# VDD_GND.net
KiCad netlist of a schematic drawn in Altium Designer
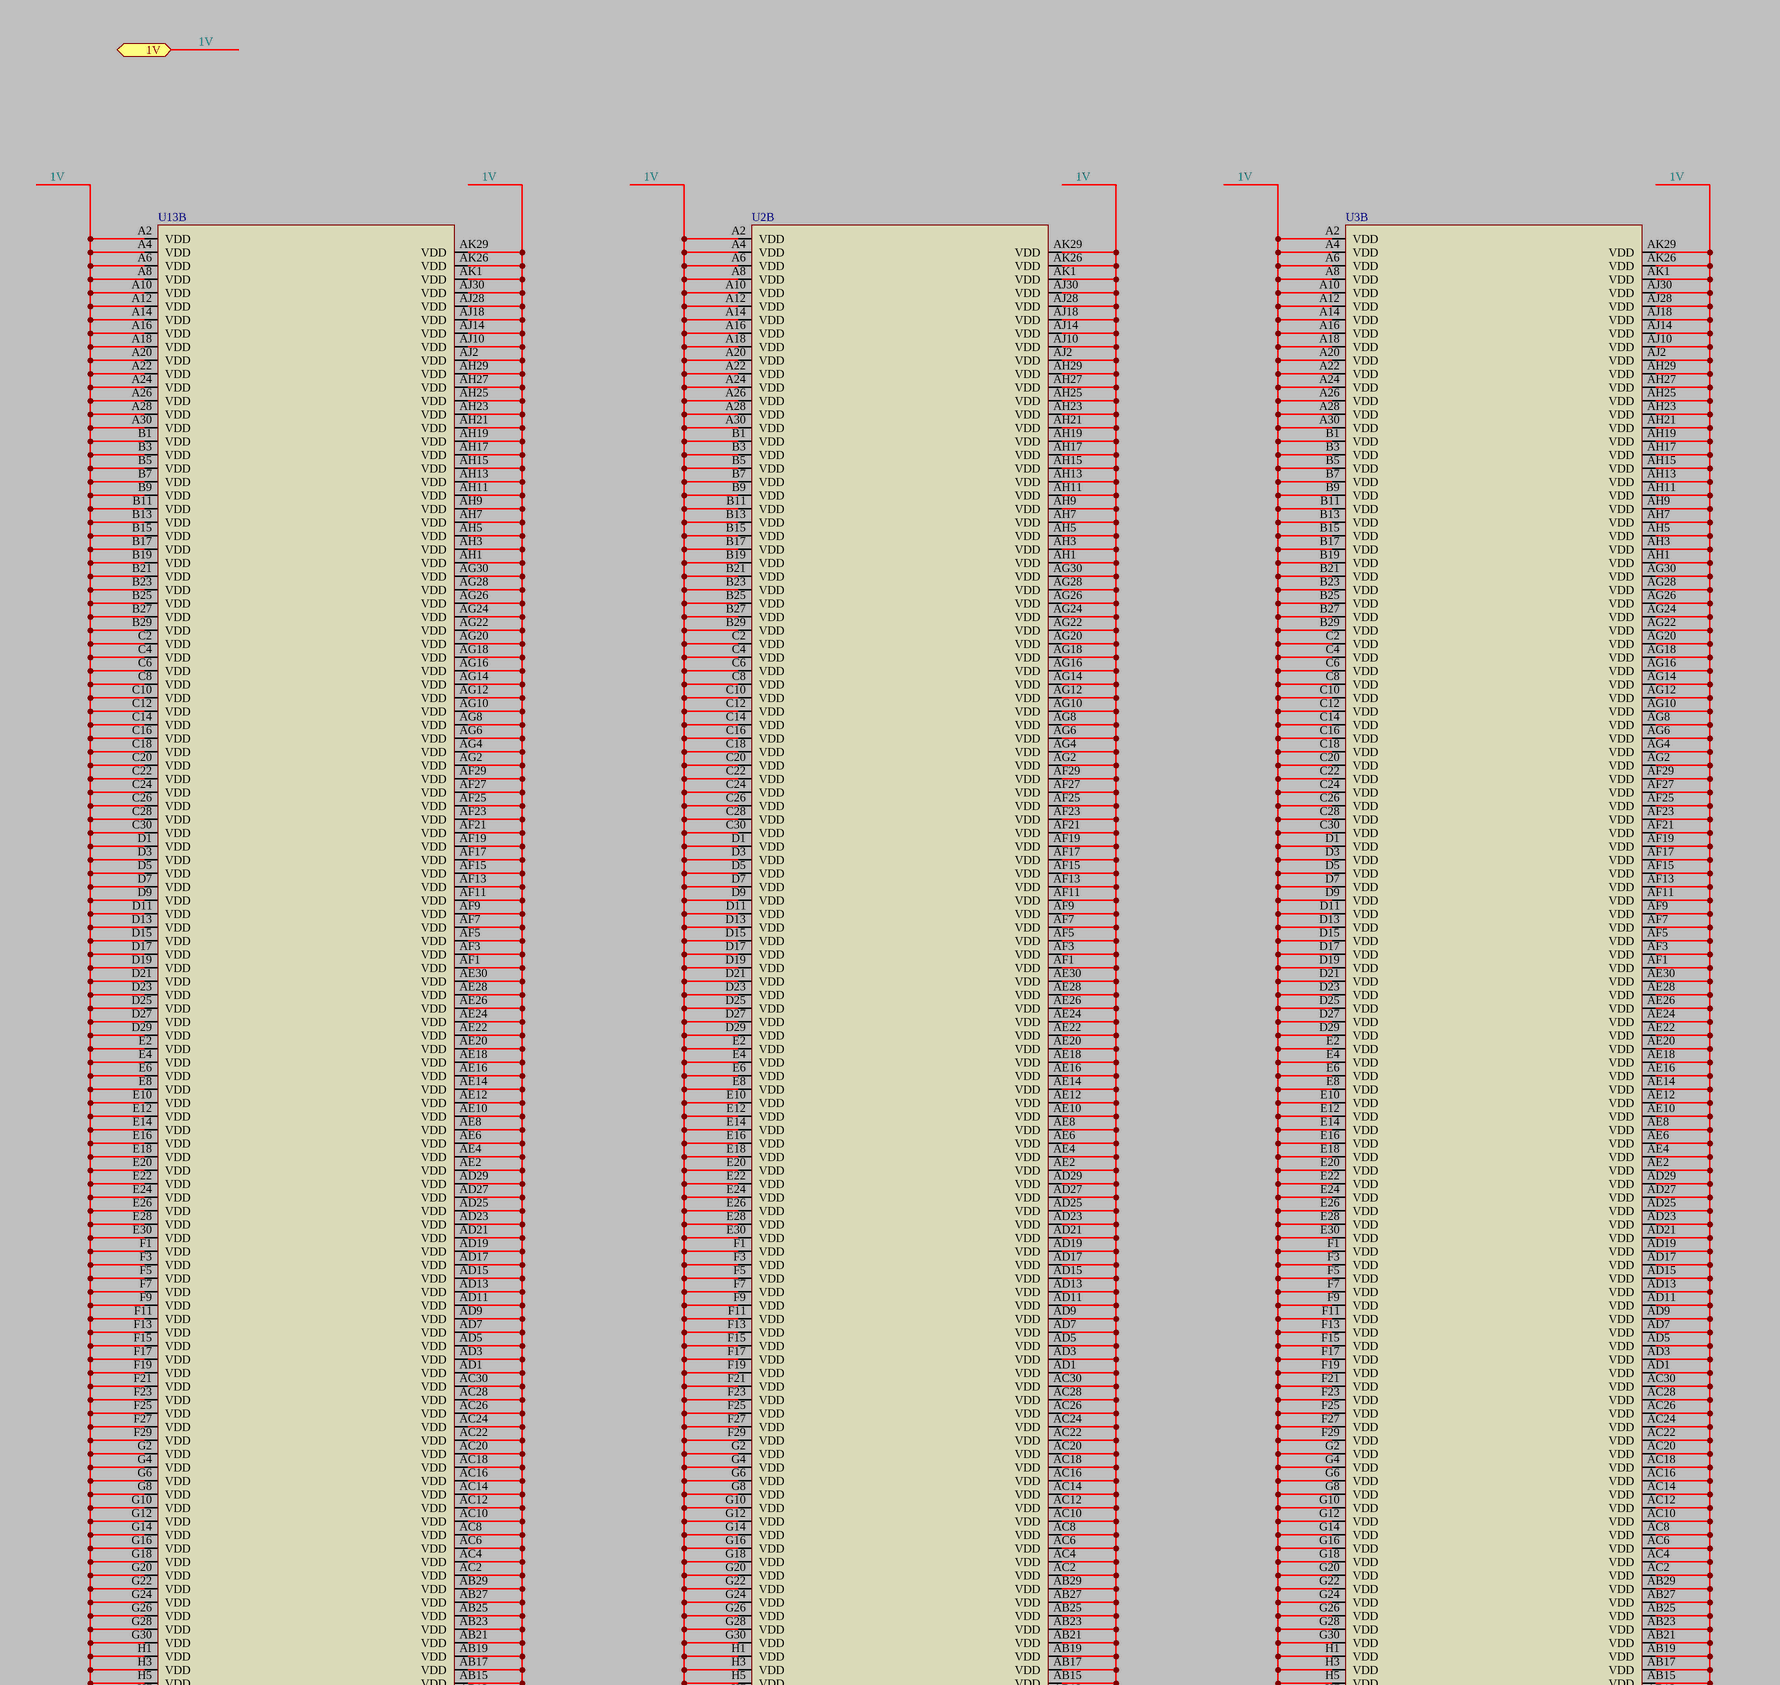
[diagram p0: VDD_GND.SchDoc, top left]
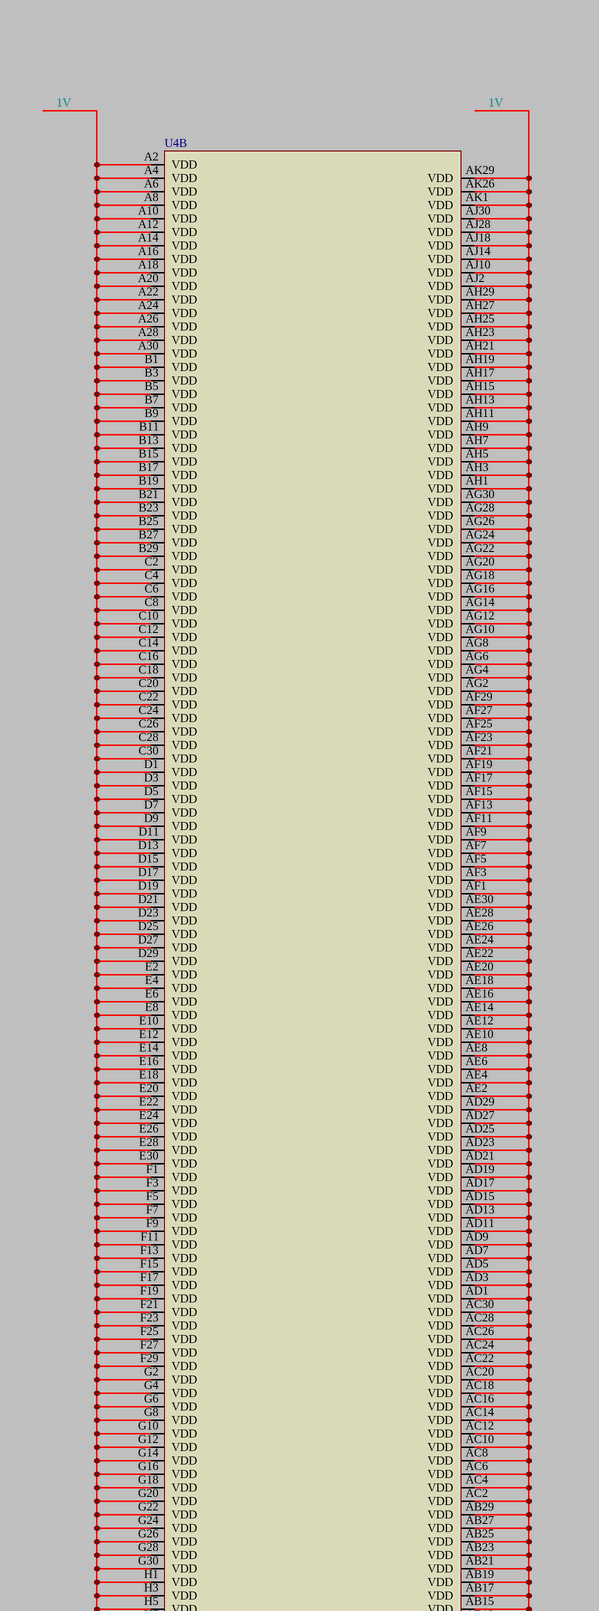
[diagram p1: VDD_GND.SchDoc, top middle]
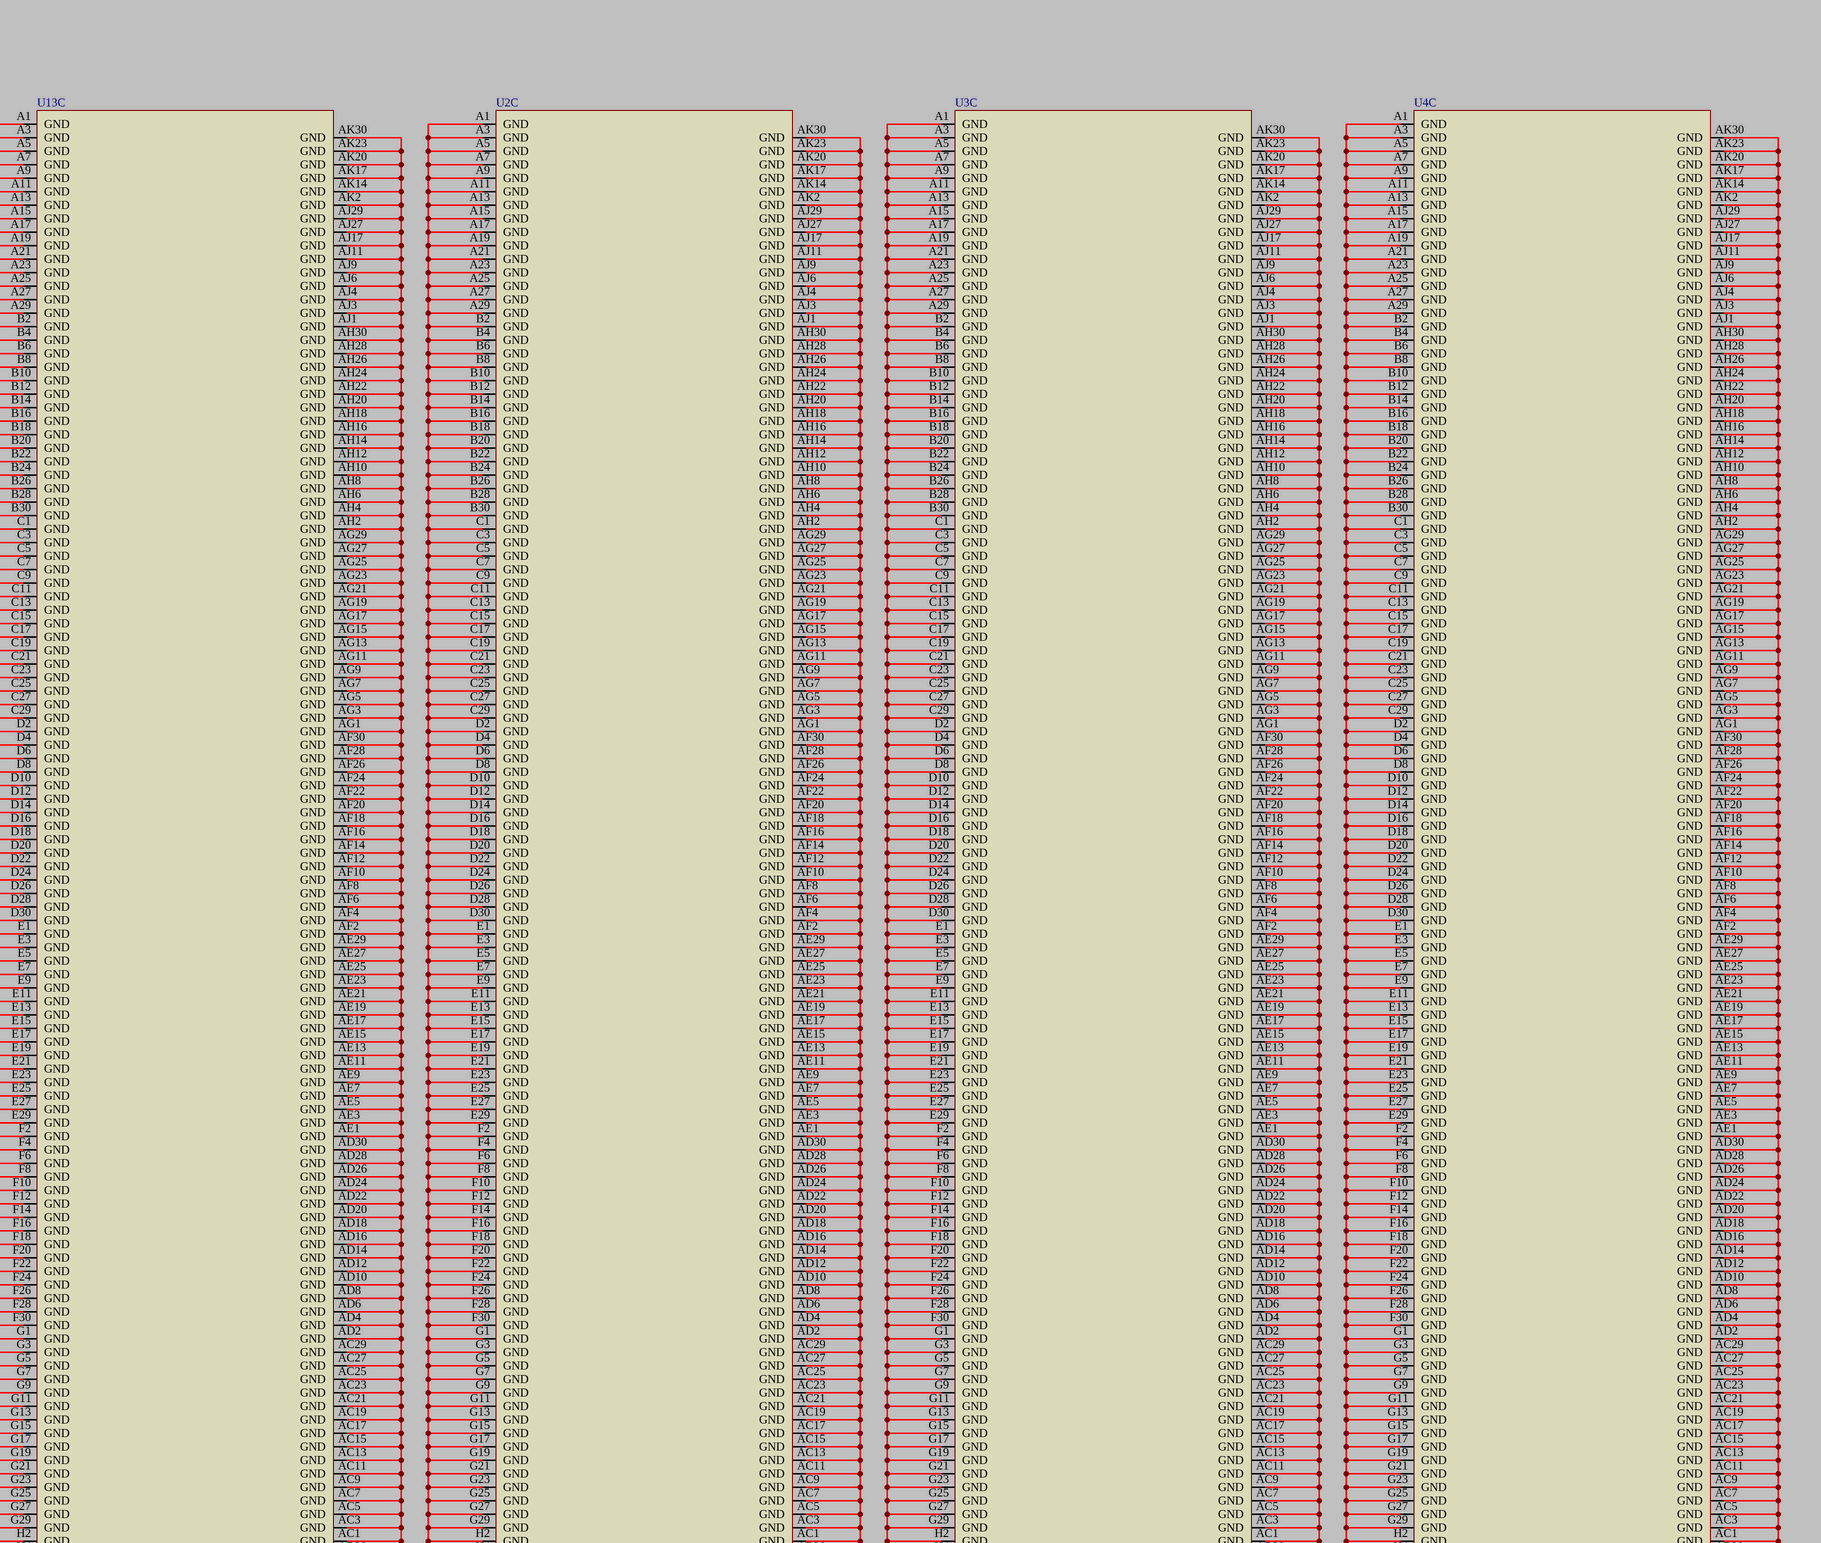
[diagram p2: VDD_GND.SchDoc, top right]
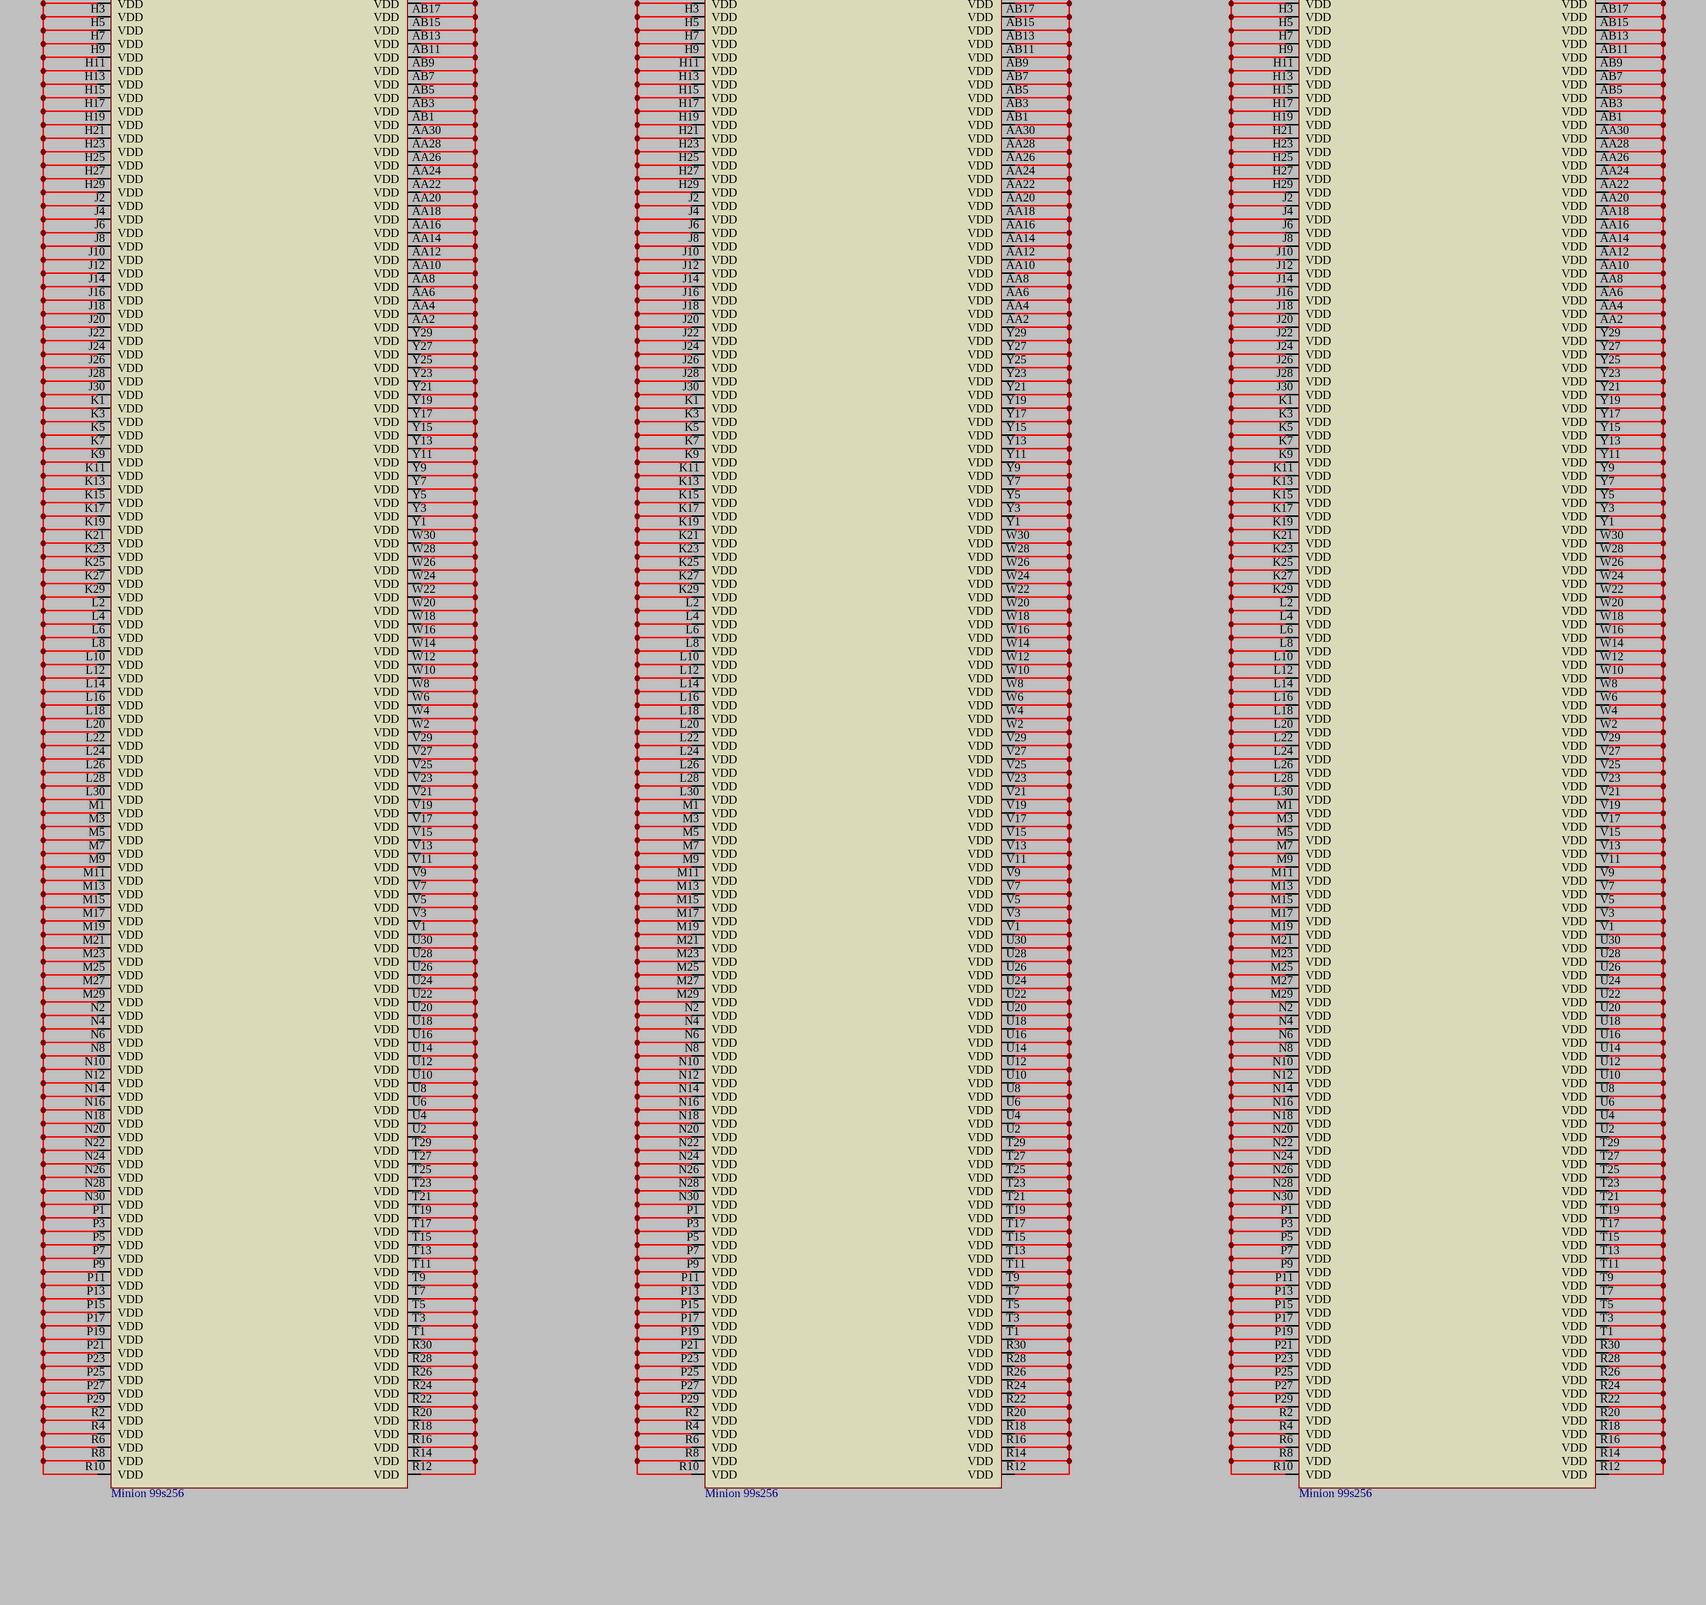
[diagram p3: VDD_GND.SchDoc, bottom left]
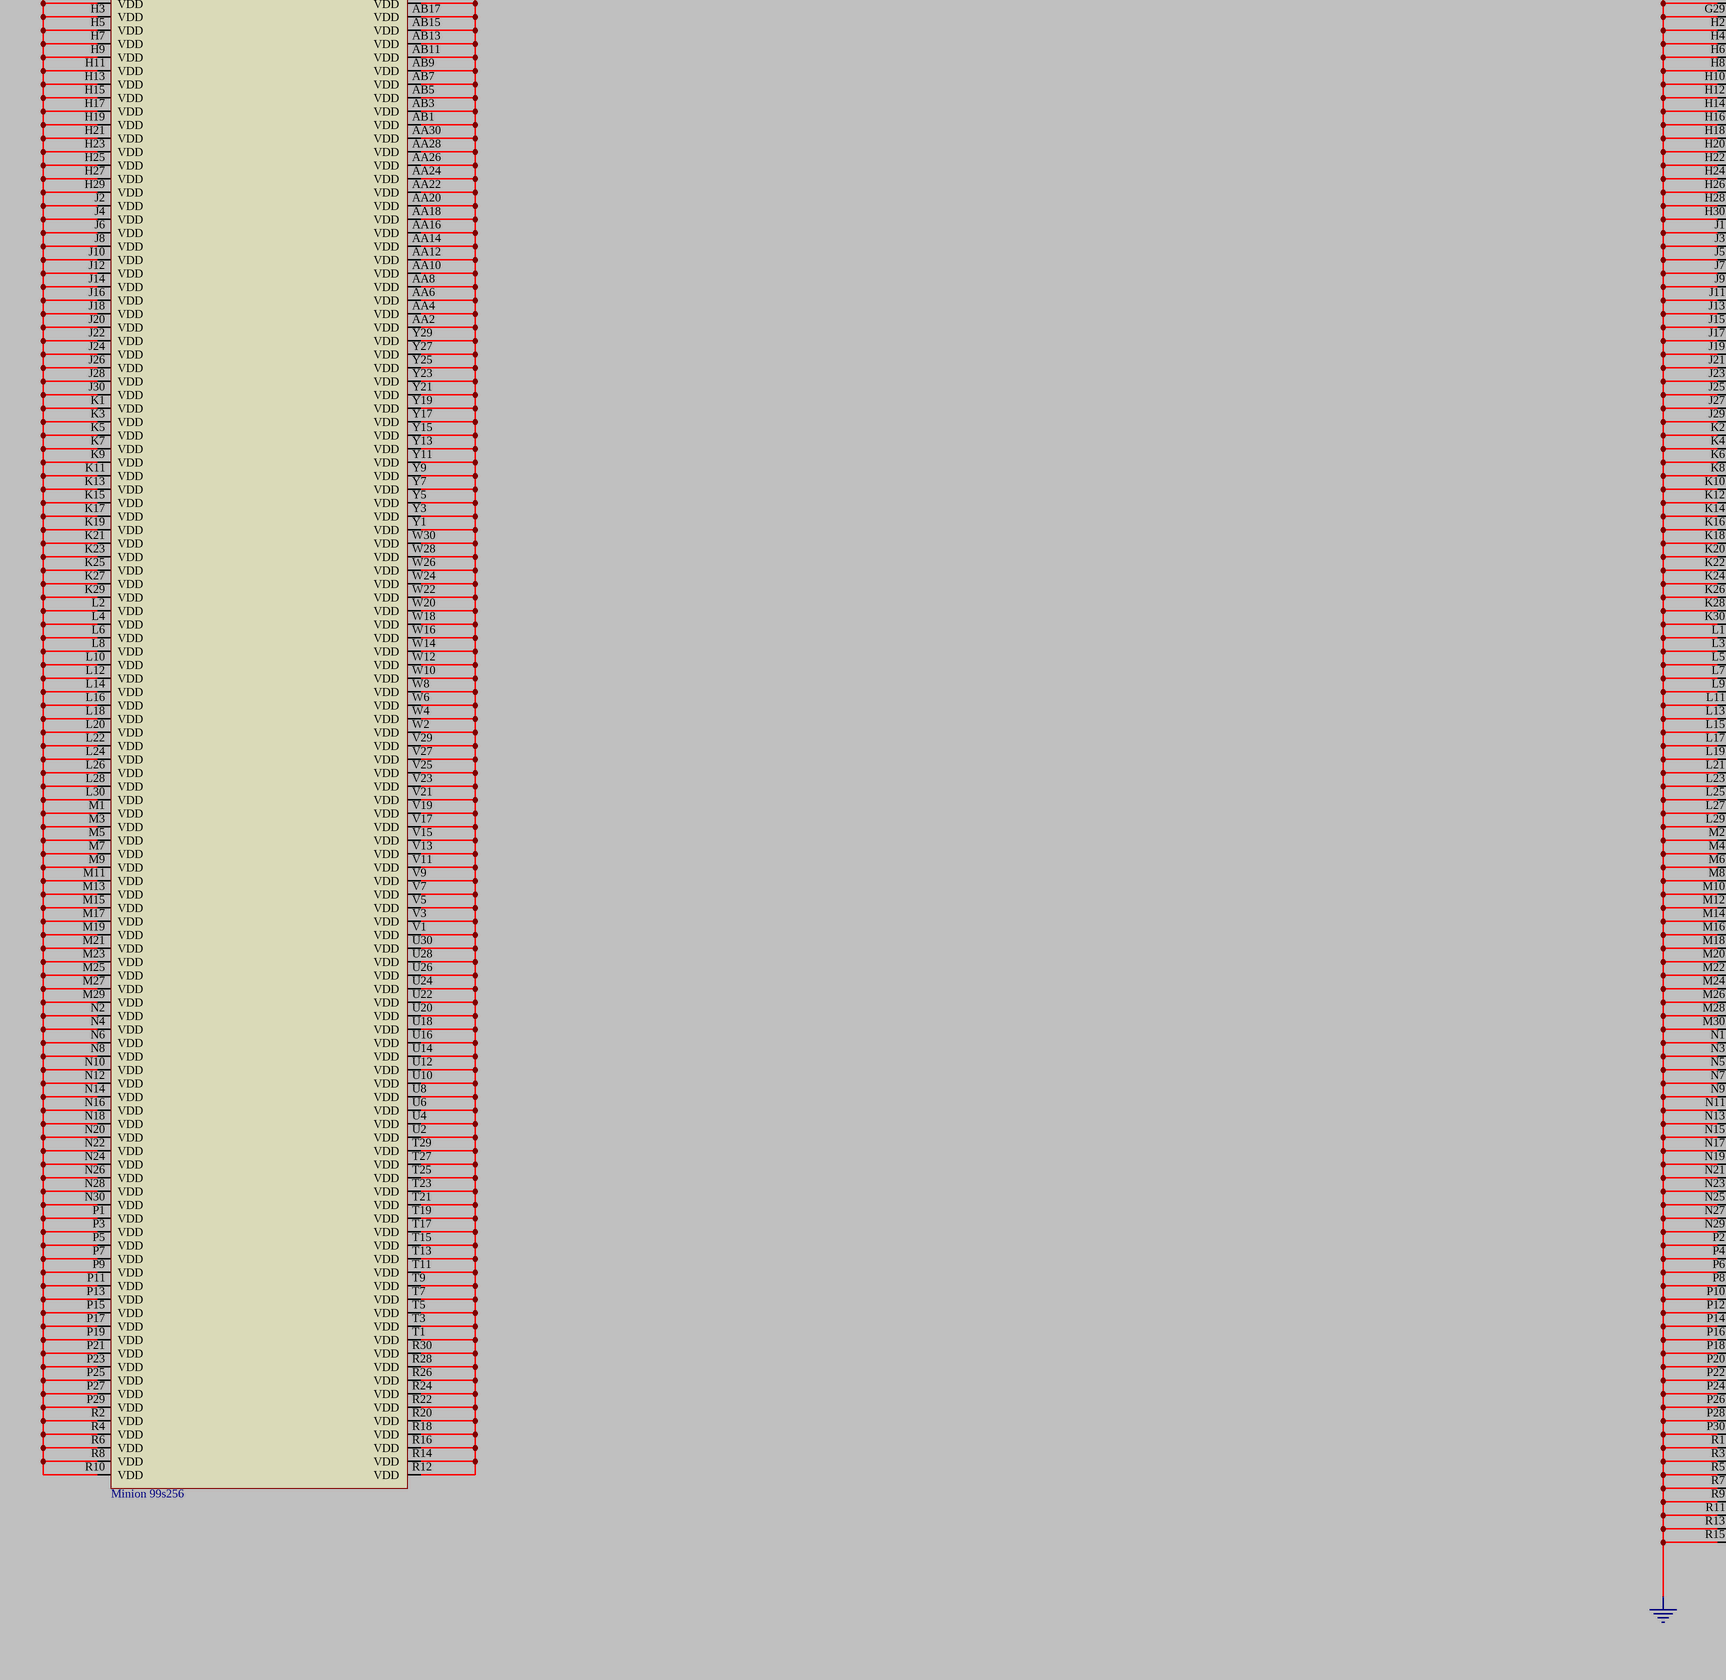
[diagram p4: VDD_GND.SchDoc, bottom middle]
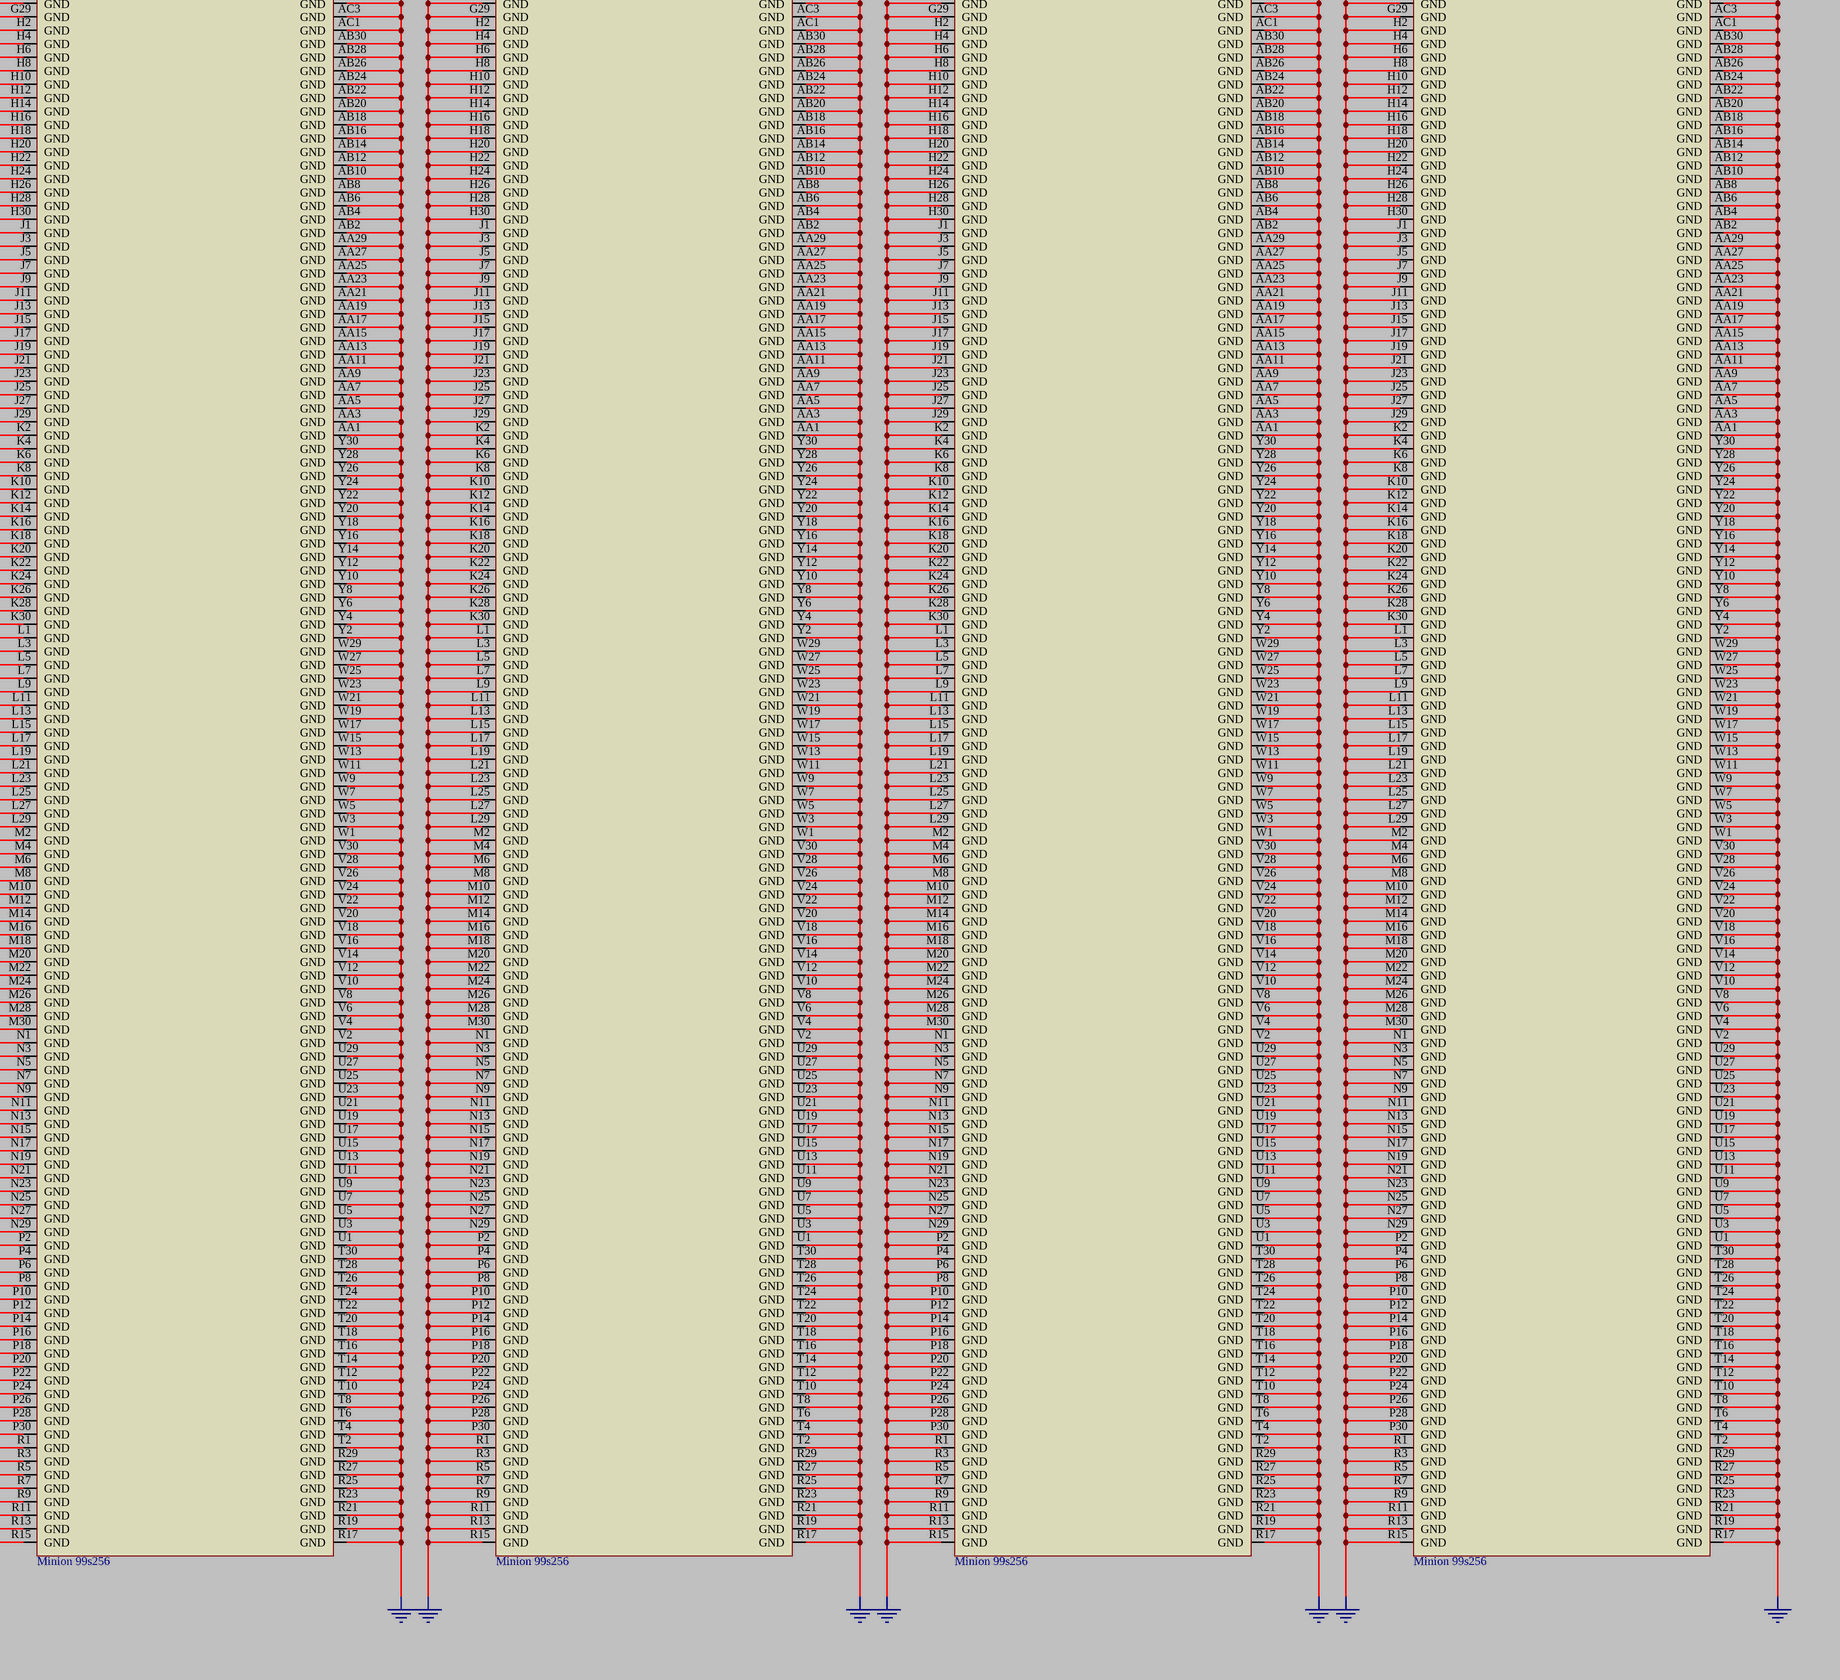
[diagram p5: VDD_GND.SchDoc, bottom right]

(export (version "E")
  (design (tool "Eeschema 10.0.6"))
  (components
    (comp (ref "U2")
      (value "Minion 99s256")
      (footprint "SMD_BGA900C80P30X30")
      (libsource (lib "Schlib1") (part "Minion 99s256"))
    )
    (comp (ref "U3")
      (value "Minion 99s256")
      (footprint "SMD_BGA900C80P30X30")
      (libsource (lib "Schlib1") (part "Minion 99s256"))
    )
    (comp (ref "U4")
      (value "Minion 99s256")
      (footprint "SMD_BGA900C80P30X30")
      (libsource (lib "Schlib1") (part "Minion 99s256"))
    )
    (comp (ref "U13")
      (value "Minion 99s256")
      (footprint "SMD_BGA900C80P30X30")
      (libsource (lib "Schlib1") (part "Minion 99s256"))
    )
  )
  (nets
    (net (code "1") (name "/1V") (class "Default")
      (node (ref "U13") (pin "A10") (pinfunction "VDD_A10") (pintype "passive"))
      (node (ref "U13") (pin "A12") (pinfunction "VDD_A12") (pintype "passive"))
      (node (ref "U13") (pin "A14") (pinfunction "VDD_A14") (pintype "passive"))
      (node (ref "U13") (pin "A16") (pinfunction "VDD_A16") (pintype "passive"))
      (node (ref "U13") (pin "A18") (pinfunction "VDD_A18") (pintype "passive"))
      (node (ref "U13") (pin "A2") (pinfunction "VDD_A2") (pintype "passive"))
      (node (ref "U13") (pin "A20") (pinfunction "VDD_A20") (pintype "passive"))
      (node (ref "U13") (pin "A22") (pinfunction "VDD_A22") (pintype "passive"))
      (node (ref "U13") (pin "A24") (pinfunction "VDD_A24") (pintype "passive"))
      (node (ref "U13") (pin "A26") (pinfunction "VDD_A26") (pintype "passive"))
      (node (ref "U13") (pin "A28") (pinfunction "VDD_A28") (pintype "passive"))
      (node (ref "U13") (pin "A30") (pinfunction "VDD_A30") (pintype "passive"))
      (node (ref "U13") (pin "A4") (pinfunction "VDD_A4") (pintype "passive"))
      (node (ref "U13") (pin "A6") (pinfunction "VDD_A6") (pintype "passive"))
      (node (ref "U13") (pin "A8") (pinfunction "VDD_A8") (pintype "passive"))
      (node (ref "U13") (pin "AA10") (pinfunction "VDD_AA10") (pintype "passive"))
      (node (ref "U13") (pin "AA12") (pinfunction "VDD_AA12") (pintype "passive"))
      (node (ref "U13") (pin "AA14") (pinfunction "VDD_AA14") (pintype "passive"))
      (node (ref "U13") (pin "AA16") (pinfunction "VDD_AA16") (pintype "passive"))
      (node (ref "U13") (pin "AA18") (pinfunction "VDD_AA18") (pintype "passive"))
      (node (ref "U13") (pin "AA2") (pinfunction "VDD_AA2") (pintype "passive"))
      (node (ref "U13") (pin "AA20") (pinfunction "VDD_AA20") (pintype "passive"))
      (node (ref "U13") (pin "AA22") (pinfunction "VDD_AA22") (pintype "passive"))
      (node (ref "U13") (pin "AA24") (pinfunction "VDD_AA24") (pintype "passive"))
      (node (ref "U13") (pin "AA26") (pinfunction "VDD_AA26") (pintype "passive"))
      (node (ref "U13") (pin "AA28") (pinfunction "VDD_AA28") (pintype "passive"))
      (node (ref "U13") (pin "AA30") (pinfunction "VDD_AA30") (pintype "passive"))
      (node (ref "U13") (pin "AA4") (pinfunction "VDD_AA4") (pintype "passive"))
      (node (ref "U13") (pin "AA6") (pinfunction "VDD_AA6") (pintype "passive"))
      (node (ref "U13") (pin "AA8") (pinfunction "VDD_AA8") (pintype "passive"))
      (node (ref "U13") (pin "AB1") (pinfunction "VDD_AB1") (pintype "passive"))
      (node (ref "U13") (pin "AB11") (pinfunction "VDD_AB11") (pintype "passive"))
      (node (ref "U13") (pin "AB13") (pinfunction "VDD_AB13") (pintype "passive"))
      (node (ref "U13") (pin "AB15") (pinfunction "VDD_AB15") (pintype "passive"))
      (node (ref "U13") (pin "AB17") (pinfunction "VDD_AB17") (pintype "passive"))
      (node (ref "U13") (pin "AB19") (pinfunction "VDD_AB19") (pintype "passive"))
      (node (ref "U13") (pin "AB21") (pinfunction "VDD_AB21") (pintype "passive"))
      (node (ref "U13") (pin "AB23") (pinfunction "VDD_AB23") (pintype "passive"))
      (node (ref "U13") (pin "AB25") (pinfunction "VDD_AB25") (pintype "passive"))
      (node (ref "U13") (pin "AB27") (pinfunction "VDD_AB27") (pintype "passive"))
      (node (ref "U13") (pin "AB29") (pinfunction "VDD_AB29") (pintype "passive"))
      (node (ref "U13") (pin "AB3") (pinfunction "VDD_AB3") (pintype "passive"))
      (node (ref "U13") (pin "AB5") (pinfunction "VDD_AB5") (pintype "passive"))
      (node (ref "U13") (pin "AB7") (pinfunction "VDD_AB7") (pintype "passive"))
      (node (ref "U13") (pin "AB9") (pinfunction "VDD_AB9") (pintype "passive"))
      (node (ref "U13") (pin "AC10") (pinfunction "VDD_AC10") (pintype "passive"))
      (node (ref "U13") (pin "AC12") (pinfunction "VDD_AC12") (pintype "passive"))
      (node (ref "U13") (pin "AC14") (pinfunction "VDD_AC14") (pintype "passive"))
      (node (ref "U13") (pin "AC16") (pinfunction "VDD_AC16") (pintype "passive"))
      (node (ref "U13") (pin "AC18") (pinfunction "VDD_AC18") (pintype "passive"))
      (node (ref "U13") (pin "AC2") (pinfunction "VDD_AC2") (pintype "passive"))
      (node (ref "U13") (pin "AC20") (pinfunction "VDD_AC20") (pintype "passive"))
      (node (ref "U13") (pin "AC22") (pinfunction "VDD_AC22") (pintype "passive"))
      (node (ref "U13") (pin "AC24") (pinfunction "VDD_AC24") (pintype "passive"))
      (node (ref "U13") (pin "AC26") (pinfunction "VDD_AC26") (pintype "passive"))
      (node (ref "U13") (pin "AC28") (pinfunction "VDD_AC28") (pintype "passive"))
      (node (ref "U13") (pin "AC30") (pinfunction "VDD_AC30") (pintype "passive"))
      (node (ref "U13") (pin "AC4") (pinfunction "VDD_AC4") (pintype "passive"))
      (node (ref "U13") (pin "AC6") (pinfunction "VDD_AC6") (pintype "passive"))
      (node (ref "U13") (pin "AC8") (pinfunction "VDD_AC8") (pintype "passive"))
      (node (ref "U13") (pin "AD1") (pinfunction "VDD_AD1") (pintype "passive"))
      (node (ref "U13") (pin "AD11") (pinfunction "VDD_AD11") (pintype "passive"))
      (node (ref "U13") (pin "AD13") (pinfunction "VDD_AD13") (pintype "passive"))
      (node (ref "U13") (pin "AD15") (pinfunction "VDD_AD15") (pintype "passive"))
      (node (ref "U13") (pin "AD17") (pinfunction "VDD_AD17") (pintype "passive"))
      (node (ref "U13") (pin "AD19") (pinfunction "VDD_AD19") (pintype "passive"))
      (node (ref "U13") (pin "AD21") (pinfunction "VDD_AD21") (pintype "passive"))
      (node (ref "U13") (pin "AD23") (pinfunction "VDD_AD23") (pintype "passive"))
      (node (ref "U13") (pin "AD25") (pinfunction "VDD_AD25") (pintype "passive"))
      (node (ref "U13") (pin "AD27") (pinfunction "VDD_AD27") (pintype "passive"))
      (node (ref "U13") (pin "AD29") (pinfunction "VDD_AD29") (pintype "passive"))
      (node (ref "U13") (pin "AD3") (pinfunction "VDD_AD3") (pintype "passive"))
      (node (ref "U13") (pin "AD5") (pinfunction "VDD_AD5") (pintype "passive"))
      (node (ref "U13") (pin "AD7") (pinfunction "VDD_AD7") (pintype "passive"))
      (node (ref "U13") (pin "AD9") (pinfunction "VDD_AD9") (pintype "passive"))
      (node (ref "U13") (pin "AE10") (pinfunction "VDD_AE10") (pintype "passive"))
      (node (ref "U13") (pin "AE12") (pinfunction "VDD_AE12") (pintype "passive"))
      (node (ref "U13") (pin "AE14") (pinfunction "VDD_AE14") (pintype "passive"))
      (node (ref "U13") (pin "AE16") (pinfunction "VDD_AE16") (pintype "passive"))
      (node (ref "U13") (pin "AE18") (pinfunction "VDD_AE18") (pintype "passive"))
      (node (ref "U13") (pin "AE2") (pinfunction "VDD_AE2") (pintype "passive"))
      (node (ref "U13") (pin "AE20") (pinfunction "VDD_AE20") (pintype "passive"))
      (node (ref "U13") (pin "AE22") (pinfunction "VDD_AE22") (pintype "passive"))
      (node (ref "U13") (pin "AE24") (pinfunction "VDD_AE24") (pintype "passive"))
      (node (ref "U13") (pin "AE26") (pinfunction "VDD_AE26") (pintype "passive"))
      (node (ref "U13") (pin "AE28") (pinfunction "VDD_AE28") (pintype "passive"))
      (node (ref "U13") (pin "AE30") (pinfunction "VDD_AE30") (pintype "passive"))
      (node (ref "U13") (pin "AE4") (pinfunction "VDD_AE4") (pintype "passive"))
      (node (ref "U13") (pin "AE6") (pinfunction "VDD_AE6") (pintype "passive"))
      (node (ref "U13") (pin "AE8") (pinfunction "VDD_AE8") (pintype "passive"))
      (node (ref "U13") (pin "AF1") (pinfunction "VDD_AF1") (pintype "passive"))
      (node (ref "U13") (pin "AF11") (pinfunction "VDD_AF11") (pintype "passive"))
      (node (ref "U13") (pin "AF13") (pinfunction "VDD_AF13") (pintype "passive"))
      (node (ref "U13") (pin "AF15") (pinfunction "VDD_AF15") (pintype "passive"))
      (node (ref "U13") (pin "AF17") (pinfunction "VDD_AF17") (pintype "passive"))
      (node (ref "U13") (pin "AF19") (pinfunction "VDD_AF19") (pintype "passive"))
      (node (ref "U13") (pin "AF21") (pinfunction "VDD_AF21") (pintype "passive"))
      (node (ref "U13") (pin "AF23") (pinfunction "VDD_AF23") (pintype "passive"))
      (node (ref "U13") (pin "AF25") (pinfunction "VDD_AF25") (pintype "passive"))
      (node (ref "U13") (pin "AF27") (pinfunction "VDD_AF27") (pintype "passive"))
      (node (ref "U13") (pin "AF29") (pinfunction "VDD_AF29") (pintype "passive"))
      (node (ref "U13") (pin "AF3") (pinfunction "VDD_AF3") (pintype "passive"))
      (node (ref "U13") (pin "AF5") (pinfunction "VDD_AF5") (pintype "passive"))
      (node (ref "U13") (pin "AF7") (pinfunction "VDD_AF7") (pintype "passive"))
      (node (ref "U13") (pin "AF9") (pinfunction "VDD_AF9") (pintype "passive"))
      (node (ref "U13") (pin "AG10") (pinfunction "VDD_AG10") (pintype "passive"))
      (node (ref "U13") (pin "AG12") (pinfunction "VDD_AG12") (pintype "passive"))
      (node (ref "U13") (pin "AG14") (pinfunction "VDD_AG14") (pintype "passive"))
      (node (ref "U13") (pin "AG16") (pinfunction "VDD_AG16") (pintype "passive"))
      (node (ref "U13") (pin "AG18") (pinfunction "VDD_AG18") (pintype "passive"))
      (node (ref "U13") (pin "AG2") (pinfunction "VDD_AG2") (pintype "passive"))
      (node (ref "U13") (pin "AG20") (pinfunction "VDD_AG20") (pintype "passive"))
      (node (ref "U13") (pin "AG22") (pinfunction "VDD_AG22") (pintype "passive"))
      (node (ref "U13") (pin "AG24") (pinfunction "VDD_AG24") (pintype "passive"))
      (node (ref "U13") (pin "AG26") (pinfunction "VDD_AG26") (pintype "passive"))
      (node (ref "U13") (pin "AG28") (pinfunction "VDD_AG28") (pintype "passive"))
      (node (ref "U13") (pin "AG30") (pinfunction "VDD_AG30") (pintype "passive"))
      (node (ref "U13") (pin "AG4") (pinfunction "VDD_AG4") (pintype "passive"))
      (node (ref "U13") (pin "AG6") (pinfunction "VDD_AG6") (pintype "passive"))
      (node (ref "U13") (pin "AG8") (pinfunction "VDD_AG8") (pintype "passive"))
      (node (ref "U13") (pin "AH1") (pinfunction "VDD_AH1") (pintype "passive"))
      (node (ref "U13") (pin "AH11") (pinfunction "VDD_AH11") (pintype "passive"))
      (node (ref "U13") (pin "AH13") (pinfunction "VDD_AH13") (pintype "passive"))
      (node (ref "U13") (pin "AH15") (pinfunction "VDD_AH15") (pintype "passive"))
      (node (ref "U13") (pin "AH17") (pinfunction "VDD_AH17") (pintype "passive"))
      (node (ref "U13") (pin "AH19") (pinfunction "VDD_AH19") (pintype "passive"))
      (node (ref "U13") (pin "AH21") (pinfunction "VDD_AH21") (pintype "passive"))
      (node (ref "U13") (pin "AH23") (pinfunction "VDD_AH23") (pintype "passive"))
      (node (ref "U13") (pin "AH25") (pinfunction "VDD_AH25") (pintype "passive"))
      (node (ref "U13") (pin "AH27") (pinfunction "VDD_AH27") (pintype "passive"))
      (node (ref "U13") (pin "AH29") (pinfunction "VDD_AH29") (pintype "passive"))
      (node (ref "U13") (pin "AH3") (pinfunction "VDD_AH3") (pintype "passive"))
      (node (ref "U13") (pin "AH5") (pinfunction "VDD_AH5") (pintype "passive"))
      (node (ref "U13") (pin "AH7") (pinfunction "VDD_AH7") (pintype "passive"))
      (node (ref "U13") (pin "AH9") (pinfunction "VDD_AH9") (pintype "passive"))
      (node (ref "U13") (pin "AJ10") (pinfunction "VDD_AJ10") (pintype "passive"))
      (node (ref "U13") (pin "AJ14") (pinfunction "VDD_AJ14") (pintype "passive"))
      (node (ref "U13") (pin "AJ18") (pinfunction "VDD_AJ18") (pintype "passive"))
      (node (ref "U13") (pin "AJ2") (pinfunction "VDD_AJ2") (pintype "passive"))
      (node (ref "U13") (pin "AJ28") (pinfunction "VDD_AJ28") (pintype "passive"))
      (node (ref "U13") (pin "AJ30") (pinfunction "VDD_AJ30") (pintype "passive"))
      (node (ref "U13") (pin "AK1") (pinfunction "VDD_AK1") (pintype "passive"))
      (node (ref "U13") (pin "AK26") (pinfunction "VDD_AK26") (pintype "passive"))
      (node (ref "U13") (pin "AK29") (pinfunction "VDD_AK29") (pintype "passive"))
      (node (ref "U13") (pin "B1") (pinfunction "VDD_B1") (pintype "passive"))
      (node (ref "U13") (pin "B11") (pinfunction "VDD_B11") (pintype "passive"))
      (node (ref "U13") (pin "B13") (pinfunction "VDD_B13") (pintype "passive"))
      (node (ref "U13") (pin "B15") (pinfunction "VDD_B15") (pintype "passive"))
      (node (ref "U13") (pin "B17") (pinfunction "VDD_B17") (pintype "passive"))
      (node (ref "U13") (pin "B19") (pinfunction "VDD_B19") (pintype "passive"))
      (node (ref "U13") (pin "B21") (pinfunction "VDD_B21") (pintype "passive"))
      (node (ref "U13") (pin "B23") (pinfunction "VDD_B23") (pintype "passive"))
      (node (ref "U13") (pin "B25") (pinfunction "VDD_B25") (pintype "passive"))
      (node (ref "U13") (pin "B27") (pinfunction "VDD_B27") (pintype "passive"))
      (node (ref "U13") (pin "B29") (pinfunction "VDD_B29") (pintype "passive"))
      (node (ref "U13") (pin "B3") (pinfunction "VDD_B3") (pintype "passive"))
      (node (ref "U13") (pin "B5") (pinfunction "VDD_B5") (pintype "passive"))
      (node (ref "U13") (pin "B7") (pinfunction "VDD_B7") (pintype "passive"))
      (node (ref "U13") (pin "B9") (pinfunction "VDD_B9") (pintype "passive"))
      (node (ref "U13") (pin "C10") (pinfunction "VDD_C10") (pintype "passive"))
      (node (ref "U13") (pin "C12") (pinfunction "VDD_C12") (pintype "passive"))
      (node (ref "U13") (pin "C14") (pinfunction "VDD_C14") (pintype "passive"))
      (node (ref "U13") (pin "C16") (pinfunction "VDD_C16") (pintype "passive"))
      (node (ref "U13") (pin "C18") (pinfunction "VDD_C18") (pintype "passive"))
      (node (ref "U13") (pin "C2") (pinfunction "VDD_C2") (pintype "passive"))
      (node (ref "U13") (pin "C20") (pinfunction "VDD_C20") (pintype "passive"))
      (node (ref "U13") (pin "C22") (pinfunction "VDD_C22") (pintype "passive"))
      (node (ref "U13") (pin "C24") (pinfunction "VDD_C24") (pintype "passive"))
      (node (ref "U13") (pin "C26") (pinfunction "VDD_C26") (pintype "passive"))
      (node (ref "U13") (pin "C28") (pinfunction "VDD_C28") (pintype "passive"))
      (node (ref "U13") (pin "C30") (pinfunction "VDD_C30") (pintype "passive"))
      (node (ref "U13") (pin "C4") (pinfunction "VDD_C4") (pintype "passive"))
      (node (ref "U13") (pin "C6") (pinfunction "VDD_C6") (pintype "passive"))
      (node (ref "U13") (pin "C8") (pinfunction "VDD_C8") (pintype "passive"))
      (node (ref "U13") (pin "D1") (pinfunction "VDD_D1") (pintype "passive"))
      (node (ref "U13") (pin "D11") (pinfunction "VDD_D11") (pintype "passive"))
      (node (ref "U13") (pin "D13") (pinfunction "VDD_D13") (pintype "passive"))
      (node (ref "U13") (pin "D15") (pinfunction "VDD_D15") (pintype "passive"))
      (node (ref "U13") (pin "D17") (pinfunction "VDD_D17") (pintype "passive"))
      (node (ref "U13") (pin "D19") (pinfunction "VDD_D19") (pintype "passive"))
      (node (ref "U13") (pin "D21") (pinfunction "VDD_D21") (pintype "passive"))
      (node (ref "U13") (pin "D23") (pinfunction "VDD_D23") (pintype "passive"))
      (node (ref "U13") (pin "D25") (pinfunction "VDD_D25") (pintype "passive"))
      (node (ref "U13") (pin "D27") (pinfunction "VDD_D27") (pintype "passive"))
      (node (ref "U13") (pin "D29") (pinfunction "VDD_D29") (pintype "passive"))
      (node (ref "U13") (pin "D3") (pinfunction "VDD_D3") (pintype "passive"))
      (node (ref "U13") (pin "D5") (pinfunction "VDD_D5") (pintype "passive"))
      (node (ref "U13") (pin "D7") (pinfunction "VDD_D7") (pintype "passive"))
      (node (ref "U13") (pin "D9") (pinfunction "VDD_D9") (pintype "passive"))
      (node (ref "U13") (pin "E10") (pinfunction "VDD_E10") (pintype "passive"))
      (node (ref "U13") (pin "E12") (pinfunction "VDD_E12") (pintype "passive"))
      (node (ref "U13") (pin "E14") (pinfunction "VDD_E14") (pintype "passive"))
      (node (ref "U13") (pin "E16") (pinfunction "VDD_E16") (pintype "passive"))
      (node (ref "U13") (pin "E18") (pinfunction "VDD_E18") (pintype "passive"))
      (node (ref "U13") (pin "E2") (pinfunction "VDD_E2") (pintype "passive"))
      (node (ref "U13") (pin "E20") (pinfunction "VDD_E20") (pintype "passive"))
      (node (ref "U13") (pin "E22") (pinfunction "VDD_E22") (pintype "passive"))
      (node (ref "U13") (pin "E24") (pinfunction "VDD_E24") (pintype "passive"))
      (node (ref "U13") (pin "E26") (pinfunction "VDD_E26") (pintype "passive"))
      (node (ref "U13") (pin "E28") (pinfunction "VDD_E28") (pintype "passive"))
      (node (ref "U13") (pin "E30") (pinfunction "VDD_E30") (pintype "passive"))
      (node (ref "U13") (pin "E4") (pinfunction "VDD_E4") (pintype "passive"))
      (node (ref "U13") (pin "E6") (pinfunction "VDD_E6") (pintype "passive"))
      (node (ref "U13") (pin "E8") (pinfunction "VDD_E8") (pintype "passive"))
      (node (ref "U13") (pin "F1") (pinfunction "VDD_F1") (pintype "passive"))
      (node (ref "U13") (pin "F11") (pinfunction "VDD_F11") (pintype "passive"))
      (node (ref "U13") (pin "F13") (pinfunction "VDD_F13") (pintype "passive"))
      (node (ref "U13") (pin "F15") (pinfunction "VDD_F15") (pintype "passive"))
      (node (ref "U13") (pin "F17") (pinfunction "VDD_F17") (pintype "passive"))
      (node (ref "U13") (pin "F19") (pinfunction "VDD_F19") (pintype "passive"))
      (node (ref "U13") (pin "F21") (pinfunction "VDD_F21") (pintype "passive"))
      (node (ref "U13") (pin "F23") (pinfunction "VDD_F23") (pintype "passive"))
      (node (ref "U13") (pin "F25") (pinfunction "VDD_F25") (pintype "passive"))
      (node (ref "U13") (pin "F27") (pinfunction "VDD_F27") (pintype "passive"))
      (node (ref "U13") (pin "F29") (pinfunction "VDD_F29") (pintype "passive"))
      (node (ref "U13") (pin "F3") (pinfunction "VDD_F3") (pintype "passive"))
      (node (ref "U13") (pin "F5") (pinfunction "VDD_F5") (pintype "passive"))
      (node (ref "U13") (pin "F7") (pinfunction "VDD_F7") (pintype "passive"))
      (node (ref "U13") (pin "F9") (pinfunction "VDD_F9") (pintype "passive"))
      (node (ref "U13") (pin "G10") (pinfunction "VDD_G10") (pintype "passive"))
      (node (ref "U13") (pin "G12") (pinfunction "VDD_G12") (pintype "passive"))
      (node (ref "U13") (pin "G14") (pinfunction "VDD_G14") (pintype "passive"))
      (node (ref "U13") (pin "G16") (pinfunction "VDD_G16") (pintype "passive"))
      (node (ref "U13") (pin "G18") (pinfunction "VDD_G18") (pintype "passive"))
      (node (ref "U13") (pin "G2") (pinfunction "VDD_G2") (pintype "passive"))
      (node (ref "U13") (pin "G20") (pinfunction "VDD_G20") (pintype "passive"))
      (node (ref "U13") (pin "G22") (pinfunction "VDD_G22") (pintype "passive"))
      (node (ref "U13") (pin "G24") (pinfunction "VDD_G24") (pintype "passive"))
      (node (ref "U13") (pin "G26") (pinfunction "VDD_G26") (pintype "passive"))
      (node (ref "U13") (pin "G28") (pinfunction "VDD_G28") (pintype "passive"))
      (node (ref "U13") (pin "G30") (pinfunction "VDD_G30") (pintype "passive"))
      (node (ref "U13") (pin "G4") (pinfunction "VDD_G4") (pintype "passive"))
      (node (ref "U13") (pin "G6") (pinfunction "VDD_G6") (pintype "passive"))
      (node (ref "U13") (pin "G8") (pinfunction "VDD_G8") (pintype "passive"))
      (node (ref "U13") (pin "H1") (pinfunction "VDD_H1") (pintype "passive"))
      (node (ref "U13") (pin "H11") (pinfunction "VDD_H11") (pintype "passive"))
      (node (ref "U13") (pin "H13") (pinfunction "VDD_H13") (pintype "passive"))
      (node (ref "U13") (pin "H15") (pinfunction "VDD_H15") (pintype "passive"))
      (node (ref "U13") (pin "H17") (pinfunction "VDD_H17") (pintype "passive"))
      (node (ref "U13") (pin "H19") (pinfunction "VDD_H19") (pintype "passive"))
      (node (ref "U13") (pin "H21") (pinfunction "VDD_H21") (pintype "passive"))
      (node (ref "U13") (pin "H23") (pinfunction "VDD_H23") (pintype "passive"))
      (node (ref "U13") (pin "H25") (pinfunction "VDD_H25") (pintype "passive"))
      (node (ref "U13") (pin "H27") (pinfunction "VDD_H27") (pintype "passive"))
      (node (ref "U13") (pin "H29") (pinfunction "VDD_H29") (pintype "passive"))
      (node (ref "U13") (pin "H3") (pinfunction "VDD_H3") (pintype "passive"))
      (node (ref "U13") (pin "H5") (pinfunction "VDD_H5") (pintype "passive"))
      (node (ref "U13") (pin "H7") (pinfunction "VDD_H7") (pintype "passive"))
      (node (ref "U13") (pin "H9") (pinfunction "VDD_H9") (pintype "passive"))
      (node (ref "U13") (pin "J10") (pinfunction "VDD_J10") (pintype "passive"))
      (node (ref "U13") (pin "J12") (pinfunction "VDD_J12") (pintype "passive"))
      (node (ref "U13") (pin "J14") (pinfunction "VDD_J14") (pintype "passive"))
      (node (ref "U13") (pin "J16") (pinfunction "VDD_J16") (pintype "passive"))
      (node (ref "U13") (pin "J18") (pinfunction "VDD_J18") (pintype "passive"))
      (node (ref "U13") (pin "J2") (pinfunction "VDD_J2") (pintype "passive"))
      (node (ref "U13") (pin "J20") (pinfunction "VDD_J20") (pintype "passive"))
      (node (ref "U13") (pin "J22") (pinfunction "VDD_J22") (pintype "passive"))
      (node (ref "U13") (pin "J24") (pinfunction "VDD_J24") (pintype "passive"))
      (node (ref "U13") (pin "J26") (pinfunction "VDD_J26") (pintype "passive"))
      (node (ref "U13") (pin "J28") (pinfunction "VDD_J28") (pintype "passive"))
      (node (ref "U13") (pin "J30") (pinfunction "VDD_J30") (pintype "passive"))
      (node (ref "U13") (pin "J4") (pinfunction "VDD_J4") (pintype "passive"))
      (node (ref "U13") (pin "J6") (pinfunction "VDD_J6") (pintype "passive"))
      (node (ref "U13") (pin "J8") (pinfunction "VDD_J8") (pintype "passive"))
      (node (ref "U13") (pin "K1") (pinfunction "VDD_K1") (pintype "passive"))
      (node (ref "U13") (pin "K11") (pinfunction "VDD_K11") (pintype "passive"))
      (node (ref "U13") (pin "K13") (pinfunction "VDD_K13") (pintype "passive"))
      (node (ref "U13") (pin "K15") (pinfunction "VDD_K15") (pintype "passive"))
      (node (ref "U13") (pin "K17") (pinfunction "VDD_K17") (pintype "passive"))
      (node (ref "U13") (pin "K19") (pinfunction "VDD_K19") (pintype "passive"))
      (node (ref "U13") (pin "K21") (pinfunction "VDD_K21") (pintype "passive"))
      (node (ref "U13") (pin "K23") (pinfunction "VDD_K23") (pintype "passive"))
      (node (ref "U13") (pin "K25") (pinfunction "VDD_K25") (pintype "passive"))
      (node (ref "U13") (pin "K27") (pinfunction "VDD_K27") (pintype "passive"))
      (node (ref "U13") (pin "K29") (pinfunction "VDD_K29") (pintype "passive"))
      (node (ref "U13") (pin "K3") (pinfunction "VDD_K3") (pintype "passive"))
      (node (ref "U13") (pin "K5") (pinfunction "VDD_K5") (pintype "passive"))
      (node (ref "U13") (pin "K7") (pinfunction "VDD_K7") (pintype "passive"))
      (node (ref "U13") (pin "K9") (pinfunction "VDD_K9") (pintype "passive"))
      (node (ref "U13") (pin "L10") (pinfunction "VDD_L10") (pintype "passive"))
      (node (ref "U13") (pin "L12") (pinfunction "VDD_L12") (pintype "passive"))
      (node (ref "U13") (pin "L14") (pinfunction "VDD_L14") (pintype "passive"))
      (node (ref "U13") (pin "L16") (pinfunction "VDD_L16") (pintype "passive"))
      (node (ref "U13") (pin "L18") (pinfunction "VDD_L18") (pintype "passive"))
      (node (ref "U13") (pin "L2") (pinfunction "VDD_L2") (pintype "passive"))
      (node (ref "U13") (pin "L20") (pinfunction "VDD_L20") (pintype "passive"))
      (node (ref "U13") (pin "L22") (pinfunction "VDD_L22") (pintype "passive"))
      (node (ref "U13") (pin "L24") (pinfunction "VDD_L24") (pintype "passive"))
      (node (ref "U13") (pin "L26") (pinfunction "VDD_L26") (pintype "passive"))
      (node (ref "U13") (pin "L28") (pinfunction "VDD_L28") (pintype "passive"))
      (node (ref "U13") (pin "L30") (pinfunction "VDD_L30") (pintype "passive"))
      (node (ref "U13") (pin "L4") (pinfunction "VDD_L4") (pintype "passive"))
      (node (ref "U13") (pin "L6") (pinfunction "VDD_L6") (pintype "passive"))
      (node (ref "U13") (pin "L8") (pinfunction "VDD_L8") (pintype "passive"))
      (node (ref "U13") (pin "M1") (pinfunction "VDD_M1") (pintype "passive"))
      (node (ref "U13") (pin "M11") (pinfunction "VDD_M11") (pintype "passive"))
      (node (ref "U13") (pin "M13") (pinfunction "VDD_M13") (pintype "passive"))
      (node (ref "U13") (pin "M15") (pinfunction "VDD_M15") (pintype "passive"))
      (node (ref "U13") (pin "M17") (pinfunction "VDD_M17") (pintype "passive"))
      (node (ref "U13") (pin "M19") (pinfunction "VDD_M19") (pintype "passive"))
      (node (ref "U13") (pin "M21") (pinfunction "VDD_M21") (pintype "passive"))
      (node (ref "U13") (pin "M23") (pinfunction "VDD_M23") (pintype "passive"))
      (node (ref "U13") (pin "M25") (pinfunction "VDD_M25") (pintype "passive"))
      (node (ref "U13") (pin "M27") (pinfunction "VDD_M27") (pintype "passive"))
      (node (ref "U13") (pin "M29") (pinfunction "VDD_M29") (pintype "passive"))
      (node (ref "U13") (pin "M3") (pinfunction "VDD_M3") (pintype "passive"))
      (node (ref "U13") (pin "M5") (pinfunction "VDD_M5") (pintype "passive"))
      (node (ref "U13") (pin "M7") (pinfunction "VDD_M7") (pintype "passive"))
      (node (ref "U13") (pin "M9") (pinfunction "VDD_M9") (pintype "passive"))
      (node (ref "U13") (pin "N10") (pinfunction "VDD_N10") (pintype "passive"))
      (node (ref "U13") (pin "N12") (pinfunction "VDD_N12") (pintype "passive"))
      (node (ref "U13") (pin "N14") (pinfunction "VDD_N14") (pintype "passive"))
      (node (ref "U13") (pin "N16") (pinfunction "VDD_N16") (pintype "passive"))
      (node (ref "U13") (pin "N18") (pinfunction "VDD_N18") (pintype "passive"))
      (node (ref "U13") (pin "N2") (pinfunction "VDD_N2") (pintype "passive"))
      (node (ref "U13") (pin "N20") (pinfunction "VDD_N20") (pintype "passive"))
      (node (ref "U13") (pin "N22") (pinfunction "VDD_N22") (pintype "passive"))
      (node (ref "U13") (pin "N24") (pinfunction "VDD_N24") (pintype "passive"))
      (node (ref "U13") (pin "N26") (pinfunction "VDD_N26") (pintype "passive"))
      (node (ref "U13") (pin "N28") (pinfunction "VDD_N28") (pintype "passive"))
      (node (ref "U13") (pin "N30") (pinfunction "VDD_N30") (pintype "passive"))
      (node (ref "U13") (pin "N4") (pinfunction "VDD_N4") (pintype "passive"))
      (node (ref "U13") (pin "N6") (pinfunction "VDD_N6") (pintype "passive"))
      (node (ref "U13") (pin "N8") (pinfunction "VDD_N8") (pintype "passive"))
      (node (ref "U13") (pin "P1") (pinfunction "VDD_P1") (pintype "passive"))
      (node (ref "U13") (pin "P11") (pinfunction "VDD_P11") (pintype "passive"))
      (node (ref "U13") (pin "P13") (pinfunction "VDD_P13") (pintype "passive"))
      (node (ref "U13") (pin "P15") (pinfunction "VDD_P15") (pintype "passive"))
      (node (ref "U13") (pin "P17") (pinfunction "VDD_P17") (pintype "passive"))
      (node (ref "U13") (pin "P19") (pinfunction "VDD_P19") (pintype "passive"))
      (node (ref "U13") (pin "P21") (pinfunction "VDD_P21") (pintype "passive"))
      (node (ref "U13") (pin "P23") (pinfunction "VDD_P23") (pintype "passive"))
      (node (ref "U13") (pin "P25") (pinfunction "VDD_P25") (pintype "passive"))
      (node (ref "U13") (pin "P27") (pinfunction "VDD_P27") (pintype "passive"))
      (node (ref "U13") (pin "P29") (pinfunction "VDD_P29") (pintype "passive"))
      (node (ref "U13") (pin "P3") (pinfunction "VDD_P3") (pintype "passive"))
      (node (ref "U13") (pin "P5") (pinfunction "VDD_P5") (pintype "passive"))
      (node (ref "U13") (pin "P7") (pinfunction "VDD_P7") (pintype "passive"))
      (node (ref "U13") (pin "P9") (pinfunction "VDD_P9") (pintype "passive"))
      (node (ref "U13") (pin "R10") (pinfunction "VDD_R10") (pintype "passive"))
      (node (ref "U13") (pin "R12") (pinfunction "VDD_R12") (pintype "passive"))
      (node (ref "U13") (pin "R14") (pinfunction "VDD_R14") (pintype "passive"))
      (node (ref "U13") (pin "R16") (pinfunction "VDD_R16") (pintype "passive"))
      (node (ref "U13") (pin "R18") (pinfunction "VDD_R18") (pintype "passive"))
      (node (ref "U13") (pin "R2") (pinfunction "VDD_R2") (pintype "passive"))
      (node (ref "U13") (pin "R20") (pinfunction "VDD_R20") (pintype "passive"))
      (node (ref "U13") (pin "R22") (pinfunction "VDD_R22") (pintype "passive"))
      (node (ref "U13") (pin "R24") (pinfunction "VDD_R24") (pintype "passive"))
      (node (ref "U13") (pin "R26") (pinfunction "VDD_R26") (pintype "passive"))
      (node (ref "U13") (pin "R28") (pinfunction "VDD_R28") (pintype "passive"))
      (node (ref "U13") (pin "R30") (pinfunction "VDD_R30") (pintype "passive"))
      (node (ref "U13") (pin "R4") (pinfunction "VDD_R4") (pintype "passive"))
      (node (ref "U13") (pin "R6") (pinfunction "VDD_R6") (pintype "passive"))
      (node (ref "U13") (pin "R8") (pinfunction "VDD_R8") (pintype "passive"))
      (node (ref "U13") (pin "T1") (pinfunction "VDD_T1") (pintype "passive"))
      (node (ref "U13") (pin "T11") (pinfunction "VDD_T11") (pintype "passive"))
      (node (ref "U13") (pin "T13") (pinfunction "VDD_T13") (pintype "passive"))
      (node (ref "U13") (pin "T15") (pinfunction "VDD_T15") (pintype "passive"))
      (node (ref "U13") (pin "T17") (pinfunction "VDD_T17") (pintype "passive"))
      (node (ref "U13") (pin "T19") (pinfunction "VDD_T19") (pintype "passive"))
      (node (ref "U13") (pin "T21") (pinfunction "VDD_T21") (pintype "passive"))
      (node (ref "U13") (pin "T23") (pinfunction "VDD_T23") (pintype "passive"))
      (node (ref "U13") (pin "T25") (pinfunction "VDD_T25") (pintype "passive"))
      (node (ref "U13") (pin "T27") (pinfunction "VDD_T27") (pintype "passive"))
      (node (ref "U13") (pin "T29") (pinfunction "VDD_T29") (pintype "passive"))
      (node (ref "U13") (pin "T3") (pinfunction "VDD_T3") (pintype "passive"))
      (node (ref "U13") (pin "T5") (pinfunction "VDD_T5") (pintype "passive"))
      (node (ref "U13") (pin "T7") (pinfunction "VDD_T7") (pintype "passive"))
      (node (ref "U13") (pin "T9") (pinfunction "VDD_T9") (pintype "passive"))
      (node (ref "U13") (pin "U10") (pinfunction "VDD_U10") (pintype "passive"))
      (node (ref "U13") (pin "U12") (pinfunction "VDD_U12") (pintype "passive"))
      (node (ref "U13") (pin "U14") (pinfunction "VDD_U14") (pintype "passive"))
      (node (ref "U13") (pin "U16") (pinfunction "VDD_U16") (pintype "passive"))
      (node (ref "U13") (pin "U18") (pinfunction "VDD_U18") (pintype "passive"))
      (node (ref "U13") (pin "U2") (pinfunction "VDD_U2") (pintype "passive"))
      (node (ref "U13") (pin "U20") (pinfunction "VDD_U20") (pintype "passive"))
      (node (ref "U13") (pin "U22") (pinfunction "VDD_U22") (pintype "passive"))
      (node (ref "U13") (pin "U24") (pinfunction "VDD_U24") (pintype "passive"))
      (node (ref "U13") (pin "U26") (pinfunction "VDD_U26") (pintype "passive"))
      (node (ref "U13") (pin "U28") (pinfunction "VDD_U28") (pintype "passive"))
      (node (ref "U13") (pin "U30") (pinfunction "VDD_U30") (pintype "passive"))
      (node (ref "U13") (pin "U4") (pinfunction "VDD_U4") (pintype "passive"))
      (node (ref "U13") (pin "U6") (pinfunction "VDD_U6") (pintype "passive"))
      (node (ref "U13") (pin "U8") (pinfunction "VDD_U8") (pintype "passive"))
      (node (ref "U13") (pin "V1") (pinfunction "VDD_V1") (pintype "passive"))
      (node (ref "U13") (pin "V11") (pinfunction "VDD_V11") (pintype "passive"))
      (node (ref "U13") (pin "V13") (pinfunction "VDD_V13") (pintype "passive"))
      (node (ref "U13") (pin "V15") (pinfunction "VDD_V15") (pintype "passive"))
      (node (ref "U13") (pin "V17") (pinfunction "VDD_V17") (pintype "passive"))
      (node (ref "U13") (pin "V19") (pinfunction "VDD_V19") (pintype "passive"))
      (node (ref "U13") (pin "V21") (pinfunction "VDD_V21") (pintype "passive"))
      (node (ref "U13") (pin "V23") (pinfunction "VDD_V23") (pintype "passive"))
      (node (ref "U13") (pin "V25") (pinfunction "VDD_V25") (pintype "passive"))
      (node (ref "U13") (pin "V27") (pinfunction "VDD_V27") (pintype "passive"))
      (node (ref "U13") (pin "V29") (pinfunction "VDD_V29") (pintype "passive"))
      (node (ref "U13") (pin "V3") (pinfunction "VDD_V3") (pintype "passive"))
      (node (ref "U13") (pin "V5") (pinfunction "VDD_V5") (pintype "passive"))
      (node (ref "U13") (pin "V7") (pinfunction "VDD_V7") (pintype "passive"))
      (node (ref "U13") (pin "V9") (pinfunction "VDD_V9") (pintype "passive"))
      (node (ref "U13") (pin "W10") (pinfunction "VDD_W10") (pintype "passive"))
      (node (ref "U13") (pin "W12") (pinfunction "VDD_W12") (pintype "passive"))
      (node (ref "U13") (pin "W14") (pinfunction "VDD_W14") (pintype "passive"))
      (node (ref "U13") (pin "W16") (pinfunction "VDD_W16") (pintype "passive"))
      (node (ref "U13") (pin "W18") (pinfunction "VDD_W18") (pintype "passive"))
      (node (ref "U13") (pin "W2") (pinfunction "VDD_W2") (pintype "passive"))
      (node (ref "U13") (pin "W20") (pinfunction "VDD_W20") (pintype "passive"))
      (node (ref "U13") (pin "W22") (pinfunction "VDD_W22") (pintype "passive"))
      (node (ref "U13") (pin "W24") (pinfunction "VDD_W24") (pintype "passive"))
      (node (ref "U13") (pin "W26") (pinfunction "VDD_W26") (pintype "passive"))
      (node (ref "U13") (pin "W28") (pinfunction "VDD_W28") (pintype "passive"))
      (node (ref "U13") (pin "W30") (pinfunction "VDD_W30") (pintype "passive"))
      (node (ref "U13") (pin "W4") (pinfunction "VDD_W4") (pintype "passive"))
      (node (ref "U13") (pin "W6") (pinfunction "VDD_W6") (pintype "passive"))
      (node (ref "U13") (pin "W8") (pinfunction "VDD_W8") (pintype "passive"))
      (node (ref "U13") (pin "Y1") (pinfunction "VDD_Y1") (pintype "passive"))
      (node (ref "U13") (pin "Y11") (pinfunction "VDD_Y11") (pintype "passive"))
      (node (ref "U13") (pin "Y13") (pinfunction "VDD_Y13") (pintype "passive"))
      (node (ref "U13") (pin "Y15") (pinfunction "VDD_Y15") (pintype "passive"))
      (node (ref "U13") (pin "Y17") (pinfunction "VDD_Y17") (pintype "passive"))
      (node (ref "U13") (pin "Y19") (pinfunction "VDD_Y19") (pintype "passive"))
      (node (ref "U13") (pin "Y21") (pinfunction "VDD_Y21") (pintype "passive"))
      (node (ref "U13") (pin "Y23") (pinfunction "VDD_Y23") (pintype "passive"))
      (node (ref "U13") (pin "Y25") (pinfunction "VDD_Y25") (pintype "passive"))
      (node (ref "U13") (pin "Y27") (pinfunction "VDD_Y27") (pintype "passive"))
      (node (ref "U13") (pin "Y29") (pinfunction "VDD_Y29") (pintype "passive"))
      (node (ref "U13") (pin "Y3") (pinfunction "VDD_Y3") (pintype "passive"))
      (node (ref "U13") (pin "Y5") (pinfunction "VDD_Y5") (pintype "passive"))
      (node (ref "U13") (pin "Y7") (pinfunction "VDD_Y7") (pintype "passive"))
      (node (ref "U13") (pin "Y9") (pinfunction "VDD_Y9") (pintype "passive"))
      (node (ref "U2") (pin "A10") (pinfunction "VDD_A10") (pintype "passive"))
      (node (ref "U2") (pin "A12") (pinfunction "VDD_A12") (pintype "passive"))
      (node (ref "U2") (pin "A14") (pinfunction "VDD_A14") (pintype "passive"))
      (node (ref "U2") (pin "A16") (pinfunction "VDD_A16") (pintype "passive"))
      (node (ref "U2") (pin "A18") (pinfunction "VDD_A18") (pintype "passive"))
      (node (ref "U2") (pin "A2") (pinfunction "VDD_A2") (pintype "passive"))
      (node (ref "U2") (pin "A20") (pinfunction "VDD_A20") (pintype "passive"))
      (node (ref "U2") (pin "A22") (pinfunction "VDD_A22") (pintype "passive"))
      (node (ref "U2") (pin "A24") (pinfunction "VDD_A24") (pintype "passive"))
      (node (ref "U2") (pin "A26") (pinfunction "VDD_A26") (pintype "passive"))
      (node (ref "U2") (pin "A28") (pinfunction "VDD_A28") (pintype "passive"))
      (node (ref "U2") (pin "A30") (pinfunction "VDD_A30") (pintype "passive"))
      (node (ref "U2") (pin "A4") (pinfunction "VDD_A4") (pintype "passive"))
      (node (ref "U2") (pin "A6") (pinfunction "VDD_A6") (pintype "passive"))
      (node (ref "U2") (pin "A8") (pinfunction "VDD_A8") (pintype "passive"))
      (node (ref "U2") (pin "AA10") (pinfunction "VDD_AA10") (pintype "passive"))
      (node (ref "U2") (pin "AA12") (pinfunction "VDD_AA12") (pintype "passive"))
      (node (ref "U2") (pin "AA14") (pinfunction "VDD_AA14") (pintype "passive"))
      (node (ref "U2") (pin "AA16") (pinfunction "VDD_AA16") (pintype "passive"))
      (node (ref "U2") (pin "AA18") (pinfunction "VDD_AA18") (pintype "passive"))
      (node (ref "U2") (pin "AA2") (pinfunction "VDD_AA2") (pintype "passive"))
      (node (ref "U2") (pin "AA20") (pinfunction "VDD_AA20") (pintype "passive"))
      (node (ref "U2") (pin "AA22") (pinfunction "VDD_AA22") (pintype "passive"))
      (node (ref "U2") (pin "AA24") (pinfunction "VDD_AA24") (pintype "passive"))
      (node (ref "U2") (pin "AA26") (pinfunction "VDD_AA26") (pintype "passive"))
      (node (ref "U2") (pin "AA28") (pinfunction "VDD_AA28") (pintype "passive"))
      (node (ref "U2") (pin "AA30") (pinfunction "VDD_AA30") (pintype "passive"))
      (node (ref "U2") (pin "AA4") (pinfunction "VDD_AA4") (pintype "passive"))
      (node (ref "U2") (pin "AA6") (pinfunction "VDD_AA6") (pintype "passive"))
      (node (ref "U2") (pin "AA8") (pinfunction "VDD_AA8") (pintype "passive"))
      (node (ref "U2") (pin "AB1") (pinfunction "VDD_AB1") (pintype "passive"))
      (node (ref "U2") (pin "AB11") (pinfunction "VDD_AB11") (pintype "passive"))
      (node (ref "U2") (pin "AB13") (pinfunction "VDD_AB13") (pintype "passive"))
      (node (ref "U2") (pin "AB15") (pinfunction "VDD_AB15") (pintype "passive"))
      (node (ref "U2") (pin "AB17") (pinfunction "VDD_AB17") (pintype "passive"))
      (node (ref "U2") (pin "AB19") (pinfunction "VDD_AB19") (pintype "passive"))
      (node (ref "U2") (pin "AB21") (pinfunction "VDD_AB21") (pintype "passive"))
      (node (ref "U2") (pin "AB23") (pinfunction "VDD_AB23") (pintype "passive"))
      (node (ref "U2") (pin "AB25") (pinfunction "VDD_AB25") (pintype "passive"))
      (node (ref "U2") (pin "AB27") (pinfunction "VDD_AB27") (pintype "passive"))
      (node (ref "U2") (pin "AB29") (pinfunction "VDD_AB29") (pintype "passive"))
      (node (ref "U2") (pin "AB3") (pinfunction "VDD_AB3") (pintype "passive"))
      (node (ref "U2") (pin "AB5") (pinfunction "VDD_AB5") (pintype "passive"))
      (node (ref "U2") (pin "AB7") (pinfunction "VDD_AB7") (pintype "passive"))
      (node (ref "U2") (pin "AB9") (pinfunction "VDD_AB9") (pintype "passive"))
      (node (ref "U2") (pin "AC10") (pinfunction "VDD_AC10") (pintype "passive"))
      (node (ref "U2") (pin "AC12") (pinfunction "VDD_AC12") (pintype "passive"))
      (node (ref "U2") (pin "AC14") (pinfunction "VDD_AC14") (pintype "passive"))
      (node (ref "U2") (pin "AC16") (pinfunction "VDD_AC16") (pintype "passive"))
      (node (ref "U2") (pin "AC18") (pinfunction "VDD_AC18") (pintype "passive"))
      (node (ref "U2") (pin "AC2") (pinfunction "VDD_AC2") (pintype "passive"))
      (node (ref "U2") (pin "AC20") (pinfunction "VDD_AC20") (pintype "passive"))
      (node (ref "U2") (pin "AC22") (pinfunction "VDD_AC22") (pintype "passive"))
      (node (ref "U2") (pin "AC24") (pinfunction "VDD_AC24") (pintype "passive"))
      (node (ref "U2") (pin "AC26") (pinfunction "VDD_AC26") (pintype "passive"))
      (node (ref "U2") (pin "AC28") (pinfunction "VDD_AC28") (pintype "passive"))
      (node (ref "U2") (pin "AC30") (pinfunction "VDD_AC30") (pintype "passive"))
      (node (ref "U2") (pin "AC4") (pinfunction "VDD_AC4") (pintype "passive"))
      (node (ref "U2") (pin "AC6") (pinfunction "VDD_AC6") (pintype "passive"))
      (node (ref "U2") (pin "AC8") (pinfunction "VDD_AC8") (pintype "passive"))
      (node (ref "U2") (pin "AD1") (pinfunction "VDD_AD1") (pintype "passive"))
      (node (ref "U2") (pin "AD11") (pinfunction "VDD_AD11") (pintype "passive"))
      (node (ref "U2") (pin "AD13") (pinfunction "VDD_AD13") (pintype "passive"))
      (node (ref "U2") (pin "AD15") (pinfunction "VDD_AD15") (pintype "passive"))
      (node (ref "U2") (pin "AD17") (pinfunction "VDD_AD17") (pintype "passive"))
      (node (ref "U2") (pin "AD19") (pinfunction "VDD_AD19") (pintype "passive"))
      (node (ref "U2") (pin "AD21") (pinfunction "VDD_AD21") (pintype "passive"))
      (node (ref "U2") (pin "AD23") (pinfunction "VDD_AD23") (pintype "passive"))
      (node (ref "U2") (pin "AD25") (pinfunction "VDD_AD25") (pintype "passive"))
      (node (ref "U2") (pin "AD27") (pinfunction "VDD_AD27") (pintype "passive"))
      (node (ref "U2") (pin "AD29") (pinfunction "VDD_AD29") (pintype "passive"))
      (node (ref "U2") (pin "AD3") (pinfunction "VDD_AD3") (pintype "passive"))
      (node (ref "U2") (pin "AD5") (pinfunction "VDD_AD5") (pintype "passive"))
      (node (ref "U2") (pin "AD7") (pinfunction "VDD_AD7") (pintype "passive"))
      (node (ref "U2") (pin "AD9") (pinfunction "VDD_AD9") (pintype "passive"))
      (node (ref "U2") (pin "AE10") (pinfunction "VDD_AE10") (pintype "passive"))
      (node (ref "U2") (pin "AE12") (pinfunction "VDD_AE12") (pintype "passive"))
      (node (ref "U2") (pin "AE14") (pinfunction "VDD_AE14") (pintype "passive"))
      (node (ref "U2") (pin "AE16") (pinfunction "VDD_AE16") (pintype "passive"))
      (node (ref "U2") (pin "AE18") (pinfunction "VDD_AE18") (pintype "passive"))
      (node (ref "U2") (pin "AE2") (pinfunction "VDD_AE2") (pintype "passive"))
      (node (ref "U2") (pin "AE20") (pinfunction "VDD_AE20") (pintype "passive"))
      (node (ref "U2") (pin "AE22") (pinfunction "VDD_AE22") (pintype "passive"))
      (node (ref "U2") (pin "AE24") (pinfunction "VDD_AE24") (pintype "passive"))
      (node (ref "U2") (pin "AE26") (pinfunction "VDD_AE26") (pintype "passive"))
      (node (ref "U2") (pin "AE28") (pinfunction "VDD_AE28") (pintype "passive"))
      (node (ref "U2") (pin "AE30") (pinfunction "VDD_AE30") (pintype "passive"))
      (node (ref "U2") (pin "AE4") (pinfunction "VDD_AE4") (pintype "passive"))
      (node (ref "U2") (pin "AE6") (pinfunction "VDD_AE6") (pintype "passive"))
      (node (ref "U2") (pin "AE8") (pinfunction "VDD_AE8") (pintype "passive"))
      (node (ref "U2") (pin "AF1") (pinfunction "VDD_AF1") (pintype "passive"))
      (node (ref "U2") (pin "AF11") (pinfunction "VDD_AF11") (pintype "passive"))
      (node (ref "U2") (pin "AF13") (pinfunction "VDD_AF13") (pintype "passive"))
      (node (ref "U2") (pin "AF15") (pinfunction "VDD_AF15") (pintype "passive"))
      (node (ref "U2") (pin "AF17") (pinfunction "VDD_AF17") (pintype "passive"))
      (node (ref "U2") (pin "AF19") (pinfunction "VDD_AF19") (pintype "passive"))
      (node (ref "U2") (pin "AF21") (pinfunction "VDD_AF21") (pintype "passive"))
      (node (ref "U2") (pin "AF23") (pinfunction "VDD_AF23") (pintype "passive"))
      (node (ref "U2") (pin "AF25") (pinfunction "VDD_AF25") (pintype "passive"))
      (node (ref "U2") (pin "AF27") (pinfunction "VDD_AF27") (pintype "passive"))
      (node (ref "U2") (pin "AF29") (pinfunction "VDD_AF29") (pintype "passive"))
      (node (ref "U2") (pin "AF3") (pinfunction "VDD_AF3") (pintype "passive"))
      (node (ref "U2") (pin "AF5") (pinfunction "VDD_AF5") (pintype "passive"))
      (node (ref "U2") (pin "AF7") (pinfunction "VDD_AF7") (pintype "passive"))
      (node (ref "U2") (pin "AF9") (pinfunction "VDD_AF9") (pintype "passive"))
      (node (ref "U2") (pin "AG10") (pinfunction "VDD_AG10") (pintype "passive"))
      (node (ref "U2") (pin "AG12") (pinfunction "VDD_AG12") (pintype "passive"))
      (node (ref "U2") (pin "AG14") (pinfunction "VDD_AG14") (pintype "passive"))
      (node (ref "U2") (pin "AG16") (pinfunction "VDD_AG16") (pintype "passive"))
      (node (ref "U2") (pin "AG18") (pinfunction "VDD_AG18") (pintype "passive"))
      (node (ref "U2") (pin "AG2") (pinfunction "VDD_AG2") (pintype "passive"))
      (node (ref "U2") (pin "AG20") (pinfunction "VDD_AG20") (pintype "passive"))
      (node (ref "U2") (pin "AG22") (pinfunction "VDD_AG22") (pintype "passive"))
      (node (ref "U2") (pin "AG24") (pinfunction "VDD_AG24") (pintype "passive"))
      (node (ref "U2") (pin "AG26") (pinfunction "VDD_AG26") (pintype "passive"))
      (node (ref "U2") (pin "AG28") (pinfunction "VDD_AG28") (pintype "passive"))
      (node (ref "U2") (pin "AG30") (pinfunction "VDD_AG30") (pintype "passive"))
      (node (ref "U2") (pin "AG4") (pinfunction "VDD_AG4") (pintype "passive"))
      (node (ref "U2") (pin "AG6") (pinfunction "VDD_AG6") (pintype "passive"))
      (node (ref "U2") (pin "AG8") (pinfunction "VDD_AG8") (pintype "passive"))
      (node (ref "U2") (pin "AH1") (pinfunction "VDD_AH1") (pintype "passive"))
      (node (ref "U2") (pin "AH11") (pinfunction "VDD_AH11") (pintype "passive"))
      (node (ref "U2") (pin "AH13") (pinfunction "VDD_AH13") (pintype "passive"))
      (node (ref "U2") (pin "AH15") (pinfunction "VDD_AH15") (pintype "passive"))
      (node (ref "U2") (pin "AH17") (pinfunction "VDD_AH17") (pintype "passive"))
      (node (ref "U2") (pin "AH19") (pinfunction "VDD_AH19") (pintype "passive"))
      (node (ref "U2") (pin "AH21") (pinfunction "VDD_AH21") (pintype "passive"))
      (node (ref "U2") (pin "AH23") (pinfunction "VDD_AH23") (pintype "passive"))
      (node (ref "U2") (pin "AH25") (pinfunction "VDD_AH25") (pintype "passive"))
      (node (ref "U2") (pin "AH27") (pinfunction "VDD_AH27") (pintype "passive"))
      (node (ref "U2") (pin "AH29") (pinfunction "VDD_AH29") (pintype "passive"))
      (node (ref "U2") (pin "AH3") (pinfunction "VDD_AH3") (pintype "passive"))
      (node (ref "U2") (pin "AH5") (pinfunction "VDD_AH5") (pintype "passive"))
      (node (ref "U2") (pin "AH7") (pinfunction "VDD_AH7") (pintype "passive"))
      (node (ref "U2") (pin "AH9") (pinfunction "VDD_AH9") (pintype "passive"))
      (node (ref "U2") (pin "AJ10") (pinfunction "VDD_AJ10") (pintype "passive"))
      (node (ref "U2") (pin "AJ14") (pinfunction "VDD_AJ14") (pintype "passive"))
      (node (ref "U2") (pin "AJ18") (pinfunction "VDD_AJ18") (pintype "passive"))
      (node (ref "U2") (pin "AJ2") (pinfunction "VDD_AJ2") (pintype "passive"))
      (node (ref "U2") (pin "AJ28") (pinfunction "VDD_AJ28") (pintype "passive"))
      (node (ref "U2") (pin "AJ30") (pinfunction "VDD_AJ30") (pintype "passive"))
      (node (ref "U2") (pin "AK1") (pinfunction "VDD_AK1") (pintype "passive"))
      (node (ref "U2") (pin "AK26") (pinfunction "VDD_AK26") (pintype "passive"))
      (node (ref "U2") (pin "AK29") (pinfunction "VDD_AK29") (pintype "passive"))
      (node (ref "U2") (pin "B1") (pinfunction "VDD_B1") (pintype "passive"))
      (node (ref "U2") (pin "B11") (pinfunction "VDD_B11") (pintype "passive"))
      (node (ref "U2") (pin "B13") (pinfunction "VDD_B13") (pintype "passive"))
      (node (ref "U2") (pin "B15") (pinfunction "VDD_B15") (pintype "passive"))
      (node (ref "U2") (pin "B17") (pinfunction "VDD_B17") (pintype "passive"))
      (node (ref "U2") (pin "B19") (pinfunction "VDD_B19") (pintype "passive"))
      (node (ref "U2") (pin "B21") (pinfunction "VDD_B21") (pintype "passive"))
      (node (ref "U2") (pin "B23") (pinfunction "VDD_B23") (pintype "passive"))
      (node (ref "U2") (pin "B25") (pinfunction "VDD_B25") (pintype "passive"))
      (node (ref "U2") (pin "B27") (pinfunction "VDD_B27") (pintype "passive"))
      (node (ref "U2") (pin "B29") (pinfunction "VDD_B29") (pintype "passive"))
      (node (ref "U2") (pin "B3") (pinfunction "VDD_B3") (pintype "passive"))
      (node (ref "U2") (pin "B5") (pinfunction "VDD_B5") (pintype "passive"))
      (node (ref "U2") (pin "B7") (pinfunction "VDD_B7") (pintype "passive"))
      (node (ref "U2") (pin "B9") (pinfunction "VDD_B9") (pintype "passive"))
      (node (ref "U2") (pin "C10") (pinfunction "VDD_C10") (pintype "passive"))
      (node (ref "U2") (pin "C12") (pinfunction "VDD_C12") (pintype "passive"))
      (node (ref "U2") (pin "C14") (pinfunction "VDD_C14") (pintype "passive"))
      (node (ref "U2") (pin "C16") (pinfunction "VDD_C16") (pintype "passive"))
      (node (ref "U2") (pin "C18") (pinfunction "VDD_C18") (pintype "passive"))
      (node (ref "U2") (pin "C2") (pinfunction "VDD_C2") (pintype "passive"))
      (node (ref "U2") (pin "C20") (pinfunction "VDD_C20") (pintype "passive"))
      (node (ref "U2") (pin "C22") (pinfunction "VDD_C22") (pintype "passive"))
      (node (ref "U2") (pin "C24") (pinfunction "VDD_C24") (pintype "passive"))
      (node (ref "U2") (pin "C26") (pinfunction "VDD_C26") (pintype "passive"))
      (node (ref "U2") (pin "C28") (pinfunction "VDD_C28") (pintype "passive"))
      (node (ref "U2") (pin "C30") (pinfunction "VDD_C30") (pintype "passive"))
      (node (ref "U2") (pin "C4") (pinfunction "VDD_C4") (pintype "passive"))
      (node (ref "U2") (pin "C6") (pinfunction "VDD_C6") (pintype "passive"))
      (node (ref "U2") (pin "C8") (pinfunction "VDD_C8") (pintype "passive"))
      (node (ref "U2") (pin "D1") (pinfunction "VDD_D1") (pintype "passive"))
      (node (ref "U2") (pin "D11") (pinfunction "VDD_D11") (pintype "passive"))
      (node (ref "U2") (pin "D13") (pinfunction "VDD_D13") (pintype "passive"))
      (node (ref "U2") (pin "D15") (pinfunction "VDD_D15") (pintype "passive"))
      (node (ref "U2") (pin "D17") (pinfunction "VDD_D17") (pintype "passive"))
      (node (ref "U2") (pin "D19") (pinfunction "VDD_D19") (pintype "passive"))
      (node (ref "U2") (pin "D21") (pinfunction "VDD_D21") (pintype "passive"))
      (node (ref "U2") (pin "D23") (pinfunction "VDD_D23") (pintype "passive"))
      (node (ref "U2") (pin "D25") (pinfunction "VDD_D25") (pintype "passive"))
      (node (ref "U2") (pin "D27") (pinfunction "VDD_D27") (pintype "passive"))
      (node (ref "U2") (pin "D29") (pinfunction "VDD_D29") (pintype "passive"))
      (node (ref "U2") (pin "D3") (pinfunction "VDD_D3") (pintype "passive"))
      (node (ref "U2") (pin "D5") (pinfunction "VDD_D5") (pintype "passive"))
      (node (ref "U2") (pin "D7") (pinfunction "VDD_D7") (pintype "passive"))
      (node (ref "U2") (pin "D9") (pinfunction "VDD_D9") (pintype "passive"))
      (node (ref "U2") (pin "E10") (pinfunction "VDD_E10") (pintype "passive"))
      (node (ref "U2") (pin "E12") (pinfunction "VDD_E12") (pintype "passive"))
      (node (ref "U2") (pin "E14") (pinfunction "VDD_E14") (pintype "passive"))
      (node (ref "U2") (pin "E16") (pinfunction "VDD_E16") (pintype "passive"))
      (node (ref "U2") (pin "E18") (pinfunction "VDD_E18") (pintype "passive"))
      (node (ref "U2") (pin "E2") (pinfunction "VDD_E2") (pintype "passive"))
      (node (ref "U2") (pin "E20") (pinfunction "VDD_E20") (pintype "passive"))
      (node (ref "U2") (pin "E22") (pinfunction "VDD_E22") (pintype "passive"))
      (node (ref "U2") (pin "E24") (pinfunction "VDD_E24") (pintype "passive"))
      (node (ref "U2") (pin "E26") (pinfunction "VDD_E26") (pintype "passive"))
      (node (ref "U2") (pin "E28") (pinfunction "VDD_E28") (pintype "passive"))
      (node (ref "U2") (pin "E30") (pinfunction "VDD_E30") (pintype "passive"))
      (node (ref "U2") (pin "E4") (pinfunction "VDD_E4") (pintype "passive"))
      (node (ref "U2") (pin "E6") (pinfunction "VDD_E6") (pintype "passive"))
      (node (ref "U2") (pin "E8") (pinfunction "VDD_E8") (pintype "passive"))
      (node (ref "U2") (pin "F1") (pinfunction "VDD_F1") (pintype "passive"))
      (node (ref "U2") (pin "F11") (pinfunction "VDD_F11") (pintype "passive"))
      (node (ref "U2") (pin "F13") (pinfunction "VDD_F13") (pintype "passive"))
      (node (ref "U2") (pin "F15") (pinfunction "VDD_F15") (pintype "passive"))
      (node (ref "U2") (pin "F17") (pinfunction "VDD_F17") (pintype "passive"))
      (node (ref "U2") (pin "F19") (pinfunction "VDD_F19") (pintype "passive"))
      (node (ref "U2") (pin "F21") (pinfunction "VDD_F21") (pintype "passive"))
      (node (ref "U2") (pin "F23") (pinfunction "VDD_F23") (pintype "passive"))
      (node (ref "U2") (pin "F25") (pinfunction "VDD_F25") (pintype "passive"))
      (node (ref "U2") (pin "F27") (pinfunction "VDD_F27") (pintype "passive"))
      (node (ref "U2") (pin "F29") (pinfunction "VDD_F29") (pintype "passive"))
      (node (ref "U2") (pin "F3") (pinfunction "VDD_F3") (pintype "passive"))
      (node (ref "U2") (pin "F5") (pinfunction "VDD_F5") (pintype "passive"))
      (node (ref "U2") (pin "F7") (pinfunction "VDD_F7") (pintype "passive"))
      (node (ref "U2") (pin "F9") (pinfunction "VDD_F9") (pintype "passive"))
      (node (ref "U2") (pin "G10") (pinfunction "VDD_G10") (pintype "passive"))
      (node (ref "U2") (pin "G12") (pinfunction "VDD_G12") (pintype "passive"))
      (node (ref "U2") (pin "G14") (pinfunction "VDD_G14") (pintype "passive"))
      (node (ref "U2") (pin "G16") (pinfunction "VDD_G16") (pintype "passive"))
      (node (ref "U2") (pin "G18") (pinfunction "VDD_G18") (pintype "passive"))
      (node (ref "U2") (pin "G2") (pinfunction "VDD_G2") (pintype "passive"))
      (node (ref "U2") (pin "G20") (pinfunction "VDD_G20") (pintype "passive"))
      (node (ref "U2") (pin "G22") (pinfunction "VDD_G22") (pintype "passive"))
      (node (ref "U2") (pin "G24") (pinfunction "VDD_G24") (pintype "passive"))
      (node (ref "U2") (pin "G26") (pinfunction "VDD_G26") (pintype "passive"))
      (node (ref "U2") (pin "G28") (pinfunction "VDD_G28") (pintype "passive"))
      (node (ref "U2") (pin "G30") (pinfunction "VDD_G30") (pintype "passive"))
      (node (ref "U2") (pin "G4") (pinfunction "VDD_G4") (pintype "passive"))
      (node (ref "U2") (pin "G6") (pinfunction "VDD_G6") (pintype "passive"))
      (node (ref "U2") (pin "G8") (pinfunction "VDD_G8") (pintype "passive"))
      (node (ref "U2") (pin "H1") (pinfunction "VDD_H1") (pintype "passive"))
      (node (ref "U2") (pin "H11") (pinfunction "VDD_H11") (pintype "passive"))
      (node (ref "U2") (pin "H13") (pinfunction "VDD_H13") (pintype "passive"))
      (node (ref "U2") (pin "H15") (pinfunction "VDD_H15") (pintype "passive"))
      (node (ref "U2") (pin "H17") (pinfunction "VDD_H17") (pintype "passive"))
      (node (ref "U2") (pin "H19") (pinfunction "VDD_H19") (pintype "passive"))
      (node (ref "U2") (pin "H21") (pinfunction "VDD_H21") (pintype "passive"))
      (node (ref "U2") (pin "H23") (pinfunction "VDD_H23") (pintype "passive"))
      (node (ref "U2") (pin "H25") (pinfunction "VDD_H25") (pintype "passive"))
      (node (ref "U2") (pin "H27") (pinfunction "VDD_H27") (pintype "passive"))
      (node (ref "U2") (pin "H29") (pinfunction "VDD_H29") (pintype "passive"))
      (node (ref "U2") (pin "H3") (pinfunction "VDD_H3") (pintype "passive"))
      (node (ref "U2") (pin "H5") (pinfunction "VDD_H5") (pintype "passive"))
      (node (ref "U2") (pin "H7") (pinfunction "VDD_H7") (pintype "passive"))
      (node (ref "U2") (pin "H9") (pinfunction "VDD_H9") (pintype "passive"))
      (node (ref "U2") (pin "J10") (pinfunction "VDD_J10") (pintype "passive"))
      (node (ref "U2") (pin "J12") (pinfunction "VDD_J12") (pintype "passive"))
      (node (ref "U2") (pin "J14") (pinfunction "VDD_J14") (pintype "passive"))
      (node (ref "U2") (pin "J16") (pinfunction "VDD_J16") (pintype "passive"))
      (node (ref "U2") (pin "J18") (pinfunction "VDD_J18") (pintype "passive"))
      (node (ref "U2") (pin "J2") (pinfunction "VDD_J2") (pintype "passive"))
      (node (ref "U2") (pin "J20") (pinfunction "VDD_J20") (pintype "passive"))
      (node (ref "U2") (pin "J22") (pinfunction "VDD_J22") (pintype "passive"))
      (node (ref "U2") (pin "J24") (pinfunction "VDD_J24") (pintype "passive"))
      (node (ref "U2") (pin "J26") (pinfunction "VDD_J26") (pintype "passive"))
      (node (ref "U2") (pin "J28") (pinfunction "VDD_J28") (pintype "passive"))
      (node (ref "U2") (pin "J30") (pinfunction "VDD_J30") (pintype "passive"))
      (node (ref "U2") (pin "J4") (pinfunction "VDD_J4") (pintype "passive"))
      (node (ref "U2") (pin "J6") (pinfunction "VDD_J6") (pintype "passive"))
      (node (ref "U2") (pin "J8") (pinfunction "VDD_J8") (pintype "passive"))
      (node (ref "U2") (pin "K1") (pinfunction "VDD_K1") (pintype "passive"))
      (node (ref "U2") (pin "K11") (pinfunction "VDD_K11") (pintype "passive"))
      (node (ref "U2") (pin "K13") (pinfunction "VDD_K13") (pintype "passive"))
      (node (ref "U2") (pin "K15") (pinfunction "VDD_K15") (pintype "passive"))
      (node (ref "U2") (pin "K17") (pinfunction "VDD_K17") (pintype "passive"))
      (node (ref "U2") (pin "K19") (pinfunction "VDD_K19") (pintype "passive"))
      (node (ref "U2") (pin "K21") (pinfunction "VDD_K21") (pintype "passive"))
      (node (ref "U2") (pin "K23") (pinfunction "VDD_K23") (pintype "passive"))
      (node (ref "U2") (pin "K25") (pinfunction "VDD_K25") (pintype "passive"))
      (node (ref "U2") (pin "K27") (pinfunction "VDD_K27") (pintype "passive"))
      (node (ref "U2") (pin "K29") (pinfunction "VDD_K29") (pintype "passive"))
      (node (ref "U2") (pin "K3") (pinfunction "VDD_K3") (pintype "passive"))
      (node (ref "U2") (pin "K5") (pinfunction "VDD_K5") (pintype "passive"))
      (node (ref "U2") (pin "K7") (pinfunction "VDD_K7") (pintype "passive"))
      (node (ref "U2") (pin "K9") (pinfunction "VDD_K9") (pintype "passive"))
      (node (ref "U2") (pin "L10") (pinfunction "VDD_L10") (pintype "passive"))
      (node (ref "U2") (pin "L12") (pinfunction "VDD_L12") (pintype "passive"))
      (node (ref "U2") (pin "L14") (pinfunction "VDD_L14") (pintype "passive"))
      (node (ref "U2") (pin "L16") (pinfunction "VDD_L16") (pintype "passive"))
      (node (ref "U2") (pin "L18") (pinfunction "VDD_L18") (pintype "passive"))
      (node (ref "U2") (pin "L2") (pinfunction "VDD_L2") (pintype "passive"))
      (node (ref "U2") (pin "L20") (pinfunction "VDD_L20") (pintype "passive"))
      (node (ref "U2") (pin "L22") (pinfunction "VDD_L22") (pintype "passive"))
      (node (ref "U2") (pin "L24") (pinfunction "VDD_L24") (pintype "passive"))
      (node (ref "U2") (pin "L26") (pinfunction "VDD_L26") (pintype "passive"))
      (node (ref "U2") (pin "L28") (pinfunction "VDD_L28") (pintype "passive"))
      (node (ref "U2") (pin "L30") (pinfunction "VDD_L30") (pintype "passive"))
      (node (ref "U2") (pin "L4") (pinfunction "VDD_L4") (pintype "passive"))
      (node (ref "U2") (pin "L6") (pinfunction "VDD_L6") (pintype "passive"))
      (node (ref "U2") (pin "L8") (pinfunction "VDD_L8") (pintype "passive"))
      (node (ref "U2") (pin "M1") (pinfunction "VDD_M1") (pintype "passive"))
      (node (ref "U2") (pin "M11") (pinfunction "VDD_M11") (pintype "passive"))
      (node (ref "U2") (pin "M13") (pinfunction "VDD_M13") (pintype "passive"))
      (node (ref "U2") (pin "M15") (pinfunction "VDD_M15") (pintype "passive"))
      (node (ref "U2") (pin "M17") (pinfunction "VDD_M17") (pintype "passive"))
      (node (ref "U2") (pin "M19") (pinfunction "VDD_M19") (pintype "passive"))
      (node (ref "U2") (pin "M21") (pinfunction "VDD_M21") (pintype "passive"))
      (node (ref "U2") (pin "M23") (pinfunction "VDD_M23") (pintype "passive"))
      (node (ref "U2") (pin "M25") (pinfunction "VDD_M25") (pintype "passive"))
      (node (ref "U2") (pin "M27") (pinfunction "VDD_M27") (pintype "passive"))
      (node (ref "U2") (pin "M29") (pinfunction "VDD_M29") (pintype "passive"))
      (node (ref "U2") (pin "M3") (pinfunction "VDD_M3") (pintype "passive"))
      (node (ref "U2") (pin "M5") (pinfunction "VDD_M5") (pintype "passive"))
      (node (ref "U2") (pin "M7") (pinfunction "VDD_M7") (pintype "passive"))
      (node (ref "U2") (pin "M9") (pinfunction "VDD_M9") (pintype "passive"))
      (node (ref "U2") (pin "N10") (pinfunction "VDD_N10") (pintype "passive"))
      (node (ref "U2") (pin "N12") (pinfunction "VDD_N12") (pintype "passive"))
      (node (ref "U2") (pin "N14") (pinfunction "VDD_N14") (pintype "passive"))
      (node (ref "U2") (pin "N16") (pinfunction "VDD_N16") (pintype "passive"))
      (node (ref "U2") (pin "N18") (pinfunction "VDD_N18") (pintype "passive"))
      (node (ref "U2") (pin "N2") (pinfunction "VDD_N2") (pintype "passive"))
      (node (ref "U2") (pin "N20") (pinfunction "VDD_N20") (pintype "passive"))
      (node (ref "U2") (pin "N22") (pinfunction "VDD_N22") (pintype "passive"))
      (node (ref "U2") (pin "N24") (pinfunction "VDD_N24") (pintype "passive"))
      (node (ref "U2") (pin "N26") (pinfunction "VDD_N26") (pintype "passive"))
      (node (ref "U2") (pin "N28") (pinfunction "VDD_N28") (pintype "passive"))
      (node (ref "U2") (pin "N30") (pinfunction "VDD_N30") (pintype "passive"))
      (node (ref "U2") (pin "N4") (pinfunction "VDD_N4") (pintype "passive"))
      (node (ref "U2") (pin "N6") (pinfunction "VDD_N6") (pintype "passive"))
      (node (ref "U2") (pin "N8") (pinfunction "VDD_N8") (pintype "passive"))
      (node (ref "U2") (pin "P1") (pinfunction "VDD_P1") (pintype "passive"))
      (node (ref "U2") (pin "P11") (pinfunction "VDD_P11") (pintype "passive"))
      (node (ref "U2") (pin "P13") (pinfunction "VDD_P13") (pintype "passive"))
      (node (ref "U2") (pin "P15") (pinfunction "VDD_P15") (pintype "passive"))
      (node (ref "U2") (pin "P17") (pinfunction "VDD_P17") (pintype "passive"))
      (node (ref "U2") (pin "P19") (pinfunction "VDD_P19") (pintype "passive"))
      (node (ref "U2") (pin "P21") (pinfunction "VDD_P21") (pintype "passive"))
      (node (ref "U2") (pin "P23") (pinfunction "VDD_P23") (pintype "passive"))
      (node (ref "U2") (pin "P25") (pinfunction "VDD_P25") (pintype "passive"))
      (node (ref "U2") (pin "P27") (pinfunction "VDD_P27") (pintype "passive"))
      (node (ref "U2") (pin "P29") (pinfunction "VDD_P29") (pintype "passive"))
      (node (ref "U2") (pin "P3") (pinfunction "VDD_P3") (pintype "passive"))
      (node (ref "U2") (pin "P5") (pinfunction "VDD_P5") (pintype "passive"))
      (node (ref "U2") (pin "P7") (pinfunction "VDD_P7") (pintype "passive"))
      (node (ref "U2") (pin "P9") (pinfunction "VDD_P9") (pintype "passive"))
      (node (ref "U2") (pin "R10") (pinfunction "VDD_R10") (pintype "passive"))
      (node (ref "U2") (pin "R12") (pinfunction "VDD_R12") (pintype "passive"))
      (node (ref "U2") (pin "R14") (pinfunction "VDD_R14") (pintype "passive"))
      (node (ref "U2") (pin "R16") (pinfunction "VDD_R16") (pintype "passive"))
      (node (ref "U2") (pin "R18") (pinfunction "VDD_R18") (pintype "passive"))
      (node (ref "U2") (pin "R2") (pinfunction "VDD_R2") (pintype "passive"))
      (node (ref "U2") (pin "R20") (pinfunction "VDD_R20") (pintype "passive"))
      (node (ref "U2") (pin "R22") (pinfunction "VDD_R22") (pintype "passive"))
      (node (ref "U2") (pin "R24") (pinfunction "VDD_R24") (pintype "passive"))
      (node (ref "U2") (pin "R26") (pinfunction "VDD_R26") (pintype "passive"))
      (node (ref "U2") (pin "R28") (pinfunction "VDD_R28") (pintype "passive"))
      (node (ref "U2") (pin "R30") (pinfunction "VDD_R30") (pintype "passive"))
      (node (ref "U2") (pin "R4") (pinfunction "VDD_R4") (pintype "passive"))
      (node (ref "U2") (pin "R6") (pinfunction "VDD_R6") (pintype "passive"))
      (node (ref "U2") (pin "R8") (pinfunction "VDD_R8") (pintype "passive"))
      (node (ref "U2") (pin "T1") (pinfunction "VDD_T1") (pintype "passive"))
      (node (ref "U2") (pin "T11") (pinfunction "VDD_T11") (pintype "passive"))
      (node (ref "U2") (pin "T13") (pinfunction "VDD_T13") (pintype "passive"))
      (node (ref "U2") (pin "T15") (pinfunction "VDD_T15") (pintype "passive"))
      (node (ref "U2") (pin "T17") (pinfunction "VDD_T17") (pintype "passive"))
      (node (ref "U2") (pin "T19") (pinfunction "VDD_T19") (pintype "passive"))
      (node (ref "U2") (pin "T21") (pinfunction "VDD_T21") (pintype "passive"))
      (node (ref "U2") (pin "T23") (pinfunction "VDD_T23") (pintype "passive"))
      (node (ref "U2") (pin "T25") (pinfunction "VDD_T25") (pintype "passive"))
      (node (ref "U2") (pin "T27") (pinfunction "VDD_T27") (pintype "passive"))
      (node (ref "U2") (pin "T29") (pinfunction "VDD_T29") (pintype "passive"))
      (node (ref "U2") (pin "T3") (pinfunction "VDD_T3") (pintype "passive"))
      (node (ref "U2") (pin "T5") (pinfunction "VDD_T5") (pintype "passive"))
      (node (ref "U2") (pin "T7") (pinfunction "VDD_T7") (pintype "passive"))
      (node (ref "U2") (pin "T9") (pinfunction "VDD_T9") (pintype "passive"))
      (node (ref "U2") (pin "U10") (pinfunction "VDD_U10") (pintype "passive"))
      (node (ref "U2") (pin "U12") (pinfunction "VDD_U12") (pintype "passive"))
      (node (ref "U2") (pin "U14") (pinfunction "VDD_U14") (pintype "passive"))
      (node (ref "U2") (pin "U16") (pinfunction "VDD_U16") (pintype "passive"))
      (node (ref "U2") (pin "U18") (pinfunction "VDD_U18") (pintype "passive"))
      (node (ref "U2") (pin "U2") (pinfunction "VDD_U2") (pintype "passive"))
      (node (ref "U2") (pin "U20") (pinfunction "VDD_U20") (pintype "passive"))
      (node (ref "U2") (pin "U22") (pinfunction "VDD_U22") (pintype "passive"))
      (node (ref "U2") (pin "U24") (pinfunction "VDD_U24") (pintype "passive"))
      (node (ref "U2") (pin "U26") (pinfunction "VDD_U26") (pintype "passive"))
      (node (ref "U2") (pin "U28") (pinfunction "VDD_U28") (pintype "passive"))
      (node (ref "U2") (pin "U30") (pinfunction "VDD_U30") (pintype "passive"))
      (node (ref "U2") (pin "U4") (pinfunction "VDD_U4") (pintype "passive"))
      (node (ref "U2") (pin "U6") (pinfunction "VDD_U6") (pintype "passive"))
      (node (ref "U2") (pin "U8") (pinfunction "VDD_U8") (pintype "passive"))
      (node (ref "U2") (pin "V1") (pinfunction "VDD_V1") (pintype "passive"))
      (node (ref "U2") (pin "V11") (pinfunction "VDD_V11") (pintype "passive"))
      (node (ref "U2") (pin "V13") (pinfunction "VDD_V13") (pintype "passive"))
      (node (ref "U2") (pin "V15") (pinfunction "VDD_V15") (pintype "passive"))
      (node (ref "U2") (pin "V17") (pinfunction "VDD_V17") (pintype "passive"))
      (node (ref "U2") (pin "V19") (pinfunction "VDD_V19") (pintype "passive"))
      (node (ref "U2") (pin "V21") (pinfunction "VDD_V21") (pintype "passive"))
      (node (ref "U2") (pin "V23") (pinfunction "VDD_V23") (pintype "passive"))
      (node (ref "U2") (pin "V25") (pinfunction "VDD_V25") (pintype "passive"))
      (node (ref "U2") (pin "V27") (pinfunction "VDD_V27") (pintype "passive"))
      (node (ref "U2") (pin "V29") (pinfunction "VDD_V29") (pintype "passive"))
      (node (ref "U2") (pin "V3") (pinfunction "VDD_V3") (pintype "passive"))
      (node (ref "U2") (pin "V5") (pinfunction "VDD_V5") (pintype "passive"))
      (node (ref "U2") (pin "V7") (pinfunction "VDD_V7") (pintype "passive"))
      (node (ref "U2") (pin "V9") (pinfunction "VDD_V9") (pintype "passive"))
      (node (ref "U2") (pin "W10") (pinfunction "VDD_W10") (pintype "passive"))
      (node (ref "U2") (pin "W12") (pinfunction "VDD_W12") (pintype "passive"))
      (node (ref "U2") (pin "W14") (pinfunction "VDD_W14") (pintype "passive"))
      (node (ref "U2") (pin "W16") (pinfunction "VDD_W16") (pintype "passive"))
      (node (ref "U2") (pin "W18") (pinfunction "VDD_W18") (pintype "passive"))
      (node (ref "U2") (pin "W2") (pinfunction "VDD_W2") (pintype "passive"))
      (node (ref "U2") (pin "W20") (pinfunction "VDD_W20") (pintype "passive"))
      (node (ref "U2") (pin "W22") (pinfunction "VDD_W22") (pintype "passive"))
      (node (ref "U2") (pin "W24") (pinfunction "VDD_W24") (pintype "passive"))
      (node (ref "U2") (pin "W26") (pinfunction "VDD_W26") (pintype "passive"))
      (node (ref "U2") (pin "W28") (pinfunction "VDD_W28") (pintype "passive"))
      (node (ref "U2") (pin "W30") (pinfunction "VDD_W30") (pintype "passive"))
      (node (ref "U2") (pin "W4") (pinfunction "VDD_W4") (pintype "passive"))
      (node (ref "U2") (pin "W6") (pinfunction "VDD_W6") (pintype "passive"))
      (node (ref "U2") (pin "W8") (pinfunction "VDD_W8") (pintype "passive"))
      (node (ref "U2") (pin "Y1") (pinfunction "VDD_Y1") (pintype "passive"))
      (node (ref "U2") (pin "Y11") (pinfunction "VDD_Y11") (pintype "passive"))
      (node (ref "U2") (pin "Y13") (pinfunction "VDD_Y13") (pintype "passive"))
      (node (ref "U2") (pin "Y15") (pinfunction "VDD_Y15") (pintype "passive"))
      (node (ref "U2") (pin "Y17") (pinfunction "VDD_Y17") (pintype "passive"))
      (node (ref "U2") (pin "Y19") (pinfunction "VDD_Y19") (pintype "passive"))
      (node (ref "U2") (pin "Y21") (pinfunction "VDD_Y21") (pintype "passive"))
      (node (ref "U2") (pin "Y23") (pinfunction "VDD_Y23") (pintype "passive"))
      (node (ref "U2") (pin "Y25") (pinfunction "VDD_Y25") (pintype "passive"))
      (node (ref "U2") (pin "Y27") (pinfunction "VDD_Y27") (pintype "passive"))
      (node (ref "U2") (pin "Y29") (pinfunction "VDD_Y29") (pintype "passive"))
      (node (ref "U2") (pin "Y3") (pinfunction "VDD_Y3") (pintype "passive"))
      (node (ref "U2") (pin "Y5") (pinfunction "VDD_Y5") (pintype "passive"))
      (node (ref "U2") (pin "Y7") (pinfunction "VDD_Y7") (pintype "passive"))
      (node (ref "U2") (pin "Y9") (pinfunction "VDD_Y9") (pintype "passive"))
      (node (ref "U3") (pin "A10") (pinfunction "VDD_A10") (pintype "passive"))
      (node (ref "U3") (pin "A12") (pinfunction "VDD_A12") (pintype "passive"))
      (node (ref "U3") (pin "A14") (pinfunction "VDD_A14") (pintype "passive"))
      (node (ref "U3") (pin "A16") (pinfunction "VDD_A16") (pintype "passive"))
      (node (ref "U3") (pin "A18") (pinfunction "VDD_A18") (pintype "passive"))
      (node (ref "U3") (pin "A2") (pinfunction "VDD_A2") (pintype "passive"))
      (node (ref "U3") (pin "A20") (pinfunction "VDD_A20") (pintype "passive"))
      (node (ref "U3") (pin "A22") (pinfunction "VDD_A22") (pintype "passive"))
      (node (ref "U3") (pin "A24") (pinfunction "VDD_A24") (pintype "passive"))
      (node (ref "U3") (pin "A26") (pinfunction "VDD_A26") (pintype "passive"))
      (node (ref "U3") (pin "A28") (pinfunction "VDD_A28") (pintype "passive"))
      (node (ref "U3") (pin "A30") (pinfunction "VDD_A30") (pintype "passive"))
      (node (ref "U3") (pin "A4") (pinfunction "VDD_A4") (pintype "passive"))
      (node (ref "U3") (pin "A6") (pinfunction "VDD_A6") (pintype "passive"))
      (node (ref "U3") (pin "A8") (pinfunction "VDD_A8") (pintype "passive"))
      (node (ref "U3") (pin "AA10") (pinfunction "VDD_AA10") (pintype "passive"))
      (node (ref "U3") (pin "AA12") (pinfunction "VDD_AA12") (pintype "passive"))
      (node (ref "U3") (pin "AA14") (pinfunction "VDD_AA14") (pintype "passive"))
      (node (ref "U3") (pin "AA16") (pinfunction "VDD_AA16") (pintype "passive"))
      (node (ref "U3") (pin "AA18") (pinfunction "VDD_AA18") (pintype "passive"))
      (node (ref "U3") (pin "AA2") (pinfunction "VDD_AA2") (pintype "passive"))
      (node (ref "U3") (pin "AA20") (pinfunction "VDD_AA20") (pintype "passive"))
      (node (ref "U3") (pin "AA22") (pinfunction "VDD_AA22") (pintype "passive"))
      (node (ref "U3") (pin "AA24") (pinfunction "VDD_AA24") (pintype "passive"))
      (node (ref "U3") (pin "AA26") (pinfunction "VDD_AA26") (pintype "passive"))
      (node (ref "U3") (pin "AA28") (pinfunction "VDD_AA28") (pintype "passive"))
      (node (ref "U3") (pin "AA30") (pinfunction "VDD_AA30") (pintype "passive"))
      (node (ref "U3") (pin "AA4") (pinfunction "VDD_AA4") (pintype "passive"))
      (node (ref "U3") (pin "AA6") (pinfunction "VDD_AA6") (pintype "passive"))
      (node (ref "U3") (pin "AA8") (pinfunction "VDD_AA8") (pintype "passive"))
      (node (ref "U3") (pin "AB1") (pinfunction "VDD_AB1") (pintype "passive"))
      (node (ref "U3") (pin "AB11") (pinfunction "VDD_AB11") (pintype "passive"))
      (node (ref "U3") (pin "AB13") (pinfunction "VDD_AB13") (pintype "passive"))
      (node (ref "U3") (pin "AB15") (pinfunction "VDD_AB15") (pintype "passive"))
      (node (ref "U3") (pin "AB17") (pinfunction "VDD_AB17") (pintype "passive"))
      (node (ref "U3") (pin "AB19") (pinfunction "VDD_AB19") (pintype "passive"))
      (node (ref "U3") (pin "AB21") (pinfunction "VDD_AB21") (pintype "passive"))
      (node (ref "U3") (pin "AB23") (pinfunction "VDD_AB23") (pintype "passive"))
      (node (ref "U3") (pin "AB25") (pinfunction "VDD_AB25") (pintype "passive"))
      (node (ref "U3") (pin "AB27") (pinfunction "VDD_AB27") (pintype "passive"))
      (node (ref "U3") (pin "AB29") (pinfunction "VDD_AB29") (pintype "passive"))
      (node (ref "U3") (pin "AB3") (pinfunction "VDD_AB3") (pintype "passive"))
      (node (ref "U3") (pin "AB5") (pinfunction "VDD_AB5") (pintype "passive"))
      (node (ref "U3") (pin "AB7") (pinfunction "VDD_AB7") (pintype "passive"))
      (node (ref "U3") (pin "AB9") (pinfunction "VDD_AB9") (pintype "passive"))
      (node (ref "U3") (pin "AC10") (pinfunction "VDD_AC10") (pintype "passive"))
      (node (ref "U3") (pin "AC12") (pinfunction "VDD_AC12") (pintype "passive"))
      (node (ref "U3") (pin "AC14") (pinfunction "VDD_AC14") (pintype "passive"))
      (node (ref "U3") (pin "AC16") (pinfunction "VDD_AC16") (pintype "passive"))
      (node (ref "U3") (pin "AC18") (pinfunction "VDD_AC18") (pintype "passive"))
      (node (ref "U3") (pin "AC2") (pinfunction "VDD_AC2") (pintype "passive"))
      (node (ref "U3") (pin "AC20") (pinfunction "VDD_AC20") (pintype "passive"))
      (node (ref "U3") (pin "AC22") (pinfunction "VDD_AC22") (pintype "passive"))
      (node (ref "U3") (pin "AC24") (pinfunction "VDD_AC24") (pintype "passive"))
      (node (ref "U3") (pin "AC26") (pinfunction "VDD_AC26") (pintype "passive"))
      (node (ref "U3") (pin "AC28") (pinfunction "VDD_AC28") (pintype "passive"))
      (node (ref "U3") (pin "AC30") (pinfunction "VDD_AC30") (pintype "passive"))
      (node (ref "U3") (pin "AC4") (pinfunction "VDD_AC4") (pintype "passive"))
      (node (ref "U3") (pin "AC6") (pinfunction "VDD_AC6") (pintype "passive"))
      (node (ref "U3") (pin "AC8") (pinfunction "VDD_AC8") (pintype "passive"))
      (node (ref "U3") (pin "AD1") (pinfunction "VDD_AD1") (pintype "passive"))
      (node (ref "U3") (pin "AD11") (pinfunction "VDD_AD11") (pintype "passive"))
      (node (ref "U3") (pin "AD13") (pinfunction "VDD_AD13") (pintype "passive"))
      (node (ref "U3") (pin "AD15") (pinfunction "VDD_AD15") (pintype "passive"))
      (node (ref "U3") (pin "AD17") (pinfunction "VDD_AD17") (pintype "passive"))
      (node (ref "U3") (pin "AD19") (pinfunction "VDD_AD19") (pintype "passive"))
      (node (ref "U3") (pin "AD21") (pinfunction "VDD_AD21") (pintype "passive"))
      (node (ref "U3") (pin "AD23") (pinfunction "VDD_AD23") (pintype "passive"))
      (node (ref "U3") (pin "AD25") (pinfunction "VDD_AD25") (pintype "passive"))
      (node (ref "U3") (pin "AD27") (pinfunction "VDD_AD27") (pintype "passive"))
      (node (ref "U3") (pin "AD29") (pinfunction "VDD_AD29") (pintype "passive"))
      (node (ref "U3") (pin "AD3") (pinfunction "VDD_AD3") (pintype "passive"))
      (node (ref "U3") (pin "AD5") (pinfunction "VDD_AD5") (pintype "passive"))
      (node (ref "U3") (pin "AD7") (pinfunction "VDD_AD7") (pintype "passive"))
      (node (ref "U3") (pin "AD9") (pinfunction "VDD_AD9") (pintype "passive"))
      (node (ref "U3") (pin "AE10") (pinfunction "VDD_AE10") (pintype "passive"))
      (node (ref "U3") (pin "AE12") (pinfunction "VDD_AE12") (pintype "passive"))
      (node (ref "U3") (pin "AE14") (pinfunction "VDD_AE14") (pintype "passive"))
      (node (ref "U3") (pin "AE16") (pinfunction "VDD_AE16") (pintype "passive"))
      (node (ref "U3") (pin "AE18") (pinfunction "VDD_AE18") (pintype "passive"))
      (node (ref "U3") (pin "AE2") (pinfunction "VDD_AE2") (pintype "passive"))
      (node (ref "U3") (pin "AE20") (pinfunction "VDD_AE20") (pintype "passive"))
      (node (ref "U3") (pin "AE22") (pinfunction "VDD_AE22") (pintype "passive"))
      (node (ref "U3") (pin "AE24") (pinfunction "VDD_AE24") (pintype "passive"))
      (node (ref "U3") (pin "AE26") (pinfunction "VDD_AE26") (pintype "passive"))
      (node (ref "U3") (pin "AE28") (pinfunction "VDD_AE28") (pintype "passive"))
      (node (ref "U3") (pin "AE30") (pinfunction "VDD_AE30") (pintype "passive"))
      (node (ref "U3") (pin "AE4") (pinfunction "VDD_AE4") (pintype "passive"))
      (node (ref "U3") (pin "AE6") (pinfunction "VDD_AE6") (pintype "passive"))
      (node (ref "U3") (pin "AE8") (pinfunction "VDD_AE8") (pintype "passive"))
      (node (ref "U3") (pin "AF1") (pinfunction "VDD_AF1") (pintype "passive"))
      (node (ref "U3") (pin "AF11") (pinfunction "VDD_AF11") (pintype "passive"))
      (node (ref "U3") (pin "AF13") (pinfunction "VDD_AF13") (pintype "passive"))
      (node (ref "U3") (pin "AF15") (pinfunction "VDD_AF15") (pintype "passive"))
      (node (ref "U3") (pin "AF17") (pinfunction "VDD_AF17") (pintype "passive"))
      (node (ref "U3") (pin "AF19") (pinfunction "VDD_AF19") (pintype "passive"))
      (node (ref "U3") (pin "AF21") (pinfunction "VDD_AF21") (pintype "passive"))
      (node (ref "U3") (pin "AF23") (pinfunction "VDD_AF23") (pintype "passive"))
      (node (ref "U3") (pin "AF25") (pinfunction "VDD_AF25") (pintype "passive"))
      (node (ref "U3") (pin "AF27") (pinfunction "VDD_AF27") (pintype "passive"))
      (node (ref "U3") (pin "AF29") (pinfunction "VDD_AF29") (pintype "passive"))
      (node (ref "U3") (pin "AF3") (pinfunction "VDD_AF3") (pintype "passive"))
      (node (ref "U3") (pin "AF5") (pinfunction "VDD_AF5") (pintype "passive"))
      (node (ref "U3") (pin "AF7") (pinfunction "VDD_AF7") (pintype "passive"))
      (node (ref "U3") (pin "AF9") (pinfunction "VDD_AF9") (pintype "passive"))
      (node (ref "U3") (pin "AG10") (pinfunction "VDD_AG10") (pintype "passive"))
      (node (ref "U3") (pin "AG12") (pinfunction "VDD_AG12") (pintype "passive"))
      (node (ref "U3") (pin "AG14") (pinfunction "VDD_AG14") (pintype "passive"))
      (node (ref "U3") (pin "AG16") (pinfunction "VDD_AG16") (pintype "passive"))
      (node (ref "U3") (pin "AG18") (pinfunction "VDD_AG18") (pintype "passive"))
      (node (ref "U3") (pin "AG2") (pinfunction "VDD_AG2") (pintype "passive"))
      (node (ref "U3") (pin "AG20") (pinfunction "VDD_AG20") (pintype "passive"))
      (node (ref "U3") (pin "AG22") (pinfunction "VDD_AG22") (pintype "passive"))
      (node (ref "U3") (pin "AG24") (pinfunction "VDD_AG24") (pintype "passive"))
      (node (ref "U3") (pin "AG26") (pinfunction "VDD_AG26") (pintype "passive"))
      (node (ref "U3") (pin "AG28") (pinfunction "VDD_AG28") (pintype "passive"))
      (node (ref "U3") (pin "AG30") (pinfunction "VDD_AG30") (pintype "passive"))
      (node (ref "U3") (pin "AG4") (pinfunction "VDD_AG4") (pintype "passive"))
      (node (ref "U3") (pin "AG6") (pinfunction "VDD_AG6") (pintype "passive"))
      (node (ref "U3") (pin "AG8") (pinfunction "VDD_AG8") (pintype "passive"))
      (node (ref "U3") (pin "AH1") (pinfunction "VDD_AH1") (pintype "passive"))
      (node (ref "U3") (pin "AH11") (pinfunction "VDD_AH11") (pintype "passive"))
      (node (ref "U3") (pin "AH13") (pinfunction "VDD_AH13") (pintype "passive"))
      (node (ref "U3") (pin "AH15") (pinfunction "VDD_AH15") (pintype "passive"))
      (node (ref "U3") (pin "AH17") (pinfunction "VDD_AH17") (pintype "passive"))
      (node (ref "U3") (pin "AH19") (pinfunction "VDD_AH19") (pintype "passive"))
      (node (ref "U3") (pin "AH21") (pinfunction "VDD_AH21") (pintype "passive"))
      (node (ref "U3") (pin "AH23") (pinfunction "VDD_AH23") (pintype "passive"))
      (node (ref "U3") (pin "AH25") (pinfunction "VDD_AH25") (pintype "passive"))
      (node (ref "U3") (pin "AH27") (pinfunction "VDD_AH27") (pintype "passive"))
      (node (ref "U3") (pin "AH29") (pinfunction "VDD_AH29") (pintype "passive"))
      (node (ref "U3") (pin "AH3") (pinfunction "VDD_AH3") (pintype "passive"))
      (node (ref "U3") (pin "AH5") (pinfunction "VDD_AH5") (pintype "passive"))
      (node (ref "U3") (pin "AH7") (pinfunction "VDD_AH7") (pintype "passive"))
      (node (ref "U3") (pin "AH9") (pinfunction "VDD_AH9") (pintype "passive"))
      (node (ref "U3") (pin "AJ10") (pinfunction "VDD_AJ10") (pintype "passive"))
      (node (ref "U3") (pin "AJ14") (pinfunction "VDD_AJ14") (pintype "passive"))
      (node (ref "U3") (pin "AJ18") (pinfunction "VDD_AJ18") (pintype "passive"))
      (node (ref "U3") (pin "AJ2") (pinfunction "VDD_AJ2") (pintype "passive"))
      (node (ref "U3") (pin "AJ28") (pinfunction "VDD_AJ28") (pintype "passive"))
      (node (ref "U3") (pin "AJ30") (pinfunction "VDD_AJ30") (pintype "passive"))
      (node (ref "U3") (pin "AK1") (pinfunction "VDD_AK1") (pintype "passive"))
      (node (ref "U3") (pin "AK26") (pinfunction "VDD_AK26") (pintype "passive"))
      (node (ref "U3") (pin "AK29") (pinfunction "VDD_AK29") (pintype "passive"))
      (node (ref "U3") (pin "B1") (pinfunction "VDD_B1") (pintype "passive"))
      (node (ref "U3") (pin "B11") (pinfunction "VDD_B11") (pintype "passive"))
      (node (ref "U3") (pin "B13") (pinfunction "VDD_B13") (pintype "passive"))
      (node (ref "U3") (pin "B15") (pinfunction "VDD_B15") (pintype "passive"))
      (node (ref "U3") (pin "B17") (pinfunction "VDD_B17") (pintype "passive"))
      (node (ref "U3") (pin "B19") (pinfunction "VDD_B19") (pintype "passive"))
      (node (ref "U3") (pin "B21") (pinfunction "VDD_B21") (pintype "passive"))
      (node (ref "U3") (pin "B23") (pinfunction "VDD_B23") (pintype "passive"))
      (node (ref "U3") (pin "B25") (pinfunction "VDD_B25") (pintype "passive"))
      (node (ref "U3") (pin "B27") (pinfunction "VDD_B27") (pintype "passive"))
      (node (ref "U3") (pin "B29") (pinfunction "VDD_B29") (pintype "passive"))
      (node (ref "U3") (pin "B3") (pinfunction "VDD_B3") (pintype "passive"))
      (node (ref "U3") (pin "B5") (pinfunction "VDD_B5") (pintype "passive"))
      (node (ref "U3") (pin "B7") (pinfunction "VDD_B7") (pintype "passive"))
      (node (ref "U3") (pin "B9") (pinfunction "VDD_B9") (pintype "passive"))
      (node (ref "U3") (pin "C10") (pinfunction "VDD_C10") (pintype "passive"))
      (node (ref "U3") (pin "C12") (pinfunction "VDD_C12") (pintype "passive"))
      (node (ref "U3") (pin "C14") (pinfunction "VDD_C14") (pintype "passive"))
      (node (ref "U3") (pin "C16") (pinfunction "VDD_C16") (pintype "passive"))
      (node (ref "U3") (pin "C18") (pinfunction "VDD_C18") (pintype "passive"))
      (node (ref "U3") (pin "C2") (pinfunction "VDD_C2") (pintype "passive"))
      (node (ref "U3") (pin "C20") (pinfunction "VDD_C20") (pintype "passive"))
      (node (ref "U3") (pin "C22") (pinfunction "VDD_C22") (pintype "passive"))
      (node (ref "U3") (pin "C24") (pinfunction "VDD_C24") (pintype "passive"))
      (node (ref "U3") (pin "C26") (pinfunction "VDD_C26") (pintype "passive"))
      (node (ref "U3") (pin "C28") (pinfunction "VDD_C28") (pintype "passive"))
      (node (ref "U3") (pin "C30") (pinfunction "VDD_C30") (pintype "passive"))
      (node (ref "U3") (pin "C4") (pinfunction "VDD_C4") (pintype "passive"))
      (node (ref "U3") (pin "C6") (pinfunction "VDD_C6") (pintype "passive"))
      (node (ref "U3") (pin "C8") (pinfunction "VDD_C8") (pintype "passive"))
      (node (ref "U3") (pin "D1") (pinfunction "VDD_D1") (pintype "passive"))
      (node (ref "U3") (pin "D11") (pinfunction "VDD_D11") (pintype "passive"))
      (node (ref "U3") (pin "D13") (pinfunction "VDD_D13") (pintype "passive"))
      (node (ref "U3") (pin "D15") (pinfunction "VDD_D15") (pintype "passive"))
      (node (ref "U3") (pin "D17") (pinfunction "VDD_D17") (pintype "passive"))
      (node (ref "U3") (pin "D19") (pinfunction "VDD_D19") (pintype "passive"))
      (node (ref "U3") (pin "D21") (pinfunction "VDD_D21") (pintype "passive"))
      (node (ref "U3") (pin "D23") (pinfunction "VDD_D23") (pintype "passive"))
      (node (ref "U3") (pin "D25") (pinfunction "VDD_D25") (pintype "passive"))
      (node (ref "U3") (pin "D27") (pinfunction "VDD_D27") (pintype "passive"))
      (node (ref "U3") (pin "D29") (pinfunction "VDD_D29") (pintype "passive"))
      (node (ref "U3") (pin "D3") (pinfunction "VDD_D3") (pintype "passive"))
      (node (ref "U3") (pin "D5") (pinfunction "VDD_D5") (pintype "passive"))
      (node (ref "U3") (pin "D7") (pinfunction "VDD_D7") (pintype "passive"))
      (node (ref "U3") (pin "D9") (pinfunction "VDD_D9") (pintype "passive"))
      (node (ref "U3") (pin "E10") (pinfunction "VDD_E10") (pintype "passive"))
      (node (ref "U3") (pin "E12") (pinfunction "VDD_E12") (pintype "passive"))
      (node (ref "U3") (pin "E14") (pinfunction "VDD_E14") (pintype "passive"))
      (node (ref "U3") (pin "E16") (pinfunction "VDD_E16") (pintype "passive"))
      (node (ref "U3") (pin "E18") (pinfunction "VDD_E18") (pintype "passive"))
      (node (ref "U3") (pin "E2") (pinfunction "VDD_E2") (pintype "passive"))
      (node (ref "U3") (pin "E20") (pinfunction "VDD_E20") (pintype "passive"))
      (node (ref "U3") (pin "E22") (pinfunction "VDD_E22") (pintype "passive"))
      (node (ref "U3") (pin "E24") (pinfunction "VDD_E24") (pintype "passive"))
      (node (ref "U3") (pin "E26") (pinfunction "VDD_E26") (pintype "passive"))
      (node (ref "U3") (pin "E28") (pinfunction "VDD_E28") (pintype "passive"))
      (node (ref "U3") (pin "E30") (pinfunction "VDD_E30") (pintype "passive"))
      (node (ref "U3") (pin "E4") (pinfunction "VDD_E4") (pintype "passive"))
      (node (ref "U3") (pin "E6") (pinfunction "VDD_E6") (pintype "passive"))
      (node (ref "U3") (pin "E8") (pinfunction "VDD_E8") (pintype "passive"))
      (node (ref "U3") (pin "F1") (pinfunction "VDD_F1") (pintype "passive"))
      (node (ref "U3") (pin "F11") (pinfunction "VDD_F11") (pintype "passive"))
      (node (ref "U3") (pin "F13") (pinfunction "VDD_F13") (pintype "passive"))
      (node (ref "U3") (pin "F15") (pinfunction "VDD_F15") (pintype "passive"))
      (node (ref "U3") (pin "F17") (pinfunction "VDD_F17") (pintype "passive"))
      (node (ref "U3") (pin "F19") (pinfunction "VDD_F19") (pintype "passive"))
      (node (ref "U3") (pin "F21") (pinfunction "VDD_F21") (pintype "passive"))
      (node (ref "U3") (pin "F23") (pinfunction "VDD_F23") (pintype "passive"))
      (node (ref "U3") (pin "F25") (pinfunction "VDD_F25") (pintype "passive"))
      (node (ref "U3") (pin "F27") (pinfunction "VDD_F27") (pintype "passive"))
      (node (ref "U3") (pin "F29") (pinfunction "VDD_F29") (pintype "passive"))
      (node (ref "U3") (pin "F3") (pinfunction "VDD_F3") (pintype "passive"))
      (node (ref "U3") (pin "F5") (pinfunction "VDD_F5") (pintype "passive"))
      (node (ref "U3") (pin "F7") (pinfunction "VDD_F7") (pintype "passive"))
      (node (ref "U3") (pin "F9") (pinfunction "VDD_F9") (pintype "passive"))
      (node (ref "U3") (pin "G10") (pinfunction "VDD_G10") (pintype "passive"))
      (node (ref "U3") (pin "G12") (pinfunction "VDD_G12") (pintype "passive"))
      (node (ref "U3") (pin "G14") (pinfunction "VDD_G14") (pintype "passive"))
      (node (ref "U3") (pin "G16") (pinfunction "VDD_G16") (pintype "passive"))
      (node (ref "U3") (pin "G18") (pinfunction "VDD_G18") (pintype "passive"))
      (node (ref "U3") (pin "G2") (pinfunction "VDD_G2") (pintype "passive"))
      (node (ref "U3") (pin "G20") (pinfunction "VDD_G20") (pintype "passive"))
      (node (ref "U3") (pin "G22") (pinfunction "VDD_G22") (pintype "passive"))
      (node (ref "U3") (pin "G24") (pinfunction "VDD_G24") (pintype "passive"))
      (node (ref "U3") (pin "G26") (pinfunction "VDD_G26") (pintype "passive"))
      (node (ref "U3") (pin "G28") (pinfunction "VDD_G28") (pintype "passive"))
      (node (ref "U3") (pin "G30") (pinfunction "VDD_G30") (pintype "passive"))
      (node (ref "U3") (pin "G4") (pinfunction "VDD_G4") (pintype "passive"))
      (node (ref "U3") (pin "G6") (pinfunction "VDD_G6") (pintype "passive"))
      (node (ref "U3") (pin "G8") (pinfunction "VDD_G8") (pintype "passive"))
      (node (ref "U3") (pin "H1") (pinfunction "VDD_H1") (pintype "passive"))
      (node (ref "U3") (pin "H11") (pinfunction "VDD_H11") (pintype "passive"))
      (node (ref "U3") (pin "H13") (pinfunction "VDD_H13") (pintype "passive"))
      (node (ref "U3") (pin "H15") (pinfunction "VDD_H15") (pintype "passive"))
      (node (ref "U3") (pin "H17") (pinfunction "VDD_H17") (pintype "passive"))
      (node (ref "U3") (pin "H19") (pinfunction "VDD_H19") (pintype "passive"))
      (node (ref "U3") (pin "H21") (pinfunction "VDD_H21") (pintype "passive"))
      (node (ref "U3") (pin "H23") (pinfunction "VDD_H23") (pintype "passive"))
      (node (ref "U3") (pin "H25") (pinfunction "VDD_H25") (pintype "passive"))
      (node (ref "U3") (pin "H27") (pinfunction "VDD_H27") (pintype "passive"))
      (node (ref "U3") (pin "H29") (pinfunction "VDD_H29") (pintype "passive"))
      (node (ref "U3") (pin "H3") (pinfunction "VDD_H3") (pintype "passive"))
      (node (ref "U3") (pin "H5") (pinfunction "VDD_H5") (pintype "passive"))
      (node (ref "U3") (pin "H7") (pinfunction "VDD_H7") (pintype "passive"))
      (node (ref "U3") (pin "H9") (pinfunction "VDD_H9") (pintype "passive"))
      (node (ref "U3") (pin "J10") (pinfunction "VDD_J10") (pintype "passive"))
      (node (ref "U3") (pin "J12") (pinfunction "VDD_J12") (pintype "passive"))
      (node (ref "U3") (pin "J14") (pinfunction "VDD_J14") (pintype "passive"))
      (node (ref "U3") (pin "J16") (pinfunction "VDD_J16") (pintype "passive"))
      (node (ref "U3") (pin "J18") (pinfunction "VDD_J18") (pintype "passive"))
      (node (ref "U3") (pin "J2") (pinfunction "VDD_J2") (pintype "passive"))
      (node (ref "U3") (pin "J20") (pinfunction "VDD_J20") (pintype "passive"))
      (node (ref "U3") (pin "J22") (pinfunction "VDD_J22") (pintype "passive"))
      (node (ref "U3") (pin "J24") (pinfunction "VDD_J24") (pintype "passive"))
      (node (ref "U3") (pin "J26") (pinfunction "VDD_J26") (pintype "passive"))
      (node (ref "U3") (pin "J28") (pinfunction "VDD_J28") (pintype "passive"))
      (node (ref "U3") (pin "J30") (pinfunction "VDD_J30") (pintype "passive"))
      (node (ref "U3") (pin "J4") (pinfunction "VDD_J4") (pintype "passive"))
      (node (ref "U3") (pin "J6") (pinfunction "VDD_J6") (pintype "passive"))
      (node (ref "U3") (pin "J8") (pinfunction "VDD_J8") (pintype "passive"))
      (node (ref "U3") (pin "K1") (pinfunction "VDD_K1") (pintype "passive"))
      (node (ref "U3") (pin "K11") (pinfunction "VDD_K11") (pintype "passive"))
      (node (ref "U3") (pin "K13") (pinfunction "VDD_K13") (pintype "passive"))
      (node (ref "U3") (pin "K15") (pinfunction "VDD_K15") (pintype "passive"))
      (node (ref "U3") (pin "K17") (pinfunction "VDD_K17") (pintype "passive"))
      (node (ref "U3") (pin "K19") (pinfunction "VDD_K19") (pintype "passive"))
      (node (ref "U3") (pin "K21") (pinfunction "VDD_K21") (pintype "passive"))
      (node (ref "U3") (pin "K23") (pinfunction "VDD_K23") (pintype "passive"))
      (node (ref "U3") (pin "K25") (pinfunction "VDD_K25") (pintype "passive"))
      (node (ref "U3") (pin "K27") (pinfunction "VDD_K27") (pintype "passive"))
      (node (ref "U3") (pin "K29") (pinfunction "VDD_K29") (pintype "passive"))
      (node (ref "U3") (pin "K3") (pinfunction "VDD_K3") (pintype "passive"))
      (node (ref "U3") (pin "K5") (pinfunction "VDD_K5") (pintype "passive"))
      (node (ref "U3") (pin "K7") (pinfunction "VDD_K7") (pintype "passive"))
      (node (ref "U3") (pin "K9") (pinfunction "VDD_K9") (pintype "passive"))
      (node (ref "U3") (pin "L10") (pinfunction "VDD_L10") (pintype "passive"))
      (node (ref "U3") (pin "L12") (pinfunction "VDD_L12") (pintype "passive"))
      (node (ref "U3") (pin "L14") (pinfunction "VDD_L14") (pintype "passive"))
      (node (ref "U3") (pin "L16") (pinfunction "VDD_L16") (pintype "passive"))
      (node (ref "U3") (pin "L18") (pinfunction "VDD_L18") (pintype "passive"))
      (node (ref "U3") (pin "L2") (pinfunction "VDD_L2") (pintype "passive"))
      (node (ref "U3") (pin "L20") (pinfunction "VDD_L20") (pintype "passive"))
      (node (ref "U3") (pin "L22") (pinfunction "VDD_L22") (pintype "passive"))
      (node (ref "U3") (pin "L24") (pinfunction "VDD_L24") (pintype "passive"))
      (node (ref "U3") (pin "L26") (pinfunction "VDD_L26") (pintype "passive"))
      (node (ref "U3") (pin "L28") (pinfunction "VDD_L28") (pintype "passive"))
      (node (ref "U3") (pin "L30") (pinfunction "VDD_L30") (pintype "passive"))
      (node (ref "U3") (pin "L4") (pinfunction "VDD_L4") (pintype "passive"))
      (node (ref "U3") (pin "L6") (pinfunction "VDD_L6") (pintype "passive"))
      (node (ref "U3") (pin "L8") (pinfunction "VDD_L8") (pintype "passive"))
      (node (ref "U3") (pin "M1") (pinfunction "VDD_M1") (pintype "passive"))
      (node (ref "U3") (pin "M11") (pinfunction "VDD_M11") (pintype "passive"))
      (node (ref "U3") (pin "M13") (pinfunction "VDD_M13") (pintype "passive"))
      (node (ref "U3") (pin "M15") (pinfunction "VDD_M15") (pintype "passive"))
      (node (ref "U3") (pin "M17") (pinfunction "VDD_M17") (pintype "passive"))
      (node (ref "U3") (pin "M19") (pinfunction "VDD_M19") (pintype "passive"))
      (node (ref "U3") (pin "M21") (pinfunction "VDD_M21") (pintype "passive"))
      (node (ref "U3") (pin "M23") (pinfunction "VDD_M23") (pintype "passive"))
      (node (ref "U3") (pin "M25") (pinfunction "VDD_M25") (pintype "passive"))
      (node (ref "U3") (pin "M27") (pinfunction "VDD_M27") (pintype "passive"))
      (node (ref "U3") (pin "M29") (pinfunction "VDD_M29") (pintype "passive"))
      (node (ref "U3") (pin "M3") (pinfunction "VDD_M3") (pintype "passive"))
      (node (ref "U3") (pin "M5") (pinfunction "VDD_M5") (pintype "passive"))
      (node (ref "U3") (pin "M7") (pinfunction "VDD_M7") (pintype "passive"))
      (node (ref "U3") (pin "M9") (pinfunction "VDD_M9") (pintype "passive"))
      (node (ref "U3") (pin "N10") (pinfunction "VDD_N10") (pintype "passive"))
      (node (ref "U3") (pin "N12") (pinfunction "VDD_N12") (pintype "passive"))
      (node (ref "U3") (pin "N14") (pinfunction "VDD_N14") (pintype "passive"))
      (node (ref "U3") (pin "N16") (pinfunction "VDD_N16") (pintype "passive"))
      (node (ref "U3") (pin "N18") (pinfunction "VDD_N18") (pintype "passive"))
      (node (ref "U3") (pin "N2") (pinfunction "VDD_N2") (pintype "passive"))
      (node (ref "U3") (pin "N20") (pinfunction "VDD_N20") (pintype "passive"))
      (node (ref "U3") (pin "N22") (pinfunction "VDD_N22") (pintype "passive"))
      (node (ref "U3") (pin "N24") (pinfunction "VDD_N24") (pintype "passive"))
      (node (ref "U3") (pin "N26") (pinfunction "VDD_N26") (pintype "passive"))
      (node (ref "U3") (pin "N28") (pinfunction "VDD_N28") (pintype "passive"))
      (node (ref "U3") (pin "N30") (pinfunction "VDD_N30") (pintype "passive"))
      (node (ref "U3") (pin "N4") (pinfunction "VDD_N4") (pintype "passive"))
      (node (ref "U3") (pin "N6") (pinfunction "VDD_N6") (pintype "passive"))
      (node (ref "U3") (pin "N8") (pinfunction "VDD_N8") (pintype "passive"))
      (node (ref "U3") (pin "P1") (pinfunction "VDD_P1") (pintype "passive"))
      (node (ref "U3") (pin "P11") (pinfunction "VDD_P11") (pintype "passive"))
      (node (ref "U3") (pin "P13") (pinfunction "VDD_P13") (pintype "passive"))
      (node (ref "U3") (pin "P15") (pinfunction "VDD_P15") (pintype "passive"))
      (node (ref "U3") (pin "P17") (pinfunction "VDD_P17") (pintype "passive"))
      (node (ref "U3") (pin "P19") (pinfunction "VDD_P19") (pintype "passive"))
      (node (ref "U3") (pin "P21") (pinfunction "VDD_P21") (pintype "passive"))
      (node (ref "U3") (pin "P23") (pinfunction "VDD_P23") (pintype "passive"))
      (node (ref "U3") (pin "P25") (pinfunction "VDD_P25") (pintype "passive"))
      (node (ref "U3") (pin "P27") (pinfunction "VDD_P27") (pintype "passive"))
      (node (ref "U3") (pin "P29") (pinfunction "VDD_P29") (pintype "passive"))
      (node (ref "U3") (pin "P3") (pinfunction "VDD_P3") (pintype "passive"))
      (node (ref "U3") (pin "P5") (pinfunction "VDD_P5") (pintype "passive"))
      (node (ref "U3") (pin "P7") (pinfunction "VDD_P7") (pintype "passive"))
      (node (ref "U3") (pin "P9") (pinfunction "VDD_P9") (pintype "passive"))
      (node (ref "U3") (pin "R10") (pinfunction "VDD_R10") (pintype "passive"))
      (node (ref "U3") (pin "R12") (pinfunction "VDD_R12") (pintype "passive"))
      (node (ref "U3") (pin "R14") (pinfunction "VDD_R14") (pintype "passive"))
      (node (ref "U3") (pin "R16") (pinfunction "VDD_R16") (pintype "passive"))
      (node (ref "U3") (pin "R18") (pinfunction "VDD_R18") (pintype "passive"))
      (node (ref "U3") (pin "R2") (pinfunction "VDD_R2") (pintype "passive"))
      (node (ref "U3") (pin "R20") (pinfunction "VDD_R20") (pintype "passive"))
      (node (ref "U3") (pin "R22") (pinfunction "VDD_R22") (pintype "passive"))
      (node (ref "U3") (pin "R24") (pinfunction "VDD_R24") (pintype "passive"))
      (node (ref "U3") (pin "R26") (pinfunction "VDD_R26") (pintype "passive"))
      (node (ref "U3") (pin "R28") (pinfunction "VDD_R28") (pintype "passive"))
      (node (ref "U3") (pin "R30") (pinfunction "VDD_R30") (pintype "passive"))
      (node (ref "U3") (pin "R4") (pinfunction "VDD_R4") (pintype "passive"))
      (node (ref "U3") (pin "R6") (pinfunction "VDD_R6") (pintype "passive"))
      (node (ref "U3") (pin "R8") (pinfunction "VDD_R8") (pintype "passive"))
      (node (ref "U3") (pin "T1") (pinfunction "VDD_T1") (pintype "passive"))
      (node (ref "U3") (pin "T11") (pinfunction "VDD_T11") (pintype "passive"))
      (node (ref "U3") (pin "T13") (pinfunction "VDD_T13") (pintype "passive"))
      (node (ref "U3") (pin "T15") (pinfunction "VDD_T15") (pintype "passive"))
      (node (ref "U3") (pin "T17") (pinfunction "VDD_T17") (pintype "passive"))
      (node (ref "U3") (pin "T19") (pinfunction "VDD_T19") (pintype "passive"))
      (node (ref "U3") (pin "T21") (pinfunction "VDD_T21") (pintype "passive"))
      (node (ref "U3") (pin "T23") (pinfunction "VDD_T23") (pintype "passive"))
      (node (ref "U3") (pin "T25") (pinfunction "VDD_T25") (pintype "passive"))
      (node (ref "U3") (pin "T27") (pinfunction "VDD_T27") (pintype "passive"))
      (node (ref "U3") (pin "T29") (pinfunction "VDD_T29") (pintype "passive"))
      (node (ref "U3") (pin "T3") (pinfunction "VDD_T3") (pintype "passive"))
      (node (ref "U3") (pin "T5") (pinfunction "VDD_T5") (pintype "passive"))
      (node (ref "U3") (pin "T7") (pinfunction "VDD_T7") (pintype "passive"))
      (node (ref "U3") (pin "T9") (pinfunction "VDD_T9") (pintype "passive"))
      (node (ref "U3") (pin "U10") (pinfunction "VDD_U10") (pintype "passive"))
      (node (ref "U3") (pin "U12") (pinfunction "VDD_U12") (pintype "passive"))
      (node (ref "U3") (pin "U14") (pinfunction "VDD_U14") (pintype "passive"))
      (node (ref "U3") (pin "U16") (pinfunction "VDD_U16") (pintype "passive"))
      (node (ref "U3") (pin "U18") (pinfunction "VDD_U18") (pintype "passive"))
      (node (ref "U3") (pin "U2") (pinfunction "VDD_U2") (pintype "passive"))
      (node (ref "U3") (pin "U20") (pinfunction "VDD_U20") (pintype "passive"))
      (node (ref "U3") (pin "U22") (pinfunction "VDD_U22") (pintype "passive"))
      (node (ref "U3") (pin "U24") (pinfunction "VDD_U24") (pintype "passive"))
      (node (ref "U3") (pin "U26") (pinfunction "VDD_U26") (pintype "passive"))
      (node (ref "U3") (pin "U28") (pinfunction "VDD_U28") (pintype "passive"))
      (node (ref "U3") (pin "U30") (pinfunction "VDD_U30") (pintype "passive"))
      (node (ref "U3") (pin "U4") (pinfunction "VDD_U4") (pintype "passive"))
      (node (ref "U3") (pin "U6") (pinfunction "VDD_U6") (pintype "passive"))
      (node (ref "U3") (pin "U8") (pinfunction "VDD_U8") (pintype "passive"))
      (node (ref "U3") (pin "V1") (pinfunction "VDD_V1") (pintype "passive"))
      (node (ref "U3") (pin "V11") (pinfunction "VDD_V11") (pintype "passive"))
      (node (ref "U3") (pin "V13") (pinfunction "VDD_V13") (pintype "passive"))
      (node (ref "U3") (pin "V15") (pinfunction "VDD_V15") (pintype "passive"))
      (node (ref "U3") (pin "V17") (pinfunction "VDD_V17") (pintype "passive"))
      (node (ref "U3") (pin "V19") (pinfunction "VDD_V19") (pintype "passive"))
      (node (ref "U3") (pin "V21") (pinfunction "VDD_V21") (pintype "passive"))
      (node (ref "U3") (pin "V23") (pinfunction "VDD_V23") (pintype "passive"))
      (node (ref "U3") (pin "V25") (pinfunction "VDD_V25") (pintype "passive"))
      (node (ref "U3") (pin "V27") (pinfunction "VDD_V27") (pintype "passive"))
      (node (ref "U3") (pin "V29") (pinfunction "VDD_V29") (pintype "passive"))
      (node (ref "U3") (pin "V3") (pinfunction "VDD_V3") (pintype "passive"))
      (node (ref "U3") (pin "V5") (pinfunction "VDD_V5") (pintype "passive"))
      (node (ref "U3") (pin "V7") (pinfunction "VDD_V7") (pintype "passive"))
      (node (ref "U3") (pin "V9") (pinfunction "VDD_V9") (pintype "passive"))
      (node (ref "U3") (pin "W10") (pinfunction "VDD_W10") (pintype "passive"))
      (node (ref "U3") (pin "W12") (pinfunction "VDD_W12") (pintype "passive"))
      (node (ref "U3") (pin "W14") (pinfunction "VDD_W14") (pintype "passive"))
      (node (ref "U3") (pin "W16") (pinfunction "VDD_W16") (pintype "passive"))
      (node (ref "U3") (pin "W18") (pinfunction "VDD_W18") (pintype "passive"))
      (node (ref "U3") (pin "W2") (pinfunction "VDD_W2") (pintype "passive"))
      (node (ref "U3") (pin "W20") (pinfunction "VDD_W20") (pintype "passive"))
      (node (ref "U3") (pin "W22") (pinfunction "VDD_W22") (pintype "passive"))
      (node (ref "U3") (pin "W24") (pinfunction "VDD_W24") (pintype "passive"))
      (node (ref "U3") (pin "W26") (pinfunction "VDD_W26") (pintype "passive"))
      (node (ref "U3") (pin "W28") (pinfunction "VDD_W28") (pintype "passive"))
      (node (ref "U3") (pin "W30") (pinfunction "VDD_W30") (pintype "passive"))
      (node (ref "U3") (pin "W4") (pinfunction "VDD_W4") (pintype "passive"))
      (node (ref "U3") (pin "W6") (pinfunction "VDD_W6") (pintype "passive"))
      (node (ref "U3") (pin "W8") (pinfunction "VDD_W8") (pintype "passive"))
      (node (ref "U3") (pin "Y1") (pinfunction "VDD_Y1") (pintype "passive"))
      (node (ref "U3") (pin "Y11") (pinfunction "VDD_Y11") (pintype "passive"))
      (node (ref "U3") (pin "Y13") (pinfunction "VDD_Y13") (pintype "passive"))
      (node (ref "U3") (pin "Y15") (pinfunction "VDD_Y15") (pintype "passive"))
      (node (ref "U3") (pin "Y17") (pinfunction "VDD_Y17") (pintype "passive"))
      (node (ref "U3") (pin "Y19") (pinfunction "VDD_Y19") (pintype "passive"))
      (node (ref "U3") (pin "Y21") (pinfunction "VDD_Y21") (pintype "passive"))
      (node (ref "U3") (pin "Y23") (pinfunction "VDD_Y23") (pintype "passive"))
      (node (ref "U3") (pin "Y25") (pinfunction "VDD_Y25") (pintype "passive"))
      (node (ref "U3") (pin "Y27") (pinfunction "VDD_Y27") (pintype "passive"))
      (node (ref "U3") (pin "Y29") (pinfunction "VDD_Y29") (pintype "passive"))
      (node (ref "U3") (pin "Y3") (pinfunction "VDD_Y3") (pintype "passive"))
      (node (ref "U3") (pin "Y5") (pinfunction "VDD_Y5") (pintype "passive"))
      (node (ref "U3") (pin "Y7") (pinfunction "VDD_Y7") (pintype "passive"))
      (node (ref "U3") (pin "Y9") (pinfunction "VDD_Y9") (pintype "passive"))
      (node (ref "U4") (pin "A10") (pinfunction "VDD_A10") (pintype "passive"))
      (node (ref "U4") (pin "A12") (pinfunction "VDD_A12") (pintype "passive"))
      (node (ref "U4") (pin "A14") (pinfunction "VDD_A14") (pintype "passive"))
      (node (ref "U4") (pin "A16") (pinfunction "VDD_A16") (pintype "passive"))
      (node (ref "U4") (pin "A18") (pinfunction "VDD_A18") (pintype "passive"))
      (node (ref "U4") (pin "A2") (pinfunction "VDD_A2") (pintype "passive"))
      (node (ref "U4") (pin "A20") (pinfunction "VDD_A20") (pintype "passive"))
      (node (ref "U4") (pin "A22") (pinfunction "VDD_A22") (pintype "passive"))
      (node (ref "U4") (pin "A24") (pinfunction "VDD_A24") (pintype "passive"))
      (node (ref "U4") (pin "A26") (pinfunction "VDD_A26") (pintype "passive"))
      (node (ref "U4") (pin "A28") (pinfunction "VDD_A28") (pintype "passive"))
      (node (ref "U4") (pin "A30") (pinfunction "VDD_A30") (pintype "passive"))
      (node (ref "U4") (pin "A4") (pinfunction "VDD_A4") (pintype "passive"))
      (node (ref "U4") (pin "A6") (pinfunction "VDD_A6") (pintype "passive"))
      (node (ref "U4") (pin "A8") (pinfunction "VDD_A8") (pintype "passive"))
      (node (ref "U4") (pin "AA10") (pinfunction "VDD_AA10") (pintype "passive"))
      (node (ref "U4") (pin "AA12") (pinfunction "VDD_AA12") (pintype "passive"))
      (node (ref "U4") (pin "AA14") (pinfunction "VDD_AA14") (pintype "passive"))
      (node (ref "U4") (pin "AA16") (pinfunction "VDD_AA16") (pintype "passive"))
      (node (ref "U4") (pin "AA18") (pinfunction "VDD_AA18") (pintype "passive"))
      (node (ref "U4") (pin "AA2") (pinfunction "VDD_AA2") (pintype "passive"))
      (node (ref "U4") (pin "AA20") (pinfunction "VDD_AA20") (pintype "passive"))
      (node (ref "U4") (pin "AA22") (pinfunction "VDD_AA22") (pintype "passive"))
      (node (ref "U4") (pin "AA24") (pinfunction "VDD_AA24") (pintype "passive"))
      (node (ref "U4") (pin "AA26") (pinfunction "VDD_AA26") (pintype "passive"))
      (node (ref "U4") (pin "AA28") (pinfunction "VDD_AA28") (pintype "passive"))
      (node (ref "U4") (pin "AA30") (pinfunction "VDD_AA30") (pintype "passive"))
      (node (ref "U4") (pin "AA4") (pinfunction "VDD_AA4") (pintype "passive"))
      (node (ref "U4") (pin "AA6") (pinfunction "VDD_AA6") (pintype "passive"))
      (node (ref "U4") (pin "AA8") (pinfunction "VDD_AA8") (pintype "passive"))
      (node (ref "U4") (pin "AB1") (pinfunction "VDD_AB1") (pintype "passive"))
      (node (ref "U4") (pin "AB11") (pinfunction "VDD_AB11") (pintype "passive"))
      (node (ref "U4") (pin "AB13") (pinfunction "VDD_AB13") (pintype "passive"))
      (node (ref "U4") (pin "AB15") (pinfunction "VDD_AB15") (pintype "passive"))
      (node (ref "U4") (pin "AB17") (pinfunction "VDD_AB17") (pintype "passive"))
      (node (ref "U4") (pin "AB19") (pinfunction "VDD_AB19") (pintype "passive"))
      (node (ref "U4") (pin "AB21") (pinfunction "VDD_AB21") (pintype "passive"))
      (node (ref "U4") (pin "AB23") (pinfunction "VDD_AB23") (pintype "passive"))
      (node (ref "U4") (pin "AB25") (pinfunction "VDD_AB25") (pintype "passive"))
      (node (ref "U4") (pin "AB27") (pinfunction "VDD_AB27") (pintype "passive"))
      (node (ref "U4") (pin "AB29") (pinfunction "VDD_AB29") (pintype "passive"))
      (node (ref "U4") (pin "AB3") (pinfunction "VDD_AB3") (pintype "passive"))
      (node (ref "U4") (pin "AB5") (pinfunction "VDD_AB5") (pintype "passive"))
      (node (ref "U4") (pin "AB7") (pinfunction "VDD_AB7") (pintype "passive"))
      (node (ref "U4") (pin "AB9") (pinfunction "VDD_AB9") (pintype "passive"))
      (node (ref "U4") (pin "AC10") (pinfunction "VDD_AC10") (pintype "passive"))
      (node (ref "U4") (pin "AC12") (pinfunction "VDD_AC12") (pintype "passive"))
      (node (ref "U4") (pin "AC14") (pinfunction "VDD_AC14") (pintype "passive"))
      (node (ref "U4") (pin "AC16") (pinfunction "VDD_AC16") (pintype "passive"))
      (node (ref "U4") (pin "AC18") (pinfunction "VDD_AC18") (pintype "passive"))
      (node (ref "U4") (pin "AC2") (pinfunction "VDD_AC2") (pintype "passive"))
      (node (ref "U4") (pin "AC20") (pinfunction "VDD_AC20") (pintype "passive"))
      (node (ref "U4") (pin "AC22") (pinfunction "VDD_AC22") (pintype "passive"))
      (node (ref "U4") (pin "AC24") (pinfunction "VDD_AC24") (pintype "passive"))
      (node (ref "U4") (pin "AC26") (pinfunction "VDD_AC26") (pintype "passive"))
      (node (ref "U4") (pin "AC28") (pinfunction "VDD_AC28") (pintype "passive"))
      (node (ref "U4") (pin "AC30") (pinfunction "VDD_AC30") (pintype "passive"))
      (node (ref "U4") (pin "AC4") (pinfunction "VDD_AC4") (pintype "passive"))
      (node (ref "U4") (pin "AC6") (pinfunction "VDD_AC6") (pintype "passive"))
      (node (ref "U4") (pin "AC8") (pinfunction "VDD_AC8") (pintype "passive"))
      (node (ref "U4") (pin "AD1") (pinfunction "VDD_AD1") (pintype "passive"))
      (node (ref "U4") (pin "AD11") (pinfunction "VDD_AD11") (pintype "passive"))
      (node (ref "U4") (pin "AD13") (pinfunction "VDD_AD13") (pintype "passive"))
      (node (ref "U4") (pin "AD15") (pinfunction "VDD_AD15") (pintype "passive"))
      (node (ref "U4") (pin "AD17") (pinfunction "VDD_AD17") (pintype "passive"))
      (node (ref "U4") (pin "AD19") (pinfunction "VDD_AD19") (pintype "passive"))
      (node (ref "U4") (pin "AD21") (pinfunction "VDD_AD21") (pintype "passive"))
      (node (ref "U4") (pin "AD23") (pinfunction "VDD_AD23") (pintype "passive"))
      (node (ref "U4") (pin "AD25") (pinfunction "VDD_AD25") (pintype "passive"))
      (node (ref "U4") (pin "AD27") (pinfunction "VDD_AD27") (pintype "passive"))
      (node (ref "U4") (pin "AD29") (pinfunction "VDD_AD29") (pintype "passive"))
      (node (ref "U4") (pin "AD3") (pinfunction "VDD_AD3") (pintype "passive"))
      (node (ref "U4") (pin "AD5") (pinfunction "VDD_AD5") (pintype "passive"))
      (node (ref "U4") (pin "AD7") (pinfunction "VDD_AD7") (pintype "passive"))
      (node (ref "U4") (pin "AD9") (pinfunction "VDD_AD9") (pintype "passive"))
      (node (ref "U4") (pin "AE10") (pinfunction "VDD_AE10") (pintype "passive"))
      (node (ref "U4") (pin "AE12") (pinfunction "VDD_AE12") (pintype "passive"))
      (node (ref "U4") (pin "AE14") (pinfunction "VDD_AE14") (pintype "passive"))
      (node (ref "U4") (pin "AE16") (pinfunction "VDD_AE16") (pintype "passive"))
      (node (ref "U4") (pin "AE18") (pinfunction "VDD_AE18") (pintype "passive"))
      (node (ref "U4") (pin "AE2") (pinfunction "VDD_AE2") (pintype "passive"))
      (node (ref "U4") (pin "AE20") (pinfunction "VDD_AE20") (pintype "passive"))
      (node (ref "U4") (pin "AE22") (pinfunction "VDD_AE22") (pintype "passive"))
      (node (ref "U4") (pin "AE24") (pinfunction "VDD_AE24") (pintype "passive"))
      (node (ref "U4") (pin "AE26") (pinfunction "VDD_AE26") (pintype "passive"))
      (node (ref "U4") (pin "AE28") (pinfunction "VDD_AE28") (pintype "passive"))
      (node (ref "U4") (pin "AE30") (pinfunction "VDD_AE30") (pintype "passive"))
      (node (ref "U4") (pin "AE4") (pinfunction "VDD_AE4") (pintype "passive"))
      (node (ref "U4") (pin "AE6") (pinfunction "VDD_AE6") (pintype "passive"))
      (node (ref "U4") (pin "AE8") (pinfunction "VDD_AE8") (pintype "passive"))
      (node (ref "U4") (pin "AF1") (pinfunction "VDD_AF1") (pintype "passive"))
      (node (ref "U4") (pin "AF11") (pinfunction "VDD_AF11") (pintype "passive"))
      (node (ref "U4") (pin "AF13") (pinfunction "VDD_AF13") (pintype "passive"))
      (node (ref "U4") (pin "AF15") (pinfunction "VDD_AF15") (pintype "passive"))
      (node (ref "U4") (pin "AF17") (pinfunction "VDD_AF17") (pintype "passive"))
      (node (ref "U4") (pin "AF19") (pinfunction "VDD_AF19") (pintype "passive"))
      (node (ref "U4") (pin "AF21") (pinfunction "VDD_AF21") (pintype "passive"))
      (node (ref "U4") (pin "AF23") (pinfunction "VDD_AF23") (pintype "passive"))
      (node (ref "U4") (pin "AF25") (pinfunction "VDD_AF25") (pintype "passive"))
      (node (ref "U4") (pin "AF27") (pinfunction "VDD_AF27") (pintype "passive"))
      (node (ref "U4") (pin "AF29") (pinfunction "VDD_AF29") (pintype "passive"))
      (node (ref "U4") (pin "AF3") (pinfunction "VDD_AF3") (pintype "passive"))
      (node (ref "U4") (pin "AF5") (pinfunction "VDD_AF5") (pintype "passive"))
      (node (ref "U4") (pin "AF7") (pinfunction "VDD_AF7") (pintype "passive"))
      (node (ref "U4") (pin "AF9") (pinfunction "VDD_AF9") (pintype "passive"))
      (node (ref "U4") (pin "AG10") (pinfunction "VDD_AG10") (pintype "passive"))
      (node (ref "U4") (pin "AG12") (pinfunction "VDD_AG12") (pintype "passive"))
      (node (ref "U4") (pin "AG14") (pinfunction "VDD_AG14") (pintype "passive"))
      (node (ref "U4") (pin "AG16") (pinfunction "VDD_AG16") (pintype "passive"))
      (node (ref "U4") (pin "AG18") (pinfunction "VDD_AG18") (pintype "passive"))
      (node (ref "U4") (pin "AG2") (pinfunction "VDD_AG2") (pintype "passive"))
      (node (ref "U4") (pin "AG20") (pinfunction "VDD_AG20") (pintype "passive"))
      (node (ref "U4") (pin "AG22") (pinfunction "VDD_AG22") (pintype "passive"))
      (node (ref "U4") (pin "AG24") (pinfunction "VDD_AG24") (pintype "passive"))
      (node (ref "U4") (pin "AG26") (pinfunction "VDD_AG26") (pintype "passive"))
      (node (ref "U4") (pin "AG28") (pinfunction "VDD_AG28") (pintype "passive"))
      (node (ref "U4") (pin "AG30") (pinfunction "VDD_AG30") (pintype "passive"))
      (node (ref "U4") (pin "AG4") (pinfunction "VDD_AG4") (pintype "passive"))
      (node (ref "U4") (pin "AG6") (pinfunction "VDD_AG6") (pintype "passive"))
      (node (ref "U4") (pin "AG8") (pinfunction "VDD_AG8") (pintype "passive"))
      (node (ref "U4") (pin "AH1") (pinfunction "VDD_AH1") (pintype "passive"))
      (node (ref "U4") (pin "AH11") (pinfunction "VDD_AH11") (pintype "passive"))
      (node (ref "U4") (pin "AH13") (pinfunction "VDD_AH13") (pintype "passive"))
      (node (ref "U4") (pin "AH15") (pinfunction "VDD_AH15") (pintype "passive"))
      (node (ref "U4") (pin "AH17") (pinfunction "VDD_AH17") (pintype "passive"))
      (node (ref "U4") (pin "AH19") (pinfunction "VDD_AH19") (pintype "passive"))
      (node (ref "U4") (pin "AH21") (pinfunction "VDD_AH21") (pintype "passive"))
      (node (ref "U4") (pin "AH23") (pinfunction "VDD_AH23") (pintype "passive"))
      (node (ref "U4") (pin "AH25") (pinfunction "VDD_AH25") (pintype "passive"))
      (node (ref "U4") (pin "AH27") (pinfunction "VDD_AH27") (pintype "passive"))
      (node (ref "U4") (pin "AH29") (pinfunction "VDD_AH29") (pintype "passive"))
      (node (ref "U4") (pin "AH3") (pinfunction "VDD_AH3") (pintype "passive"))
      (node (ref "U4") (pin "AH5") (pinfunction "VDD_AH5") (pintype "passive"))
      (node (ref "U4") (pin "AH7") (pinfunction "VDD_AH7") (pintype "passive"))
      (node (ref "U4") (pin "AH9") (pinfunction "VDD_AH9") (pintype "passive"))
      (node (ref "U4") (pin "AJ10") (pinfunction "VDD_AJ10") (pintype "passive"))
      (node (ref "U4") (pin "AJ14") (pinfunction "VDD_AJ14") (pintype "passive"))
      (node (ref "U4") (pin "AJ18") (pinfunction "VDD_AJ18") (pintype "passive"))
      (node (ref "U4") (pin "AJ2") (pinfunction "VDD_AJ2") (pintype "passive"))
      (node (ref "U4") (pin "AJ28") (pinfunction "VDD_AJ28") (pintype "passive"))
      (node (ref "U4") (pin "AJ30") (pinfunction "VDD_AJ30") (pintype "passive"))
      (node (ref "U4") (pin "AK1") (pinfunction "VDD_AK1") (pintype "passive"))
      (node (ref "U4") (pin "AK26") (pinfunction "VDD_AK26") (pintype "passive"))
      (node (ref "U4") (pin "AK29") (pinfunction "VDD_AK29") (pintype "passive"))
      (node (ref "U4") (pin "B1") (pinfunction "VDD_B1") (pintype "passive"))
      (node (ref "U4") (pin "B11") (pinfunction "VDD_B11") (pintype "passive"))
      (node (ref "U4") (pin "B13") (pinfunction "VDD_B13") (pintype "passive"))
      (node (ref "U4") (pin "B15") (pinfunction "VDD_B15") (pintype "passive"))
      (node (ref "U4") (pin "B17") (pinfunction "VDD_B17") (pintype "passive"))
      (node (ref "U4") (pin "B19") (pinfunction "VDD_B19") (pintype "passive"))
      (node (ref "U4") (pin "B21") (pinfunction "VDD_B21") (pintype "passive"))
      (node (ref "U4") (pin "B23") (pinfunction "VDD_B23") (pintype "passive"))
      (node (ref "U4") (pin "B25") (pinfunction "VDD_B25") (pintype "passive"))
      (node (ref "U4") (pin "B27") (pinfunction "VDD_B27") (pintype "passive"))
      (node (ref "U4") (pin "B29") (pinfunction "VDD_B29") (pintype "passive"))
      (node (ref "U4") (pin "B3") (pinfunction "VDD_B3") (pintype "passive"))
      (node (ref "U4") (pin "B5") (pinfunction "VDD_B5") (pintype "passive"))
      (node (ref "U4") (pin "B7") (pinfunction "VDD_B7") (pintype "passive"))
      (node (ref "U4") (pin "B9") (pinfunction "VDD_B9") (pintype "passive"))
      (node (ref "U4") (pin "C10") (pinfunction "VDD_C10") (pintype "passive"))
      (node (ref "U4") (pin "C12") (pinfunction "VDD_C12") (pintype "passive"))
      (node (ref "U4") (pin "C14") (pinfunction "VDD_C14") (pintype "passive"))
      (node (ref "U4") (pin "C16") (pinfunction "VDD_C16") (pintype "passive"))
      (node (ref "U4") (pin "C18") (pinfunction "VDD_C18") (pintype "passive"))
      (node (ref "U4") (pin "C2") (pinfunction "VDD_C2") (pintype "passive"))
      (node (ref "U4") (pin "C20") (pinfunction "VDD_C20") (pintype "passive"))
      (node (ref "U4") (pin "C22") (pinfunction "VDD_C22") (pintype "passive"))
      (node (ref "U4") (pin "C24") (pinfunction "VDD_C24") (pintype "passive"))
      (node (ref "U4") (pin "C26") (pinfunction "VDD_C26") (pintype "passive"))
      (node (ref "U4") (pin "C28") (pinfunction "VDD_C28") (pintype "passive"))
      (node (ref "U4") (pin "C30") (pinfunction "VDD_C30") (pintype "passive"))
      (node (ref "U4") (pin "C4") (pinfunction "VDD_C4") (pintype "passive"))
      (node (ref "U4") (pin "C6") (pinfunction "VDD_C6") (pintype "passive"))
      (node (ref "U4") (pin "C8") (pinfunction "VDD_C8") (pintype "passive"))
      (node (ref "U4") (pin "D1") (pinfunction "VDD_D1") (pintype "passive"))
      (node (ref "U4") (pin "D11") (pinfunction "VDD_D11") (pintype "passive"))
      (node (ref "U4") (pin "D13") (pinfunction "VDD_D13") (pintype "passive"))
      (node (ref "U4") (pin "D15") (pinfunction "VDD_D15") (pintype "passive"))
      (node (ref "U4") (pin "D17") (pinfunction "VDD_D17") (pintype "passive"))
      (node (ref "U4") (pin "D19") (pinfunction "VDD_D19") (pintype "passive"))
      (node (ref "U4") (pin "D21") (pinfunction "VDD_D21") (pintype "passive"))
      (node (ref "U4") (pin "D23") (pinfunction "VDD_D23") (pintype "passive"))
      (node (ref "U4") (pin "D25") (pinfunction "VDD_D25") (pintype "passive"))
      (node (ref "U4") (pin "D27") (pinfunction "VDD_D27") (pintype "passive"))
      (node (ref "U4") (pin "D29") (pinfunction "VDD_D29") (pintype "passive"))
      (node (ref "U4") (pin "D3") (pinfunction "VDD_D3") (pintype "passive"))
      (node (ref "U4") (pin "D5") (pinfunction "VDD_D5") (pintype "passive"))
      (node (ref "U4") (pin "D7") (pinfunction "VDD_D7") (pintype "passive"))
      (node (ref "U4") (pin "D9") (pinfunction "VDD_D9") (pintype "passive"))
      (node (ref "U4") (pin "E10") (pinfunction "VDD_E10") (pintype "passive"))
      (node (ref "U4") (pin "E12") (pinfunction "VDD_E12") (pintype "passive"))
      (node (ref "U4") (pin "E14") (pinfunction "VDD_E14") (pintype "passive"))
      (node (ref "U4") (pin "E16") (pinfunction "VDD_E16") (pintype "passive"))
      (node (ref "U4") (pin "E18") (pinfunction "VDD_E18") (pintype "passive"))
      (node (ref "U4") (pin "E2") (pinfunction "VDD_E2") (pintype "passive"))
      (node (ref "U4") (pin "E20") (pinfunction "VDD_E20") (pintype "passive"))
      (node (ref "U4") (pin "E22") (pinfunction "VDD_E22") (pintype "passive"))
      (node (ref "U4") (pin "E24") (pinfunction "VDD_E24") (pintype "passive"))
      (node (ref "U4") (pin "E26") (pinfunction "VDD_E26") (pintype "passive"))
      (node (ref "U4") (pin "E28") (pinfunction "VDD_E28") (pintype "passive"))
      (node (ref "U4") (pin "E30") (pinfunction "VDD_E30") (pintype "passive"))
      (node (ref "U4") (pin "E4") (pinfunction "VDD_E4") (pintype "passive"))
      (node (ref "U4") (pin "E6") (pinfunction "VDD_E6") (pintype "passive"))
      (node (ref "U4") (pin "E8") (pinfunction "VDD_E8") (pintype "passive"))
      (node (ref "U4") (pin "F1") (pinfunction "VDD_F1") (pintype "passive"))
      (node (ref "U4") (pin "F11") (pinfunction "VDD_F11") (pintype "passive"))
      (node (ref "U4") (pin "F13") (pinfunction "VDD_F13") (pintype "passive"))
      (node (ref "U4") (pin "F15") (pinfunction "VDD_F15") (pintype "passive"))
      (node (ref "U4") (pin "F17") (pinfunction "VDD_F17") (pintype "passive"))
      (node (ref "U4") (pin "F19") (pinfunction "VDD_F19") (pintype "passive"))
      (node (ref "U4") (pin "F21") (pinfunction "VDD_F21") (pintype "passive"))
      (node (ref "U4") (pin "F23") (pinfunction "VDD_F23") (pintype "passive"))
      (node (ref "U4") (pin "F25") (pinfunction "VDD_F25") (pintype "passive"))
      (node (ref "U4") (pin "F27") (pinfunction "VDD_F27") (pintype "passive"))
      (node (ref "U4") (pin "F29") (pinfunction "VDD_F29") (pintype "passive"))
      (node (ref "U4") (pin "F3") (pinfunction "VDD_F3") (pintype "passive"))
      (node (ref "U4") (pin "F5") (pinfunction "VDD_F5") (pintype "passive"))
      (node (ref "U4") (pin "F7") (pinfunction "VDD_F7") (pintype "passive"))
      (node (ref "U4") (pin "F9") (pinfunction "VDD_F9") (pintype "passive"))
      (node (ref "U4") (pin "G10") (pinfunction "VDD_G10") (pintype "passive"))
      (node (ref "U4") (pin "G12") (pinfunction "VDD_G12") (pintype "passive"))
      (node (ref "U4") (pin "G14") (pinfunction "VDD_G14") (pintype "passive"))
      (node (ref "U4") (pin "G16") (pinfunction "VDD_G16") (pintype "passive"))
      (node (ref "U4") (pin "G18") (pinfunction "VDD_G18") (pintype "passive"))
      (node (ref "U4") (pin "G2") (pinfunction "VDD_G2") (pintype "passive"))
      (node (ref "U4") (pin "G20") (pinfunction "VDD_G20") (pintype "passive"))
      (node (ref "U4") (pin "G22") (pinfunction "VDD_G22") (pintype "passive"))
      (node (ref "U4") (pin "G24") (pinfunction "VDD_G24") (pintype "passive"))
      (node (ref "U4") (pin "G26") (pinfunction "VDD_G26") (pintype "passive"))
      (node (ref "U4") (pin "G28") (pinfunction "VDD_G28") (pintype "passive"))
      (node (ref "U4") (pin "G30") (pinfunction "VDD_G30") (pintype "passive"))
      (node (ref "U4") (pin "G4") (pinfunction "VDD_G4") (pintype "passive"))
      (node (ref "U4") (pin "G6") (pinfunction "VDD_G6") (pintype "passive"))
      (node (ref "U4") (pin "G8") (pinfunction "VDD_G8") (pintype "passive"))
      (node (ref "U4") (pin "H1") (pinfunction "VDD_H1") (pintype "passive"))
      (node (ref "U4") (pin "H11") (pinfunction "VDD_H11") (pintype "passive"))
      (node (ref "U4") (pin "H13") (pinfunction "VDD_H13") (pintype "passive"))
      (node (ref "U4") (pin "H15") (pinfunction "VDD_H15") (pintype "passive"))
      (node (ref "U4") (pin "H17") (pinfunction "VDD_H17") (pintype "passive"))
      (node (ref "U4") (pin "H19") (pinfunction "VDD_H19") (pintype "passive"))
      (node (ref "U4") (pin "H21") (pinfunction "VDD_H21") (pintype "passive"))
      (node (ref "U4") (pin "H23") (pinfunction "VDD_H23") (pintype "passive"))
      (node (ref "U4") (pin "H25") (pinfunction "VDD_H25") (pintype "passive"))
      (node (ref "U4") (pin "H27") (pinfunction "VDD_H27") (pintype "passive"))
      (node (ref "U4") (pin "H29") (pinfunction "VDD_H29") (pintype "passive"))
      (node (ref "U4") (pin "H3") (pinfunction "VDD_H3") (pintype "passive"))
      (node (ref "U4") (pin "H5") (pinfunction "VDD_H5") (pintype "passive"))
      (node (ref "U4") (pin "H7") (pinfunction "VDD_H7") (pintype "passive"))
      (node (ref "U4") (pin "H9") (pinfunction "VDD_H9") (pintype "passive"))
      (node (ref "U4") (pin "J10") (pinfunction "VDD_J10") (pintype "passive"))
      (node (ref "U4") (pin "J12") (pinfunction "VDD_J12") (pintype "passive"))
      (node (ref "U4") (pin "J14") (pinfunction "VDD_J14") (pintype "passive"))
      (node (ref "U4") (pin "J16") (pinfunction "VDD_J16") (pintype "passive"))
      (node (ref "U4") (pin "J18") (pinfunction "VDD_J18") (pintype "passive"))
      (node (ref "U4") (pin "J2") (pinfunction "VDD_J2") (pintype "passive"))
      (node (ref "U4") (pin "J20") (pinfunction "VDD_J20") (pintype "passive"))
      (node (ref "U4") (pin "J22") (pinfunction "VDD_J22") (pintype "passive"))
      (node (ref "U4") (pin "J24") (pinfunction "VDD_J24") (pintype "passive"))
      (node (ref "U4") (pin "J26") (pinfunction "VDD_J26") (pintype "passive"))
      (node (ref "U4") (pin "J28") (pinfunction "VDD_J28") (pintype "passive"))
      (node (ref "U4") (pin "J30") (pinfunction "VDD_J30") (pintype "passive"))
      (node (ref "U4") (pin "J4") (pinfunction "VDD_J4") (pintype "passive"))
      (node (ref "U4") (pin "J6") (pinfunction "VDD_J6") (pintype "passive"))
      (node (ref "U4") (pin "J8") (pinfunction "VDD_J8") (pintype "passive"))
      (node (ref "U4") (pin "K1") (pinfunction "VDD_K1") (pintype "passive"))
      (node (ref "U4") (pin "K11") (pinfunction "VDD_K11") (pintype "passive"))
      (node (ref "U4") (pin "K13") (pinfunction "VDD_K13") (pintype "passive"))
      (node (ref "U4") (pin "K15") (pinfunction "VDD_K15") (pintype "passive"))
      (node (ref "U4") (pin "K17") (pinfunction "VDD_K17") (pintype "passive"))
      (node (ref "U4") (pin "K19") (pinfunction "VDD_K19") (pintype "passive"))
      (node (ref "U4") (pin "K21") (pinfunction "VDD_K21") (pintype "passive"))
      (node (ref "U4") (pin "K23") (pinfunction "VDD_K23") (pintype "passive"))
      (node (ref "U4") (pin "K25") (pinfunction "VDD_K25") (pintype "passive"))
      (node (ref "U4") (pin "K27") (pinfunction "VDD_K27") (pintype "passive"))
      (node (ref "U4") (pin "K29") (pinfunction "VDD_K29") (pintype "passive"))
      (node (ref "U4") (pin "K3") (pinfunction "VDD_K3") (pintype "passive"))
      (node (ref "U4") (pin "K5") (pinfunction "VDD_K5") (pintype "passive"))
      (node (ref "U4") (pin "K7") (pinfunction "VDD_K7") (pintype "passive"))
      (node (ref "U4") (pin "K9") (pinfunction "VDD_K9") (pintype "passive"))
      (node (ref "U4") (pin "L10") (pinfunction "VDD_L10") (pintype "passive"))
      (node (ref "U4") (pin "L12") (pinfunction "VDD_L12") (pintype "passive"))
      (node (ref "U4") (pin "L14") (pinfunction "VDD_L14") (pintype "passive"))
      (node (ref "U4") (pin "L16") (pinfunction "VDD_L16") (pintype "passive"))
      (node (ref "U4") (pin "L18") (pinfunction "VDD_L18") (pintype "passive"))
      (node (ref "U4") (pin "L2") (pinfunction "VDD_L2") (pintype "passive"))
      (node (ref "U4") (pin "L20") (pinfunction "VDD_L20") (pintype "passive"))
      (node (ref "U4") (pin "L22") (pinfunction "VDD_L22") (pintype "passive"))
      (node (ref "U4") (pin "L24") (pinfunction "VDD_L24") (pintype "passive"))
      (node (ref "U4") (pin "L26") (pinfunction "VDD_L26") (pintype "passive"))
      (node (ref "U4") (pin "L28") (pinfunction "VDD_L28") (pintype "passive"))
      (node (ref "U4") (pin "L30") (pinfunction "VDD_L30") (pintype "passive"))
      (node (ref "U4") (pin "L4") (pinfunction "VDD_L4") (pintype "passive"))
      (node (ref "U4") (pin "L6") (pinfunction "VDD_L6") (pintype "passive"))
      (node (ref "U4") (pin "L8") (pinfunction "VDD_L8") (pintype "passive"))
      (node (ref "U4") (pin "M1") (pinfunction "VDD_M1") (pintype "passive"))
      (node (ref "U4") (pin "M11") (pinfunction "VDD_M11") (pintype "passive"))
      (node (ref "U4") (pin "M13") (pinfunction "VDD_M13") (pintype "passive"))
      (node (ref "U4") (pin "M15") (pinfunction "VDD_M15") (pintype "passive"))
      (node (ref "U4") (pin "M17") (pinfunction "VDD_M17") (pintype "passive"))
      (node (ref "U4") (pin "M19") (pinfunction "VDD_M19") (pintype "passive"))
      (node (ref "U4") (pin "M21") (pinfunction "VDD_M21") (pintype "passive"))
      (node (ref "U4") (pin "M23") (pinfunction "VDD_M23") (pintype "passive"))
      (node (ref "U4") (pin "M25") (pinfunction "VDD_M25") (pintype "passive"))
      (node (ref "U4") (pin "M27") (pinfunction "VDD_M27") (pintype "passive"))
      (node (ref "U4") (pin "M29") (pinfunction "VDD_M29") (pintype "passive"))
      (node (ref "U4") (pin "M3") (pinfunction "VDD_M3") (pintype "passive"))
      (node (ref "U4") (pin "M5") (pinfunction "VDD_M5") (pintype "passive"))
      (node (ref "U4") (pin "M7") (pinfunction "VDD_M7") (pintype "passive"))
      (node (ref "U4") (pin "M9") (pinfunction "VDD_M9") (pintype "passive"))
      (node (ref "U4") (pin "N10") (pinfunction "VDD_N10") (pintype "passive"))
      (node (ref "U4") (pin "N12") (pinfunction "VDD_N12") (pintype "passive"))
      (node (ref "U4") (pin "N14") (pinfunction "VDD_N14") (pintype "passive"))
      (node (ref "U4") (pin "N16") (pinfunction "VDD_N16") (pintype "passive"))
      (node (ref "U4") (pin "N18") (pinfunction "VDD_N18") (pintype "passive"))
      (node (ref "U4") (pin "N2") (pinfunction "VDD_N2") (pintype "passive"))
      (node (ref "U4") (pin "N20") (pinfunction "VDD_N20") (pintype "passive"))
      (node (ref "U4") (pin "N22") (pinfunction "VDD_N22") (pintype "passive"))
      (node (ref "U4") (pin "N24") (pinfunction "VDD_N24") (pintype "passive"))
      (node (ref "U4") (pin "N26") (pinfunction "VDD_N26") (pintype "passive"))
      (node (ref "U4") (pin "N28") (pinfunction "VDD_N28") (pintype "passive"))
      (node (ref "U4") (pin "N30") (pinfunction "VDD_N30") (pintype "passive"))
      (node (ref "U4") (pin "N4") (pinfunction "VDD_N4") (pintype "passive"))
      (node (ref "U4") (pin "N6") (pinfunction "VDD_N6") (pintype "passive"))
      (node (ref "U4") (pin "N8") (pinfunction "VDD_N8") (pintype "passive"))
      (node (ref "U4") (pin "P1") (pinfunction "VDD_P1") (pintype "passive"))
      (node (ref "U4") (pin "P11") (pinfunction "VDD_P11") (pintype "passive"))
      (node (ref "U4") (pin "P13") (pinfunction "VDD_P13") (pintype "passive"))
      (node (ref "U4") (pin "P15") (pinfunction "VDD_P15") (pintype "passive"))
      (node (ref "U4") (pin "P17") (pinfunction "VDD_P17") (pintype "passive"))
      (node (ref "U4") (pin "P19") (pinfunction "VDD_P19") (pintype "passive"))
      (node (ref "U4") (pin "P21") (pinfunction "VDD_P21") (pintype "passive"))
      (node (ref "U4") (pin "P23") (pinfunction "VDD_P23") (pintype "passive"))
      (node (ref "U4") (pin "P25") (pinfunction "VDD_P25") (pintype "passive"))
      (node (ref "U4") (pin "P27") (pinfunction "VDD_P27") (pintype "passive"))
      (node (ref "U4") (pin "P29") (pinfunction "VDD_P29") (pintype "passive"))
      (node (ref "U4") (pin "P3") (pinfunction "VDD_P3") (pintype "passive"))
      (node (ref "U4") (pin "P5") (pinfunction "VDD_P5") (pintype "passive"))
      (node (ref "U4") (pin "P7") (pinfunction "VDD_P7") (pintype "passive"))
      (node (ref "U4") (pin "P9") (pinfunction "VDD_P9") (pintype "passive"))
      (node (ref "U4") (pin "R10") (pinfunction "VDD_R10") (pintype "passive"))
      (node (ref "U4") (pin "R12") (pinfunction "VDD_R12") (pintype "passive"))
      (node (ref "U4") (pin "R14") (pinfunction "VDD_R14") (pintype "passive"))
      (node (ref "U4") (pin "R16") (pinfunction "VDD_R16") (pintype "passive"))
      (node (ref "U4") (pin "R18") (pinfunction "VDD_R18") (pintype "passive"))
      (node (ref "U4") (pin "R2") (pinfunction "VDD_R2") (pintype "passive"))
      (node (ref "U4") (pin "R20") (pinfunction "VDD_R20") (pintype "passive"))
      (node (ref "U4") (pin "R22") (pinfunction "VDD_R22") (pintype "passive"))
      (node (ref "U4") (pin "R24") (pinfunction "VDD_R24") (pintype "passive"))
      (node (ref "U4") (pin "R26") (pinfunction "VDD_R26") (pintype "passive"))
      (node (ref "U4") (pin "R28") (pinfunction "VDD_R28") (pintype "passive"))
      (node (ref "U4") (pin "R30") (pinfunction "VDD_R30") (pintype "passive"))
      (node (ref "U4") (pin "R4") (pinfunction "VDD_R4") (pintype "passive"))
      (node (ref "U4") (pin "R6") (pinfunction "VDD_R6") (pintype "passive"))
      (node (ref "U4") (pin "R8") (pinfunction "VDD_R8") (pintype "passive"))
      (node (ref "U4") (pin "T1") (pinfunction "VDD_T1") (pintype "passive"))
      (node (ref "U4") (pin "T11") (pinfunction "VDD_T11") (pintype "passive"))
      (node (ref "U4") (pin "T13") (pinfunction "VDD_T13") (pintype "passive"))
      (node (ref "U4") (pin "T15") (pinfunction "VDD_T15") (pintype "passive"))
      (node (ref "U4") (pin "T17") (pinfunction "VDD_T17") (pintype "passive"))
      (node (ref "U4") (pin "T19") (pinfunction "VDD_T19") (pintype "passive"))
      (node (ref "U4") (pin "T21") (pinfunction "VDD_T21") (pintype "passive"))
      (node (ref "U4") (pin "T23") (pinfunction "VDD_T23") (pintype "passive"))
      (node (ref "U4") (pin "T25") (pinfunction "VDD_T25") (pintype "passive"))
      (node (ref "U4") (pin "T27") (pinfunction "VDD_T27") (pintype "passive"))
      (node (ref "U4") (pin "T29") (pinfunction "VDD_T29") (pintype "passive"))
      (node (ref "U4") (pin "T3") (pinfunction "VDD_T3") (pintype "passive"))
      (node (ref "U4") (pin "T5") (pinfunction "VDD_T5") (pintype "passive"))
      (node (ref "U4") (pin "T7") (pinfunction "VDD_T7") (pintype "passive"))
      (node (ref "U4") (pin "T9") (pinfunction "VDD_T9") (pintype "passive"))
      (node (ref "U4") (pin "U10") (pinfunction "VDD_U10") (pintype "passive"))
      (node (ref "U4") (pin "U12") (pinfunction "VDD_U12") (pintype "passive"))
      (node (ref "U4") (pin "U14") (pinfunction "VDD_U14") (pintype "passive"))
      (node (ref "U4") (pin "U16") (pinfunction "VDD_U16") (pintype "passive"))
      (node (ref "U4") (pin "U18") (pinfunction "VDD_U18") (pintype "passive"))
      (node (ref "U4") (pin "U2") (pinfunction "VDD_U2") (pintype "passive"))
      (node (ref "U4") (pin "U20") (pinfunction "VDD_U20") (pintype "passive"))
      (node (ref "U4") (pin "U22") (pinfunction "VDD_U22") (pintype "passive"))
      (node (ref "U4") (pin "U24") (pinfunction "VDD_U24") (pintype "passive"))
      (node (ref "U4") (pin "U26") (pinfunction "VDD_U26") (pintype "passive"))
      (node (ref "U4") (pin "U28") (pinfunction "VDD_U28") (pintype "passive"))
      (node (ref "U4") (pin "U30") (pinfunction "VDD_U30") (pintype "passive"))
      (node (ref "U4") (pin "U4") (pinfunction "VDD_U4") (pintype "passive"))
      (node (ref "U4") (pin "U6") (pinfunction "VDD_U6") (pintype "passive"))
      (node (ref "U4") (pin "U8") (pinfunction "VDD_U8") (pintype "passive"))
      (node (ref "U4") (pin "V1") (pinfunction "VDD_V1") (pintype "passive"))
      (node (ref "U4") (pin "V11") (pinfunction "VDD_V11") (pintype "passive"))
      (node (ref "U4") (pin "V13") (pinfunction "VDD_V13") (pintype "passive"))
      (node (ref "U4") (pin "V15") (pinfunction "VDD_V15") (pintype "passive"))
      (node (ref "U4") (pin "V17") (pinfunction "VDD_V17") (pintype "passive"))
      (node (ref "U4") (pin "V19") (pinfunction "VDD_V19") (pintype "passive"))
      (node (ref "U4") (pin "V21") (pinfunction "VDD_V21") (pintype "passive"))
      (node (ref "U4") (pin "V23") (pinfunction "VDD_V23") (pintype "passive"))
      (node (ref "U4") (pin "V25") (pinfunction "VDD_V25") (pintype "passive"))
      (node (ref "U4") (pin "V27") (pinfunction "VDD_V27") (pintype "passive"))
      (node (ref "U4") (pin "V29") (pinfunction "VDD_V29") (pintype "passive"))
      (node (ref "U4") (pin "V3") (pinfunction "VDD_V3") (pintype "passive"))
      (node (ref "U4") (pin "V5") (pinfunction "VDD_V5") (pintype "passive"))
      (node (ref "U4") (pin "V7") (pinfunction "VDD_V7") (pintype "passive"))
      (node (ref "U4") (pin "V9") (pinfunction "VDD_V9") (pintype "passive"))
      (node (ref "U4") (pin "W10") (pinfunction "VDD_W10") (pintype "passive"))
      (node (ref "U4") (pin "W12") (pinfunction "VDD_W12") (pintype "passive"))
      (node (ref "U4") (pin "W14") (pinfunction "VDD_W14") (pintype "passive"))
      (node (ref "U4") (pin "W16") (pinfunction "VDD_W16") (pintype "passive"))
      (node (ref "U4") (pin "W18") (pinfunction "VDD_W18") (pintype "passive"))
      (node (ref "U4") (pin "W2") (pinfunction "VDD_W2") (pintype "passive"))
      (node (ref "U4") (pin "W20") (pinfunction "VDD_W20") (pintype "passive"))
      (node (ref "U4") (pin "W22") (pinfunction "VDD_W22") (pintype "passive"))
      (node (ref "U4") (pin "W24") (pinfunction "VDD_W24") (pintype "passive"))
      (node (ref "U4") (pin "W26") (pinfunction "VDD_W26") (pintype "passive"))
      (node (ref "U4") (pin "W28") (pinfunction "VDD_W28") (pintype "passive"))
      (node (ref "U4") (pin "W30") (pinfunction "VDD_W30") (pintype "passive"))
      (node (ref "U4") (pin "W4") (pinfunction "VDD_W4") (pintype "passive"))
      (node (ref "U4") (pin "W6") (pinfunction "VDD_W6") (pintype "passive"))
      (node (ref "U4") (pin "W8") (pinfunction "VDD_W8") (pintype "passive"))
      (node (ref "U4") (pin "Y1") (pinfunction "VDD_Y1") (pintype "passive"))
      (node (ref "U4") (pin "Y11") (pinfunction "VDD_Y11") (pintype "passive"))
      (node (ref "U4") (pin "Y13") (pinfunction "VDD_Y13") (pintype "passive"))
      (node (ref "U4") (pin "Y15") (pinfunction "VDD_Y15") (pintype "passive"))
      (node (ref "U4") (pin "Y17") (pinfunction "VDD_Y17") (pintype "passive"))
      (node (ref "U4") (pin "Y19") (pinfunction "VDD_Y19") (pintype "passive"))
      (node (ref "U4") (pin "Y21") (pinfunction "VDD_Y21") (pintype "passive"))
      (node (ref "U4") (pin "Y23") (pinfunction "VDD_Y23") (pintype "passive"))
      (node (ref "U4") (pin "Y25") (pinfunction "VDD_Y25") (pintype "passive"))
      (node (ref "U4") (pin "Y27") (pinfunction "VDD_Y27") (pintype "passive"))
      (node (ref "U4") (pin "Y29") (pinfunction "VDD_Y29") (pintype "passive"))
      (node (ref "U4") (pin "Y3") (pinfunction "VDD_Y3") (pintype "passive"))
      (node (ref "U4") (pin "Y5") (pinfunction "VDD_Y5") (pintype "passive"))
      (node (ref "U4") (pin "Y7") (pinfunction "VDD_Y7") (pintype "passive"))
      (node (ref "U4") (pin "Y9") (pinfunction "VDD_Y9") (pintype "passive"))
    )
    (net (code "2") (name "GND") (class "Default")
      (node (ref "U13") (pin "A1") (pinfunction "GND_A1") (pintype "passive"))
      (node (ref "U13") (pin "A11") (pinfunction "GND_A11") (pintype "passive"))
      (node (ref "U13") (pin "A13") (pinfunction "GND_A13") (pintype "passive"))
      (node (ref "U13") (pin "A15") (pinfunction "GND_A15") (pintype "passive"))
      (node (ref "U13") (pin "A17") (pinfunction "GND_A17") (pintype "passive"))
      (node (ref "U13") (pin "A19") (pinfunction "GND_A19") (pintype "passive"))
      (node (ref "U13") (pin "A21") (pinfunction "GND_A21") (pintype "passive"))
      (node (ref "U13") (pin "A23") (pinfunction "GND_A23") (pintype "passive"))
      (node (ref "U13") (pin "A25") (pinfunction "GND_A25") (pintype "passive"))
      (node (ref "U13") (pin "A27") (pinfunction "GND_A27") (pintype "passive"))
      (node (ref "U13") (pin "A29") (pinfunction "GND_A29") (pintype "passive"))
      (node (ref "U13") (pin "A3") (pinfunction "GND_A3") (pintype "passive"))
      (node (ref "U13") (pin "A5") (pinfunction "GND_A5") (pintype "passive"))
      (node (ref "U13") (pin "A7") (pinfunction "GND_A7") (pintype "passive"))
      (node (ref "U13") (pin "A9") (pinfunction "GND_A9") (pintype "passive"))
      (node (ref "U13") (pin "AA1") (pinfunction "GND_AA1") (pintype "passive"))
      (node (ref "U13") (pin "AA11") (pinfunction "GND_AA11") (pintype "passive"))
      (node (ref "U13") (pin "AA13") (pinfunction "GND_AA13") (pintype "passive"))
      (node (ref "U13") (pin "AA15") (pinfunction "GND_AA15") (pintype "passive"))
      (node (ref "U13") (pin "AA17") (pinfunction "GND_AA17") (pintype "passive"))
      (node (ref "U13") (pin "AA19") (pinfunction "GND_AA19") (pintype "passive"))
      (node (ref "U13") (pin "AA21") (pinfunction "GND_AA21") (pintype "passive"))
      (node (ref "U13") (pin "AA23") (pinfunction "GND_AA23") (pintype "passive"))
      (node (ref "U13") (pin "AA25") (pinfunction "GND_AA25") (pintype "passive"))
      (node (ref "U13") (pin "AA27") (pinfunction "GND_AA27") (pintype "passive"))
      (node (ref "U13") (pin "AA29") (pinfunction "GND_AA29") (pintype "passive"))
      (node (ref "U13") (pin "AA3") (pinfunction "GND_AA3") (pintype "passive"))
      (node (ref "U13") (pin "AA5") (pinfunction "GND_AA5") (pintype "passive"))
      (node (ref "U13") (pin "AA7") (pinfunction "GND_AA7") (pintype "passive"))
      (node (ref "U13") (pin "AA9") (pinfunction "GND_AA9") (pintype "passive"))
      (node (ref "U13") (pin "AB10") (pinfunction "GND_AB10") (pintype "passive"))
      (node (ref "U13") (pin "AB12") (pinfunction "GND_AB12") (pintype "passive"))
      (node (ref "U13") (pin "AB14") (pinfunction "GND_AB14") (pintype "passive"))
      (node (ref "U13") (pin "AB16") (pinfunction "GND_AB16") (pintype "passive"))
      (node (ref "U13") (pin "AB18") (pinfunction "GND_AB18") (pintype "passive"))
      (node (ref "U13") (pin "AB2") (pinfunction "GND_AB2") (pintype "passive"))
      (node (ref "U13") (pin "AB20") (pinfunction "GND_AB20") (pintype "passive"))
      (node (ref "U13") (pin "AB22") (pinfunction "GND_AB22") (pintype "passive"))
      (node (ref "U13") (pin "AB24") (pinfunction "GND_AB24") (pintype "passive"))
      (node (ref "U13") (pin "AB26") (pinfunction "GND_AB26") (pintype "passive"))
      (node (ref "U13") (pin "AB28") (pinfunction "GND_AB28") (pintype "passive"))
      (node (ref "U13") (pin "AB30") (pinfunction "GND_AB30") (pintype "passive"))
      (node (ref "U13") (pin "AB4") (pinfunction "GND_AB4") (pintype "passive"))
      (node (ref "U13") (pin "AB6") (pinfunction "GND_AB6") (pintype "passive"))
      (node (ref "U13") (pin "AB8") (pinfunction "GND_AB8") (pintype "passive"))
      (node (ref "U13") (pin "AC1") (pinfunction "GND_AC1") (pintype "passive"))
      (node (ref "U13") (pin "AC11") (pinfunction "GND_AC11") (pintype "passive"))
      (node (ref "U13") (pin "AC13") (pinfunction "GND_AC13") (pintype "passive"))
      (node (ref "U13") (pin "AC15") (pinfunction "GND_AC15") (pintype "passive"))
      (node (ref "U13") (pin "AC17") (pinfunction "GND_AC17") (pintype "passive"))
      (node (ref "U13") (pin "AC19") (pinfunction "GND_AC19") (pintype "passive"))
      (node (ref "U13") (pin "AC21") (pinfunction "GND_AC21") (pintype "passive"))
      (node (ref "U13") (pin "AC23") (pinfunction "GND_AC23") (pintype "passive"))
      (node (ref "U13") (pin "AC25") (pinfunction "GND_AC25") (pintype "passive"))
      (node (ref "U13") (pin "AC27") (pinfunction "GND_AC27") (pintype "passive"))
      (node (ref "U13") (pin "AC29") (pinfunction "GND_AC29") (pintype "passive"))
      (node (ref "U13") (pin "AC3") (pinfunction "GND_AC3") (pintype "passive"))
      (node (ref "U13") (pin "AC5") (pinfunction "GND_AC5") (pintype "passive"))
      (node (ref "U13") (pin "AC7") (pinfunction "GND_AC7") (pintype "passive"))
      (node (ref "U13") (pin "AC9") (pinfunction "GND_AC9") (pintype "passive"))
      (node (ref "U13") (pin "AD10") (pinfunction "GND_AD10") (pintype "passive"))
      (node (ref "U13") (pin "AD12") (pinfunction "GND_AD12") (pintype "passive"))
      (node (ref "U13") (pin "AD14") (pinfunction "GND_AD14") (pintype "passive"))
      (node (ref "U13") (pin "AD16") (pinfunction "GND_AD16") (pintype "passive"))
      (node (ref "U13") (pin "AD18") (pinfunction "GND_AD18") (pintype "passive"))
      (node (ref "U13") (pin "AD2") (pinfunction "GND_AD2") (pintype "passive"))
      (node (ref "U13") (pin "AD20") (pinfunction "GND_AD20") (pintype "passive"))
      (node (ref "U13") (pin "AD22") (pinfunction "GND_AD22") (pintype "passive"))
      (node (ref "U13") (pin "AD24") (pinfunction "GND_AD24") (pintype "passive"))
      (node (ref "U13") (pin "AD26") (pinfunction "GND_AD26") (pintype "passive"))
      (node (ref "U13") (pin "AD28") (pinfunction "GND_AD28") (pintype "passive"))
      (node (ref "U13") (pin "AD30") (pinfunction "GND_AD30") (pintype "passive"))
      (node (ref "U13") (pin "AD4") (pinfunction "GND_AD4") (pintype "passive"))
      (node (ref "U13") (pin "AD6") (pinfunction "GND_AD6") (pintype "passive"))
      (node (ref "U13") (pin "AD8") (pinfunction "GND_AD8") (pintype "passive"))
      (node (ref "U13") (pin "AE1") (pinfunction "GND_AE1") (pintype "passive"))
      (node (ref "U13") (pin "AE11") (pinfunction "GND_AE11") (pintype "passive"))
      (node (ref "U13") (pin "AE13") (pinfunction "GND_AE13") (pintype "passive"))
      (node (ref "U13") (pin "AE15") (pinfunction "GND_AE15") (pintype "passive"))
      (node (ref "U13") (pin "AE17") (pinfunction "GND_AE17") (pintype "passive"))
      (node (ref "U13") (pin "AE19") (pinfunction "GND_AE19") (pintype "passive"))
      (node (ref "U13") (pin "AE21") (pinfunction "GND_AE21") (pintype "passive"))
      (node (ref "U13") (pin "AE23") (pinfunction "GND_AE23") (pintype "passive"))
      (node (ref "U13") (pin "AE25") (pinfunction "GND_AE25") (pintype "passive"))
      (node (ref "U13") (pin "AE27") (pinfunction "GND_AE27") (pintype "passive"))
      (node (ref "U13") (pin "AE29") (pinfunction "GND_AE29") (pintype "passive"))
      (node (ref "U13") (pin "AE3") (pinfunction "GND_AE3") (pintype "passive"))
      (node (ref "U13") (pin "AE5") (pinfunction "GND_AE5") (pintype "passive"))
      (node (ref "U13") (pin "AE7") (pinfunction "GND_AE7") (pintype "passive"))
      (node (ref "U13") (pin "AE9") (pinfunction "GND_AE9") (pintype "passive"))
      (node (ref "U13") (pin "AF10") (pinfunction "GND_AF10") (pintype "passive"))
      (node (ref "U13") (pin "AF12") (pinfunction "GND_AF12") (pintype "passive"))
      (node (ref "U13") (pin "AF14") (pinfunction "GND_AF14") (pintype "passive"))
      (node (ref "U13") (pin "AF16") (pinfunction "GND_AF16") (pintype "passive"))
      (node (ref "U13") (pin "AF18") (pinfunction "GND_AF18") (pintype "passive"))
      (node (ref "U13") (pin "AF2") (pinfunction "GND_AF2") (pintype "passive"))
      (node (ref "U13") (pin "AF20") (pinfunction "GND_AF20") (pintype "passive"))
      (node (ref "U13") (pin "AF22") (pinfunction "GND_AF22") (pintype "passive"))
      (node (ref "U13") (pin "AF24") (pinfunction "GND_AF24") (pintype "passive"))
      (node (ref "U13") (pin "AF26") (pinfunction "GND_AF26") (pintype "passive"))
      (node (ref "U13") (pin "AF28") (pinfunction "GND_AF28") (pintype "passive"))
      (node (ref "U13") (pin "AF30") (pinfunction "GND_AF30") (pintype "passive"))
      (node (ref "U13") (pin "AF4") (pinfunction "GND_AF4") (pintype "passive"))
      (node (ref "U13") (pin "AF6") (pinfunction "GND_AF6") (pintype "passive"))
      (node (ref "U13") (pin "AF8") (pinfunction "GND_AF8") (pintype "passive"))
      (node (ref "U13") (pin "AG1") (pinfunction "GND_AG1") (pintype "passive"))
      (node (ref "U13") (pin "AG11") (pinfunction "GND_AG11") (pintype "passive"))
      (node (ref "U13") (pin "AG13") (pinfunction "GND_AG13") (pintype "passive"))
      (node (ref "U13") (pin "AG15") (pinfunction "GND_AG15") (pintype "passive"))
      (node (ref "U13") (pin "AG17") (pinfunction "GND_AG17") (pintype "passive"))
      (node (ref "U13") (pin "AG19") (pinfunction "GND_AG19") (pintype "passive"))
      (node (ref "U13") (pin "AG21") (pinfunction "GND_AG21") (pintype "passive"))
      (node (ref "U13") (pin "AG23") (pinfunction "GND_AG23") (pintype "passive"))
      (node (ref "U13") (pin "AG25") (pinfunction "GND_AG25") (pintype "passive"))
      (node (ref "U13") (pin "AG27") (pinfunction "GND_AG27") (pintype "passive"))
      (node (ref "U13") (pin "AG29") (pinfunction "GND_AG29") (pintype "passive"))
      (node (ref "U13") (pin "AG3") (pinfunction "GND_AG3") (pintype "passive"))
      (node (ref "U13") (pin "AG5") (pinfunction "GND_AG5") (pintype "passive"))
      (node (ref "U13") (pin "AG7") (pinfunction "GND_AG7") (pintype "passive"))
      (node (ref "U13") (pin "AG9") (pinfunction "GND_AG9") (pintype "passive"))
      (node (ref "U13") (pin "AH10") (pinfunction "GND_AH10") (pintype "passive"))
      (node (ref "U13") (pin "AH12") (pinfunction "GND_AH12") (pintype "passive"))
      (node (ref "U13") (pin "AH14") (pinfunction "GND_AH14") (pintype "passive"))
      (node (ref "U13") (pin "AH16") (pinfunction "GND_AH16") (pintype "passive"))
      (node (ref "U13") (pin "AH18") (pinfunction "GND_AH18") (pintype "passive"))
      (node (ref "U13") (pin "AH2") (pinfunction "GND_AH2") (pintype "passive"))
      (node (ref "U13") (pin "AH20") (pinfunction "GND_AH20") (pintype "passive"))
      (node (ref "U13") (pin "AH22") (pinfunction "GND_AH22") (pintype "passive"))
      (node (ref "U13") (pin "AH24") (pinfunction "GND_AH24") (pintype "passive"))
      (node (ref "U13") (pin "AH26") (pinfunction "GND_AH26") (pintype "passive"))
      (node (ref "U13") (pin "AH28") (pinfunction "GND_AH28") (pintype "passive"))
      (node (ref "U13") (pin "AH30") (pinfunction "GND_AH30") (pintype "passive"))
      (node (ref "U13") (pin "AH4") (pinfunction "GND_AH4") (pintype "passive"))
      (node (ref "U13") (pin "AH6") (pinfunction "GND_AH6") (pintype "passive"))
      (node (ref "U13") (pin "AH8") (pinfunction "GND_AH8") (pintype "passive"))
      (node (ref "U13") (pin "AJ1") (pinfunction "GND_AJ1") (pintype "passive"))
      (node (ref "U13") (pin "AJ11") (pinfunction "GND_AJ11") (pintype "passive"))
      (node (ref "U13") (pin "AJ17") (pinfunction "GND_AJ17") (pintype "passive"))
      (node (ref "U13") (pin "AJ27") (pinfunction "GND_AJ27") (pintype "passive"))
      (node (ref "U13") (pin "AJ29") (pinfunction "GND_AJ29") (pintype "passive"))
      (node (ref "U13") (pin "AJ3") (pinfunction "GND_AJ3") (pintype "passive"))
      (node (ref "U13") (pin "AJ4") (pinfunction "GND_AJ4") (pintype "passive"))
      (node (ref "U13") (pin "AJ6") (pinfunction "GND_AJ6") (pintype "passive"))
      (node (ref "U13") (pin "AJ9") (pinfunction "GND_AJ9") (pintype "passive"))
      (node (ref "U13") (pin "AK14") (pinfunction "GND_AK14") (pintype "passive"))
      (node (ref "U13") (pin "AK17") (pinfunction "GND_AK17") (pintype "passive"))
      (node (ref "U13") (pin "AK2") (pinfunction "GND_AK2") (pintype "passive"))
      (node (ref "U13") (pin "AK20") (pinfunction "GND_AK20") (pintype "passive"))
      (node (ref "U13") (pin "AK23") (pinfunction "GND_AK23") (pintype "passive"))
      (node (ref "U13") (pin "AK30") (pinfunction "GND_AK30") (pintype "passive"))
      (node (ref "U13") (pin "B10") (pinfunction "GND_B10") (pintype "passive"))
      (node (ref "U13") (pin "B12") (pinfunction "GND_B12") (pintype "passive"))
      (node (ref "U13") (pin "B14") (pinfunction "GND_B14") (pintype "passive"))
      (node (ref "U13") (pin "B16") (pinfunction "GND_B16") (pintype "passive"))
      (node (ref "U13") (pin "B18") (pinfunction "GND_B18") (pintype "passive"))
      (node (ref "U13") (pin "B2") (pinfunction "GND_B2") (pintype "passive"))
      (node (ref "U13") (pin "B20") (pinfunction "GND_B20") (pintype "passive"))
      (node (ref "U13") (pin "B22") (pinfunction "GND_B22") (pintype "passive"))
      (node (ref "U13") (pin "B24") (pinfunction "GND_B24") (pintype "passive"))
      (node (ref "U13") (pin "B26") (pinfunction "GND_B26") (pintype "passive"))
      (node (ref "U13") (pin "B28") (pinfunction "GND_B28") (pintype "passive"))
      (node (ref "U13") (pin "B30") (pinfunction "GND_B30") (pintype "passive"))
      (node (ref "U13") (pin "B4") (pinfunction "GND_B4") (pintype "passive"))
      (node (ref "U13") (pin "B6") (pinfunction "GND_B6") (pintype "passive"))
      (node (ref "U13") (pin "B8") (pinfunction "GND_B8") (pintype "passive"))
      (node (ref "U13") (pin "C1") (pinfunction "GND_C1") (pintype "passive"))
      (node (ref "U13") (pin "C11") (pinfunction "GND_C11") (pintype "passive"))
      (node (ref "U13") (pin "C13") (pinfunction "GND_C13") (pintype "passive"))
      (node (ref "U13") (pin "C15") (pinfunction "GND_C15") (pintype "passive"))
      (node (ref "U13") (pin "C17") (pinfunction "GND_C17") (pintype "passive"))
      (node (ref "U13") (pin "C19") (pinfunction "GND_C19") (pintype "passive"))
      (node (ref "U13") (pin "C21") (pinfunction "GND_C21") (pintype "passive"))
      (node (ref "U13") (pin "C23") (pinfunction "GND_C23") (pintype "passive"))
      (node (ref "U13") (pin "C25") (pinfunction "GND_C25") (pintype "passive"))
      (node (ref "U13") (pin "C27") (pinfunction "GND_C27") (pintype "passive"))
      (node (ref "U13") (pin "C29") (pinfunction "GND_C29") (pintype "passive"))
      (node (ref "U13") (pin "C3") (pinfunction "GND_C3") (pintype "passive"))
      (node (ref "U13") (pin "C5") (pinfunction "GND_C5") (pintype "passive"))
      (node (ref "U13") (pin "C7") (pinfunction "GND_C7") (pintype "passive"))
      (node (ref "U13") (pin "C9") (pinfunction "GND_C9") (pintype "passive"))
      (node (ref "U13") (pin "D10") (pinfunction "GND_D10") (pintype "passive"))
      (node (ref "U13") (pin "D12") (pinfunction "GND_D12") (pintype "passive"))
      (node (ref "U13") (pin "D14") (pinfunction "GND_D14") (pintype "passive"))
      (node (ref "U13") (pin "D16") (pinfunction "GND_D16") (pintype "passive"))
      (node (ref "U13") (pin "D18") (pinfunction "GND_D18") (pintype "passive"))
      (node (ref "U13") (pin "D2") (pinfunction "GND_D2") (pintype "passive"))
      (node (ref "U13") (pin "D20") (pinfunction "GND_D20") (pintype "passive"))
      (node (ref "U13") (pin "D22") (pinfunction "GND_D22") (pintype "passive"))
      (node (ref "U13") (pin "D24") (pinfunction "GND_D24") (pintype "passive"))
      (node (ref "U13") (pin "D26") (pinfunction "GND_D26") (pintype "passive"))
      (node (ref "U13") (pin "D28") (pinfunction "GND_D28") (pintype "passive"))
      (node (ref "U13") (pin "D30") (pinfunction "GND_D30") (pintype "passive"))
      (node (ref "U13") (pin "D4") (pinfunction "GND_D4") (pintype "passive"))
      (node (ref "U13") (pin "D6") (pinfunction "GND_D6") (pintype "passive"))
      (node (ref "U13") (pin "D8") (pinfunction "GND_D8") (pintype "passive"))
      (node (ref "U13") (pin "E1") (pinfunction "GND_E1") (pintype "passive"))
      (node (ref "U13") (pin "E11") (pinfunction "GND_E11") (pintype "passive"))
      (node (ref "U13") (pin "E13") (pinfunction "GND_E13") (pintype "passive"))
      (node (ref "U13") (pin "E15") (pinfunction "GND_E15") (pintype "passive"))
      (node (ref "U13") (pin "E17") (pinfunction "GND_E17") (pintype "passive"))
      (node (ref "U13") (pin "E19") (pinfunction "GND_E19") (pintype "passive"))
      (node (ref "U13") (pin "E21") (pinfunction "GND_E21") (pintype "passive"))
      (node (ref "U13") (pin "E23") (pinfunction "GND_E23") (pintype "passive"))
      (node (ref "U13") (pin "E25") (pinfunction "GND_E25") (pintype "passive"))
      (node (ref "U13") (pin "E27") (pinfunction "GND_E27") (pintype "passive"))
      (node (ref "U13") (pin "E29") (pinfunction "GND_E29") (pintype "passive"))
      (node (ref "U13") (pin "E3") (pinfunction "GND_E3") (pintype "passive"))
      (node (ref "U13") (pin "E5") (pinfunction "GND_E5") (pintype "passive"))
      (node (ref "U13") (pin "E7") (pinfunction "GND_E7") (pintype "passive"))
      (node (ref "U13") (pin "E9") (pinfunction "GND_E9") (pintype "passive"))
      (node (ref "U13") (pin "F10") (pinfunction "GND_F10") (pintype "passive"))
      (node (ref "U13") (pin "F12") (pinfunction "GND_F12") (pintype "passive"))
      (node (ref "U13") (pin "F14") (pinfunction "GND_F14") (pintype "passive"))
      (node (ref "U13") (pin "F16") (pinfunction "GND_F16") (pintype "passive"))
      (node (ref "U13") (pin "F18") (pinfunction "GND_F18") (pintype "passive"))
      (node (ref "U13") (pin "F2") (pinfunction "GND_F2") (pintype "passive"))
      (node (ref "U13") (pin "F20") (pinfunction "GND_F20") (pintype "passive"))
      (node (ref "U13") (pin "F22") (pinfunction "GND_F22") (pintype "passive"))
      (node (ref "U13") (pin "F24") (pinfunction "GND_F24") (pintype "passive"))
      (node (ref "U13") (pin "F26") (pinfunction "GND_F26") (pintype "passive"))
      (node (ref "U13") (pin "F28") (pinfunction "GND_F28") (pintype "passive"))
      (node (ref "U13") (pin "F30") (pinfunction "GND_F30") (pintype "passive"))
      (node (ref "U13") (pin "F4") (pinfunction "GND_F4") (pintype "passive"))
      (node (ref "U13") (pin "F6") (pinfunction "GND_F6") (pintype "passive"))
      (node (ref "U13") (pin "F8") (pinfunction "GND_F8") (pintype "passive"))
      (node (ref "U13") (pin "G1") (pinfunction "GND_G1") (pintype "passive"))
      (node (ref "U13") (pin "G11") (pinfunction "GND_G11") (pintype "passive"))
      (node (ref "U13") (pin "G13") (pinfunction "GND_G13") (pintype "passive"))
      (node (ref "U13") (pin "G15") (pinfunction "GND_G15") (pintype "passive"))
      (node (ref "U13") (pin "G17") (pinfunction "GND_G17") (pintype "passive"))
      (node (ref "U13") (pin "G19") (pinfunction "GND_G19") (pintype "passive"))
      (node (ref "U13") (pin "G21") (pinfunction "GND_G21") (pintype "passive"))
      (node (ref "U13") (pin "G23") (pinfunction "GND_G23") (pintype "passive"))
      (node (ref "U13") (pin "G25") (pinfunction "GND_G25") (pintype "passive"))
      (node (ref "U13") (pin "G27") (pinfunction "GND_G27") (pintype "passive"))
      (node (ref "U13") (pin "G29") (pinfunction "GND_G29") (pintype "passive"))
      (node (ref "U13") (pin "G3") (pinfunction "GND_G3") (pintype "passive"))
      (node (ref "U13") (pin "G5") (pinfunction "GND_G5") (pintype "passive"))
      (node (ref "U13") (pin "G7") (pinfunction "GND_G7") (pintype "passive"))
      (node (ref "U13") (pin "G9") (pinfunction "GND_G9") (pintype "passive"))
      (node (ref "U13") (pin "H10") (pinfunction "GND_H10") (pintype "passive"))
      (node (ref "U13") (pin "H12") (pinfunction "GND_H12") (pintype "passive"))
      (node (ref "U13") (pin "H14") (pinfunction "GND_H14") (pintype "passive"))
      (node (ref "U13") (pin "H16") (pinfunction "GND_H16") (pintype "passive"))
      (node (ref "U13") (pin "H18") (pinfunction "GND_H18") (pintype "passive"))
      (node (ref "U13") (pin "H2") (pinfunction "GND_H2") (pintype "passive"))
      (node (ref "U13") (pin "H20") (pinfunction "GND_H20") (pintype "passive"))
      (node (ref "U13") (pin "H22") (pinfunction "GND_H22") (pintype "passive"))
      (node (ref "U13") (pin "H24") (pinfunction "GND_H24") (pintype "passive"))
      (node (ref "U13") (pin "H26") (pinfunction "GND_H26") (pintype "passive"))
      (node (ref "U13") (pin "H28") (pinfunction "GND_H28") (pintype "passive"))
      (node (ref "U13") (pin "H30") (pinfunction "GND_H30") (pintype "passive"))
      (node (ref "U13") (pin "H4") (pinfunction "GND_H4") (pintype "passive"))
      (node (ref "U13") (pin "H6") (pinfunction "GND_H6") (pintype "passive"))
      (node (ref "U13") (pin "H8") (pinfunction "GND_H8") (pintype "passive"))
      (node (ref "U13") (pin "J1") (pinfunction "GND_J1") (pintype "passive"))
      (node (ref "U13") (pin "J11") (pinfunction "GND_J11") (pintype "passive"))
      (node (ref "U13") (pin "J13") (pinfunction "GND_J13") (pintype "passive"))
      (node (ref "U13") (pin "J15") (pinfunction "GND_J15") (pintype "passive"))
      (node (ref "U13") (pin "J17") (pinfunction "GND_J17") (pintype "passive"))
      (node (ref "U13") (pin "J19") (pinfunction "GND_J19") (pintype "passive"))
      (node (ref "U13") (pin "J21") (pinfunction "GND_J21") (pintype "passive"))
      (node (ref "U13") (pin "J23") (pinfunction "GND_J23") (pintype "passive"))
      (node (ref "U13") (pin "J25") (pinfunction "GND_J25") (pintype "passive"))
      (node (ref "U13") (pin "J27") (pinfunction "GND_J27") (pintype "passive"))
      (node (ref "U13") (pin "J29") (pinfunction "GND_J29") (pintype "passive"))
      (node (ref "U13") (pin "J3") (pinfunction "GND_J3") (pintype "passive"))
      (node (ref "U13") (pin "J5") (pinfunction "GND_J5") (pintype "passive"))
      (node (ref "U13") (pin "J7") (pinfunction "GND_J7") (pintype "passive"))
      (node (ref "U13") (pin "J9") (pinfunction "GND_J9") (pintype "passive"))
      (node (ref "U13") (pin "K10") (pinfunction "GND_K10") (pintype "passive"))
      (node (ref "U13") (pin "K12") (pinfunction "GND_K12") (pintype "passive"))
      (node (ref "U13") (pin "K14") (pinfunction "GND_K14") (pintype "passive"))
      (node (ref "U13") (pin "K16") (pinfunction "GND_K16") (pintype "passive"))
      (node (ref "U13") (pin "K18") (pinfunction "GND_K18") (pintype "passive"))
      (node (ref "U13") (pin "K2") (pinfunction "GND_K2") (pintype "passive"))
      (node (ref "U13") (pin "K20") (pinfunction "GND_K20") (pintype "passive"))
      (node (ref "U13") (pin "K22") (pinfunction "GND_K22") (pintype "passive"))
      (node (ref "U13") (pin "K24") (pinfunction "GND_K24") (pintype "passive"))
      (node (ref "U13") (pin "K26") (pinfunction "GND_K26") (pintype "passive"))
      (node (ref "U13") (pin "K28") (pinfunction "GND_K28") (pintype "passive"))
      (node (ref "U13") (pin "K30") (pinfunction "GND_K30") (pintype "passive"))
      (node (ref "U13") (pin "K4") (pinfunction "GND_K4") (pintype "passive"))
      (node (ref "U13") (pin "K6") (pinfunction "GND_K6") (pintype "passive"))
      (node (ref "U13") (pin "K8") (pinfunction "GND_K8") (pintype "passive"))
      (node (ref "U13") (pin "L1") (pinfunction "GND_L1") (pintype "passive"))
      (node (ref "U13") (pin "L11") (pinfunction "GND_L11") (pintype "passive"))
      (node (ref "U13") (pin "L13") (pinfunction "GND_L13") (pintype "passive"))
      (node (ref "U13") (pin "L15") (pinfunction "GND_L15") (pintype "passive"))
      (node (ref "U13") (pin "L17") (pinfunction "GND_L17") (pintype "passive"))
      (node (ref "U13") (pin "L19") (pinfunction "GND_L19") (pintype "passive"))
      (node (ref "U13") (pin "L21") (pinfunction "GND_L21") (pintype "passive"))
      (node (ref "U13") (pin "L23") (pinfunction "GND_L23") (pintype "passive"))
      (node (ref "U13") (pin "L25") (pinfunction "GND_L25") (pintype "passive"))
      (node (ref "U13") (pin "L27") (pinfunction "GND_L27") (pintype "passive"))
      (node (ref "U13") (pin "L29") (pinfunction "GND_L29") (pintype "passive"))
      (node (ref "U13") (pin "L3") (pinfunction "GND_L3") (pintype "passive"))
      (node (ref "U13") (pin "L5") (pinfunction "GND_L5") (pintype "passive"))
      (node (ref "U13") (pin "L7") (pinfunction "GND_L7") (pintype "passive"))
      (node (ref "U13") (pin "L9") (pinfunction "GND_L9") (pintype "passive"))
      (node (ref "U13") (pin "M10") (pinfunction "GND_M10") (pintype "passive"))
      (node (ref "U13") (pin "M12") (pinfunction "GND_M12") (pintype "passive"))
      (node (ref "U13") (pin "M14") (pinfunction "GND_M14") (pintype "passive"))
      (node (ref "U13") (pin "M16") (pinfunction "GND_M16") (pintype "passive"))
      (node (ref "U13") (pin "M18") (pinfunction "GND_M18") (pintype "passive"))
      (node (ref "U13") (pin "M2") (pinfunction "GND_M2") (pintype "passive"))
      (node (ref "U13") (pin "M20") (pinfunction "GND_M20") (pintype "passive"))
      (node (ref "U13") (pin "M22") (pinfunction "GND_M22") (pintype "passive"))
      (node (ref "U13") (pin "M24") (pinfunction "GND_M24") (pintype "passive"))
      (node (ref "U13") (pin "M26") (pinfunction "GND_M26") (pintype "passive"))
      (node (ref "U13") (pin "M28") (pinfunction "GND_M28") (pintype "passive"))
      (node (ref "U13") (pin "M30") (pinfunction "GND_M30") (pintype "passive"))
      (node (ref "U13") (pin "M4") (pinfunction "GND_M4") (pintype "passive"))
      (node (ref "U13") (pin "M6") (pinfunction "GND_M6") (pintype "passive"))
      (node (ref "U13") (pin "M8") (pinfunction "GND_M8") (pintype "passive"))
      (node (ref "U13") (pin "N1") (pinfunction "GND_N1") (pintype "passive"))
      (node (ref "U13") (pin "N11") (pinfunction "GND_N11") (pintype "passive"))
      (node (ref "U13") (pin "N13") (pinfunction "GND_N13") (pintype "passive"))
      (node (ref "U13") (pin "N15") (pinfunction "GND_N15") (pintype "passive"))
      (node (ref "U13") (pin "N17") (pinfunction "GND_N17") (pintype "passive"))
      (node (ref "U13") (pin "N19") (pinfunction "GND_N19") (pintype "passive"))
      (node (ref "U13") (pin "N21") (pinfunction "GND_N21") (pintype "passive"))
      (node (ref "U13") (pin "N23") (pinfunction "GND_N23") (pintype "passive"))
      (node (ref "U13") (pin "N25") (pinfunction "GND_N25") (pintype "passive"))
      (node (ref "U13") (pin "N27") (pinfunction "GND_N27") (pintype "passive"))
      (node (ref "U13") (pin "N29") (pinfunction "GND_N29") (pintype "passive"))
      (node (ref "U13") (pin "N3") (pinfunction "GND_N3") (pintype "passive"))
      (node (ref "U13") (pin "N5") (pinfunction "GND_N5") (pintype "passive"))
      (node (ref "U13") (pin "N7") (pinfunction "GND_N7") (pintype "passive"))
      (node (ref "U13") (pin "N9") (pinfunction "GND_N9") (pintype "passive"))
      (node (ref "U13") (pin "P10") (pinfunction "GND_P10") (pintype "passive"))
      (node (ref "U13") (pin "P12") (pinfunction "GND_P12") (pintype "passive"))
      (node (ref "U13") (pin "P14") (pinfunction "GND_P14") (pintype "passive"))
      (node (ref "U13") (pin "P16") (pinfunction "GND_P16") (pintype "passive"))
      (node (ref "U13") (pin "P18") (pinfunction "GND_P18") (pintype "passive"))
      (node (ref "U13") (pin "P2") (pinfunction "GND_P2") (pintype "passive"))
      (node (ref "U13") (pin "P20") (pinfunction "GND_P20") (pintype "passive"))
      (node (ref "U13") (pin "P22") (pinfunction "GND_P22") (pintype "passive"))
      (node (ref "U13") (pin "P24") (pinfunction "GND_P24") (pintype "passive"))
      (node (ref "U13") (pin "P26") (pinfunction "GND_P26") (pintype "passive"))
      (node (ref "U13") (pin "P28") (pinfunction "GND_P28") (pintype "passive"))
      (node (ref "U13") (pin "P30") (pinfunction "GND_P30") (pintype "passive"))
      (node (ref "U13") (pin "P4") (pinfunction "GND_P4") (pintype "passive"))
      (node (ref "U13") (pin "P6") (pinfunction "GND_P6") (pintype "passive"))
      (node (ref "U13") (pin "P8") (pinfunction "GND_P8") (pintype "passive"))
      (node (ref "U13") (pin "R1") (pinfunction "GND_R1") (pintype "passive"))
      (node (ref "U13") (pin "R11") (pinfunction "GND_R11") (pintype "passive"))
      (node (ref "U13") (pin "R13") (pinfunction "GND_R13") (pintype "passive"))
      (node (ref "U13") (pin "R15") (pinfunction "GND_R15") (pintype "passive"))
      (node (ref "U13") (pin "R17") (pinfunction "GND_R17") (pintype "passive"))
      (node (ref "U13") (pin "R19") (pinfunction "GND_R19") (pintype "passive"))
      (node (ref "U13") (pin "R21") (pinfunction "GND_R21") (pintype "passive"))
      (node (ref "U13") (pin "R23") (pinfunction "GND_R23") (pintype "passive"))
      (node (ref "U13") (pin "R25") (pinfunction "GND_R25") (pintype "passive"))
      (node (ref "U13") (pin "R27") (pinfunction "GND_R27") (pintype "passive"))
      (node (ref "U13") (pin "R29") (pinfunction "GND_R29") (pintype "passive"))
      (node (ref "U13") (pin "R3") (pinfunction "GND_R3") (pintype "passive"))
      (node (ref "U13") (pin "R5") (pinfunction "GND_R5") (pintype "passive"))
      (node (ref "U13") (pin "R7") (pinfunction "GND_R7") (pintype "passive"))
      (node (ref "U13") (pin "R9") (pinfunction "GND_R9") (pintype "passive"))
      (node (ref "U13") (pin "T10") (pinfunction "GND_T10") (pintype "passive"))
      (node (ref "U13") (pin "T12") (pinfunction "GND_T12") (pintype "passive"))
      (node (ref "U13") (pin "T14") (pinfunction "GND_T14") (pintype "passive"))
      (node (ref "U13") (pin "T16") (pinfunction "GND_T16") (pintype "passive"))
      (node (ref "U13") (pin "T18") (pinfunction "GND_T18") (pintype "passive"))
      (node (ref "U13") (pin "T2") (pinfunction "GND_T2") (pintype "passive"))
      (node (ref "U13") (pin "T20") (pinfunction "GND_T20") (pintype "passive"))
      (node (ref "U13") (pin "T22") (pinfunction "GND_T22") (pintype "passive"))
      (node (ref "U13") (pin "T24") (pinfunction "GND_T24") (pintype "passive"))
      (node (ref "U13") (pin "T26") (pinfunction "GND_T26") (pintype "passive"))
      (node (ref "U13") (pin "T28") (pinfunction "GND_T28") (pintype "passive"))
      (node (ref "U13") (pin "T30") (pinfunction "GND_T30") (pintype "passive"))
      (node (ref "U13") (pin "T4") (pinfunction "GND_T4") (pintype "passive"))
      (node (ref "U13") (pin "T6") (pinfunction "GND_T6") (pintype "passive"))
      (node (ref "U13") (pin "T8") (pinfunction "GND_T8") (pintype "passive"))
      (node (ref "U13") (pin "U1") (pinfunction "GND_U1") (pintype "passive"))
      (node (ref "U13") (pin "U11") (pinfunction "GND_U11") (pintype "passive"))
      (node (ref "U13") (pin "U13") (pinfunction "GND_U13") (pintype "passive"))
      (node (ref "U13") (pin "U15") (pinfunction "GND_U15") (pintype "passive"))
      (node (ref "U13") (pin "U17") (pinfunction "GND_U17") (pintype "passive"))
      (node (ref "U13") (pin "U19") (pinfunction "GND_U19") (pintype "passive"))
      (node (ref "U13") (pin "U21") (pinfunction "GND_U21") (pintype "passive"))
      (node (ref "U13") (pin "U23") (pinfunction "GND_U23") (pintype "passive"))
      (node (ref "U13") (pin "U25") (pinfunction "GND_U25") (pintype "passive"))
      (node (ref "U13") (pin "U27") (pinfunction "GND_U27") (pintype "passive"))
      (node (ref "U13") (pin "U29") (pinfunction "GND_U29") (pintype "passive"))
      (node (ref "U13") (pin "U3") (pinfunction "GND_U3") (pintype "passive"))
      (node (ref "U13") (pin "U5") (pinfunction "GND_U5") (pintype "passive"))
      (node (ref "U13") (pin "U7") (pinfunction "GND_U7") (pintype "passive"))
      (node (ref "U13") (pin "U9") (pinfunction "GND_U9") (pintype "passive"))
      (node (ref "U13") (pin "V10") (pinfunction "GND_V10") (pintype "passive"))
      (node (ref "U13") (pin "V12") (pinfunction "GND_V12") (pintype "passive"))
      (node (ref "U13") (pin "V14") (pinfunction "GND_V14") (pintype "passive"))
      (node (ref "U13") (pin "V16") (pinfunction "GND_V16") (pintype "passive"))
      (node (ref "U13") (pin "V18") (pinfunction "GND_V18") (pintype "passive"))
      (node (ref "U13") (pin "V2") (pinfunction "GND_V2") (pintype "passive"))
      (node (ref "U13") (pin "V20") (pinfunction "GND_V20") (pintype "passive"))
      (node (ref "U13") (pin "V22") (pinfunction "GND_V22") (pintype "passive"))
      (node (ref "U13") (pin "V24") (pinfunction "GND_V24") (pintype "passive"))
      (node (ref "U13") (pin "V26") (pinfunction "GND_V26") (pintype "passive"))
      (node (ref "U13") (pin "V28") (pinfunction "GND_V28") (pintype "passive"))
      (node (ref "U13") (pin "V30") (pinfunction "GND_V30") (pintype "passive"))
      (node (ref "U13") (pin "V4") (pinfunction "GND_V4") (pintype "passive"))
      (node (ref "U13") (pin "V6") (pinfunction "GND_V6") (pintype "passive"))
      (node (ref "U13") (pin "V8") (pinfunction "GND_V8") (pintype "passive"))
      (node (ref "U13") (pin "W1") (pinfunction "GND_W1") (pintype "passive"))
      (node (ref "U13") (pin "W11") (pinfunction "GND_W11") (pintype "passive"))
      (node (ref "U13") (pin "W13") (pinfunction "GND_W13") (pintype "passive"))
      (node (ref "U13") (pin "W15") (pinfunction "GND_W15") (pintype "passive"))
      (node (ref "U13") (pin "W17") (pinfunction "GND_W17") (pintype "passive"))
      (node (ref "U13") (pin "W19") (pinfunction "GND_W19") (pintype "passive"))
      (node (ref "U13") (pin "W21") (pinfunction "GND_W21") (pintype "passive"))
      (node (ref "U13") (pin "W23") (pinfunction "GND_W23") (pintype "passive"))
      (node (ref "U13") (pin "W25") (pinfunction "GND_W25") (pintype "passive"))
      (node (ref "U13") (pin "W27") (pinfunction "GND_W27") (pintype "passive"))
      (node (ref "U13") (pin "W29") (pinfunction "GND_W29") (pintype "passive"))
      (node (ref "U13") (pin "W3") (pinfunction "GND_W3") (pintype "passive"))
      (node (ref "U13") (pin "W5") (pinfunction "GND_W5") (pintype "passive"))
      (node (ref "U13") (pin "W7") (pinfunction "GND_W7") (pintype "passive"))
      (node (ref "U13") (pin "W9") (pinfunction "GND_W9") (pintype "passive"))
      (node (ref "U13") (pin "Y10") (pinfunction "GND_Y10") (pintype "passive"))
      (node (ref "U13") (pin "Y12") (pinfunction "GND_Y12") (pintype "passive"))
      (node (ref "U13") (pin "Y14") (pinfunction "GND_Y14") (pintype "passive"))
      (node (ref "U13") (pin "Y16") (pinfunction "GND_Y16") (pintype "passive"))
      (node (ref "U13") (pin "Y18") (pinfunction "GND_Y18") (pintype "passive"))
      (node (ref "U13") (pin "Y2") (pinfunction "GND_Y2") (pintype "passive"))
      (node (ref "U13") (pin "Y20") (pinfunction "GND_Y20") (pintype "passive"))
      (node (ref "U13") (pin "Y22") (pinfunction "GND_Y22") (pintype "passive"))
      (node (ref "U13") (pin "Y24") (pinfunction "GND_Y24") (pintype "passive"))
      (node (ref "U13") (pin "Y26") (pinfunction "GND_Y26") (pintype "passive"))
      (node (ref "U13") (pin "Y28") (pinfunction "GND_Y28") (pintype "passive"))
      (node (ref "U13") (pin "Y30") (pinfunction "GND_Y30") (pintype "passive"))
      (node (ref "U13") (pin "Y4") (pinfunction "GND_Y4") (pintype "passive"))
      (node (ref "U13") (pin "Y6") (pinfunction "GND_Y6") (pintype "passive"))
      (node (ref "U13") (pin "Y8") (pinfunction "GND_Y8") (pintype "passive"))
      (node (ref "U2") (pin "A1") (pinfunction "GND_A1") (pintype "passive"))
      (node (ref "U2") (pin "A11") (pinfunction "GND_A11") (pintype "passive"))
      (node (ref "U2") (pin "A13") (pinfunction "GND_A13") (pintype "passive"))
      (node (ref "U2") (pin "A15") (pinfunction "GND_A15") (pintype "passive"))
      (node (ref "U2") (pin "A17") (pinfunction "GND_A17") (pintype "passive"))
      (node (ref "U2") (pin "A19") (pinfunction "GND_A19") (pintype "passive"))
      (node (ref "U2") (pin "A21") (pinfunction "GND_A21") (pintype "passive"))
      (node (ref "U2") (pin "A23") (pinfunction "GND_A23") (pintype "passive"))
      (node (ref "U2") (pin "A25") (pinfunction "GND_A25") (pintype "passive"))
      (node (ref "U2") (pin "A27") (pinfunction "GND_A27") (pintype "passive"))
      (node (ref "U2") (pin "A29") (pinfunction "GND_A29") (pintype "passive"))
      (node (ref "U2") (pin "A3") (pinfunction "GND_A3") (pintype "passive"))
      (node (ref "U2") (pin "A5") (pinfunction "GND_A5") (pintype "passive"))
      (node (ref "U2") (pin "A7") (pinfunction "GND_A7") (pintype "passive"))
      (node (ref "U2") (pin "A9") (pinfunction "GND_A9") (pintype "passive"))
      (node (ref "U2") (pin "AA1") (pinfunction "GND_AA1") (pintype "passive"))
      (node (ref "U2") (pin "AA11") (pinfunction "GND_AA11") (pintype "passive"))
      (node (ref "U2") (pin "AA13") (pinfunction "GND_AA13") (pintype "passive"))
      (node (ref "U2") (pin "AA15") (pinfunction "GND_AA15") (pintype "passive"))
      (node (ref "U2") (pin "AA17") (pinfunction "GND_AA17") (pintype "passive"))
      (node (ref "U2") (pin "AA19") (pinfunction "GND_AA19") (pintype "passive"))
      (node (ref "U2") (pin "AA21") (pinfunction "GND_AA21") (pintype "passive"))
      (node (ref "U2") (pin "AA23") (pinfunction "GND_AA23") (pintype "passive"))
      (node (ref "U2") (pin "AA25") (pinfunction "GND_AA25") (pintype "passive"))
      (node (ref "U2") (pin "AA27") (pinfunction "GND_AA27") (pintype "passive"))
      (node (ref "U2") (pin "AA29") (pinfunction "GND_AA29") (pintype "passive"))
      (node (ref "U2") (pin "AA3") (pinfunction "GND_AA3") (pintype "passive"))
      (node (ref "U2") (pin "AA5") (pinfunction "GND_AA5") (pintype "passive"))
      (node (ref "U2") (pin "AA7") (pinfunction "GND_AA7") (pintype "passive"))
      (node (ref "U2") (pin "AA9") (pinfunction "GND_AA9") (pintype "passive"))
      (node (ref "U2") (pin "AB10") (pinfunction "GND_AB10") (pintype "passive"))
      (node (ref "U2") (pin "AB12") (pinfunction "GND_AB12") (pintype "passive"))
      (node (ref "U2") (pin "AB14") (pinfunction "GND_AB14") (pintype "passive"))
      (node (ref "U2") (pin "AB16") (pinfunction "GND_AB16") (pintype "passive"))
      (node (ref "U2") (pin "AB18") (pinfunction "GND_AB18") (pintype "passive"))
      (node (ref "U2") (pin "AB2") (pinfunction "GND_AB2") (pintype "passive"))
      (node (ref "U2") (pin "AB20") (pinfunction "GND_AB20") (pintype "passive"))
      (node (ref "U2") (pin "AB22") (pinfunction "GND_AB22") (pintype "passive"))
      (node (ref "U2") (pin "AB24") (pinfunction "GND_AB24") (pintype "passive"))
      (node (ref "U2") (pin "AB26") (pinfunction "GND_AB26") (pintype "passive"))
      (node (ref "U2") (pin "AB28") (pinfunction "GND_AB28") (pintype "passive"))
      (node (ref "U2") (pin "AB30") (pinfunction "GND_AB30") (pintype "passive"))
      (node (ref "U2") (pin "AB4") (pinfunction "GND_AB4") (pintype "passive"))
      (node (ref "U2") (pin "AB6") (pinfunction "GND_AB6") (pintype "passive"))
      (node (ref "U2") (pin "AB8") (pinfunction "GND_AB8") (pintype "passive"))
      (node (ref "U2") (pin "AC1") (pinfunction "GND_AC1") (pintype "passive"))
      (node (ref "U2") (pin "AC11") (pinfunction "GND_AC11") (pintype "passive"))
      (node (ref "U2") (pin "AC13") (pinfunction "GND_AC13") (pintype "passive"))
      (node (ref "U2") (pin "AC15") (pinfunction "GND_AC15") (pintype "passive"))
      (node (ref "U2") (pin "AC17") (pinfunction "GND_AC17") (pintype "passive"))
      (node (ref "U2") (pin "AC19") (pinfunction "GND_AC19") (pintype "passive"))
      (node (ref "U2") (pin "AC21") (pinfunction "GND_AC21") (pintype "passive"))
      (node (ref "U2") (pin "AC23") (pinfunction "GND_AC23") (pintype "passive"))
      (node (ref "U2") (pin "AC25") (pinfunction "GND_AC25") (pintype "passive"))
      (node (ref "U2") (pin "AC27") (pinfunction "GND_AC27") (pintype "passive"))
      (node (ref "U2") (pin "AC29") (pinfunction "GND_AC29") (pintype "passive"))
      (node (ref "U2") (pin "AC3") (pinfunction "GND_AC3") (pintype "passive"))
      (node (ref "U2") (pin "AC5") (pinfunction "GND_AC5") (pintype "passive"))
      (node (ref "U2") (pin "AC7") (pinfunction "GND_AC7") (pintype "passive"))
      (node (ref "U2") (pin "AC9") (pinfunction "GND_AC9") (pintype "passive"))
      (node (ref "U2") (pin "AD10") (pinfunction "GND_AD10") (pintype "passive"))
      (node (ref "U2") (pin "AD12") (pinfunction "GND_AD12") (pintype "passive"))
      (node (ref "U2") (pin "AD14") (pinfunction "GND_AD14") (pintype "passive"))
      (node (ref "U2") (pin "AD16") (pinfunction "GND_AD16") (pintype "passive"))
      (node (ref "U2") (pin "AD18") (pinfunction "GND_AD18") (pintype "passive"))
      (node (ref "U2") (pin "AD2") (pinfunction "GND_AD2") (pintype "passive"))
      (node (ref "U2") (pin "AD20") (pinfunction "GND_AD20") (pintype "passive"))
      (node (ref "U2") (pin "AD22") (pinfunction "GND_AD22") (pintype "passive"))
      (node (ref "U2") (pin "AD24") (pinfunction "GND_AD24") (pintype "passive"))
      (node (ref "U2") (pin "AD26") (pinfunction "GND_AD26") (pintype "passive"))
      (node (ref "U2") (pin "AD28") (pinfunction "GND_AD28") (pintype "passive"))
      (node (ref "U2") (pin "AD30") (pinfunction "GND_AD30") (pintype "passive"))
      (node (ref "U2") (pin "AD4") (pinfunction "GND_AD4") (pintype "passive"))
      (node (ref "U2") (pin "AD6") (pinfunction "GND_AD6") (pintype "passive"))
      (node (ref "U2") (pin "AD8") (pinfunction "GND_AD8") (pintype "passive"))
      (node (ref "U2") (pin "AE1") (pinfunction "GND_AE1") (pintype "passive"))
      (node (ref "U2") (pin "AE11") (pinfunction "GND_AE11") (pintype "passive"))
      (node (ref "U2") (pin "AE13") (pinfunction "GND_AE13") (pintype "passive"))
      (node (ref "U2") (pin "AE15") (pinfunction "GND_AE15") (pintype "passive"))
      (node (ref "U2") (pin "AE17") (pinfunction "GND_AE17") (pintype "passive"))
      (node (ref "U2") (pin "AE19") (pinfunction "GND_AE19") (pintype "passive"))
      (node (ref "U2") (pin "AE21") (pinfunction "GND_AE21") (pintype "passive"))
      (node (ref "U2") (pin "AE23") (pinfunction "GND_AE23") (pintype "passive"))
      (node (ref "U2") (pin "AE25") (pinfunction "GND_AE25") (pintype "passive"))
      (node (ref "U2") (pin "AE27") (pinfunction "GND_AE27") (pintype "passive"))
      (node (ref "U2") (pin "AE29") (pinfunction "GND_AE29") (pintype "passive"))
      (node (ref "U2") (pin "AE3") (pinfunction "GND_AE3") (pintype "passive"))
      (node (ref "U2") (pin "AE5") (pinfunction "GND_AE5") (pintype "passive"))
      (node (ref "U2") (pin "AE7") (pinfunction "GND_AE7") (pintype "passive"))
      (node (ref "U2") (pin "AE9") (pinfunction "GND_AE9") (pintype "passive"))
      (node (ref "U2") (pin "AF10") (pinfunction "GND_AF10") (pintype "passive"))
      (node (ref "U2") (pin "AF12") (pinfunction "GND_AF12") (pintype "passive"))
      (node (ref "U2") (pin "AF14") (pinfunction "GND_AF14") (pintype "passive"))
      (node (ref "U2") (pin "AF16") (pinfunction "GND_AF16") (pintype "passive"))
      (node (ref "U2") (pin "AF18") (pinfunction "GND_AF18") (pintype "passive"))
      (node (ref "U2") (pin "AF2") (pinfunction "GND_AF2") (pintype "passive"))
      (node (ref "U2") (pin "AF20") (pinfunction "GND_AF20") (pintype "passive"))
      (node (ref "U2") (pin "AF22") (pinfunction "GND_AF22") (pintype "passive"))
      (node (ref "U2") (pin "AF24") (pinfunction "GND_AF24") (pintype "passive"))
      (node (ref "U2") (pin "AF26") (pinfunction "GND_AF26") (pintype "passive"))
      (node (ref "U2") (pin "AF28") (pinfunction "GND_AF28") (pintype "passive"))
      (node (ref "U2") (pin "AF30") (pinfunction "GND_AF30") (pintype "passive"))
      (node (ref "U2") (pin "AF4") (pinfunction "GND_AF4") (pintype "passive"))
      (node (ref "U2") (pin "AF6") (pinfunction "GND_AF6") (pintype "passive"))
      (node (ref "U2") (pin "AF8") (pinfunction "GND_AF8") (pintype "passive"))
      (node (ref "U2") (pin "AG1") (pinfunction "GND_AG1") (pintype "passive"))
      (node (ref "U2") (pin "AG11") (pinfunction "GND_AG11") (pintype "passive"))
      (node (ref "U2") (pin "AG13") (pinfunction "GND_AG13") (pintype "passive"))
      (node (ref "U2") (pin "AG15") (pinfunction "GND_AG15") (pintype "passive"))
      (node (ref "U2") (pin "AG17") (pinfunction "GND_AG17") (pintype "passive"))
      (node (ref "U2") (pin "AG19") (pinfunction "GND_AG19") (pintype "passive"))
      (node (ref "U2") (pin "AG21") (pinfunction "GND_AG21") (pintype "passive"))
      (node (ref "U2") (pin "AG23") (pinfunction "GND_AG23") (pintype "passive"))
      (node (ref "U2") (pin "AG25") (pinfunction "GND_AG25") (pintype "passive"))
      (node (ref "U2") (pin "AG27") (pinfunction "GND_AG27") (pintype "passive"))
      (node (ref "U2") (pin "AG29") (pinfunction "GND_AG29") (pintype "passive"))
      (node (ref "U2") (pin "AG3") (pinfunction "GND_AG3") (pintype "passive"))
      (node (ref "U2") (pin "AG5") (pinfunction "GND_AG5") (pintype "passive"))
      (node (ref "U2") (pin "AG7") (pinfunction "GND_AG7") (pintype "passive"))
      (node (ref "U2") (pin "AG9") (pinfunction "GND_AG9") (pintype "passive"))
      (node (ref "U2") (pin "AH10") (pinfunction "GND_AH10") (pintype "passive"))
      (node (ref "U2") (pin "AH12") (pinfunction "GND_AH12") (pintype "passive"))
      (node (ref "U2") (pin "AH14") (pinfunction "GND_AH14") (pintype "passive"))
      (node (ref "U2") (pin "AH16") (pinfunction "GND_AH16") (pintype "passive"))
      (node (ref "U2") (pin "AH18") (pinfunction "GND_AH18") (pintype "passive"))
      (node (ref "U2") (pin "AH2") (pinfunction "GND_AH2") (pintype "passive"))
      (node (ref "U2") (pin "AH20") (pinfunction "GND_AH20") (pintype "passive"))
      (node (ref "U2") (pin "AH22") (pinfunction "GND_AH22") (pintype "passive"))
      (node (ref "U2") (pin "AH24") (pinfunction "GND_AH24") (pintype "passive"))
      (node (ref "U2") (pin "AH26") (pinfunction "GND_AH26") (pintype "passive"))
      (node (ref "U2") (pin "AH28") (pinfunction "GND_AH28") (pintype "passive"))
      (node (ref "U2") (pin "AH30") (pinfunction "GND_AH30") (pintype "passive"))
      (node (ref "U2") (pin "AH4") (pinfunction "GND_AH4") (pintype "passive"))
      (node (ref "U2") (pin "AH6") (pinfunction "GND_AH6") (pintype "passive"))
      (node (ref "U2") (pin "AH8") (pinfunction "GND_AH8") (pintype "passive"))
      (node (ref "U2") (pin "AJ1") (pinfunction "GND_AJ1") (pintype "passive"))
      (node (ref "U2") (pin "AJ11") (pinfunction "GND_AJ11") (pintype "passive"))
      (node (ref "U2") (pin "AJ17") (pinfunction "GND_AJ17") (pintype "passive"))
      (node (ref "U2") (pin "AJ27") (pinfunction "GND_AJ27") (pintype "passive"))
      (node (ref "U2") (pin "AJ29") (pinfunction "GND_AJ29") (pintype "passive"))
      (node (ref "U2") (pin "AJ3") (pinfunction "GND_AJ3") (pintype "passive"))
      (node (ref "U2") (pin "AJ4") (pinfunction "GND_AJ4") (pintype "passive"))
      (node (ref "U2") (pin "AJ6") (pinfunction "GND_AJ6") (pintype "passive"))
      (node (ref "U2") (pin "AJ9") (pinfunction "GND_AJ9") (pintype "passive"))
      (node (ref "U2") (pin "AK14") (pinfunction "GND_AK14") (pintype "passive"))
      (node (ref "U2") (pin "AK17") (pinfunction "GND_AK17") (pintype "passive"))
      (node (ref "U2") (pin "AK2") (pinfunction "GND_AK2") (pintype "passive"))
      (node (ref "U2") (pin "AK20") (pinfunction "GND_AK20") (pintype "passive"))
      (node (ref "U2") (pin "AK23") (pinfunction "GND_AK23") (pintype "passive"))
      (node (ref "U2") (pin "AK30") (pinfunction "GND_AK30") (pintype "passive"))
      (node (ref "U2") (pin "B10") (pinfunction "GND_B10") (pintype "passive"))
      (node (ref "U2") (pin "B12") (pinfunction "GND_B12") (pintype "passive"))
      (node (ref "U2") (pin "B14") (pinfunction "GND_B14") (pintype "passive"))
      (node (ref "U2") (pin "B16") (pinfunction "GND_B16") (pintype "passive"))
      (node (ref "U2") (pin "B18") (pinfunction "GND_B18") (pintype "passive"))
      (node (ref "U2") (pin "B2") (pinfunction "GND_B2") (pintype "passive"))
      (node (ref "U2") (pin "B20") (pinfunction "GND_B20") (pintype "passive"))
      (node (ref "U2") (pin "B22") (pinfunction "GND_B22") (pintype "passive"))
      (node (ref "U2") (pin "B24") (pinfunction "GND_B24") (pintype "passive"))
      (node (ref "U2") (pin "B26") (pinfunction "GND_B26") (pintype "passive"))
      (node (ref "U2") (pin "B28") (pinfunction "GND_B28") (pintype "passive"))
      (node (ref "U2") (pin "B30") (pinfunction "GND_B30") (pintype "passive"))
      (node (ref "U2") (pin "B4") (pinfunction "GND_B4") (pintype "passive"))
      (node (ref "U2") (pin "B6") (pinfunction "GND_B6") (pintype "passive"))
      (node (ref "U2") (pin "B8") (pinfunction "GND_B8") (pintype "passive"))
      (node (ref "U2") (pin "C1") (pinfunction "GND_C1") (pintype "passive"))
      (node (ref "U2") (pin "C11") (pinfunction "GND_C11") (pintype "passive"))
      (node (ref "U2") (pin "C13") (pinfunction "GND_C13") (pintype "passive"))
      (node (ref "U2") (pin "C15") (pinfunction "GND_C15") (pintype "passive"))
      (node (ref "U2") (pin "C17") (pinfunction "GND_C17") (pintype "passive"))
      (node (ref "U2") (pin "C19") (pinfunction "GND_C19") (pintype "passive"))
      (node (ref "U2") (pin "C21") (pinfunction "GND_C21") (pintype "passive"))
      (node (ref "U2") (pin "C23") (pinfunction "GND_C23") (pintype "passive"))
      (node (ref "U2") (pin "C25") (pinfunction "GND_C25") (pintype "passive"))
      (node (ref "U2") (pin "C27") (pinfunction "GND_C27") (pintype "passive"))
      (node (ref "U2") (pin "C29") (pinfunction "GND_C29") (pintype "passive"))
      (node (ref "U2") (pin "C3") (pinfunction "GND_C3") (pintype "passive"))
      (node (ref "U2") (pin "C5") (pinfunction "GND_C5") (pintype "passive"))
      (node (ref "U2") (pin "C7") (pinfunction "GND_C7") (pintype "passive"))
      (node (ref "U2") (pin "C9") (pinfunction "GND_C9") (pintype "passive"))
      (node (ref "U2") (pin "D10") (pinfunction "GND_D10") (pintype "passive"))
      (node (ref "U2") (pin "D12") (pinfunction "GND_D12") (pintype "passive"))
      (node (ref "U2") (pin "D14") (pinfunction "GND_D14") (pintype "passive"))
      (node (ref "U2") (pin "D16") (pinfunction "GND_D16") (pintype "passive"))
      (node (ref "U2") (pin "D18") (pinfunction "GND_D18") (pintype "passive"))
      (node (ref "U2") (pin "D2") (pinfunction "GND_D2") (pintype "passive"))
      (node (ref "U2") (pin "D20") (pinfunction "GND_D20") (pintype "passive"))
      (node (ref "U2") (pin "D22") (pinfunction "GND_D22") (pintype "passive"))
      (node (ref "U2") (pin "D24") (pinfunction "GND_D24") (pintype "passive"))
      (node (ref "U2") (pin "D26") (pinfunction "GND_D26") (pintype "passive"))
      (node (ref "U2") (pin "D28") (pinfunction "GND_D28") (pintype "passive"))
      (node (ref "U2") (pin "D30") (pinfunction "GND_D30") (pintype "passive"))
      (node (ref "U2") (pin "D4") (pinfunction "GND_D4") (pintype "passive"))
      (node (ref "U2") (pin "D6") (pinfunction "GND_D6") (pintype "passive"))
      (node (ref "U2") (pin "D8") (pinfunction "GND_D8") (pintype "passive"))
      (node (ref "U2") (pin "E1") (pinfunction "GND_E1") (pintype "passive"))
      (node (ref "U2") (pin "E11") (pinfunction "GND_E11") (pintype "passive"))
      (node (ref "U2") (pin "E13") (pinfunction "GND_E13") (pintype "passive"))
      (node (ref "U2") (pin "E15") (pinfunction "GND_E15") (pintype "passive"))
      (node (ref "U2") (pin "E17") (pinfunction "GND_E17") (pintype "passive"))
      (node (ref "U2") (pin "E19") (pinfunction "GND_E19") (pintype "passive"))
      (node (ref "U2") (pin "E21") (pinfunction "GND_E21") (pintype "passive"))
      (node (ref "U2") (pin "E23") (pinfunction "GND_E23") (pintype "passive"))
      (node (ref "U2") (pin "E25") (pinfunction "GND_E25") (pintype "passive"))
      (node (ref "U2") (pin "E27") (pinfunction "GND_E27") (pintype "passive"))
      (node (ref "U2") (pin "E29") (pinfunction "GND_E29") (pintype "passive"))
      (node (ref "U2") (pin "E3") (pinfunction "GND_E3") (pintype "passive"))
      (node (ref "U2") (pin "E5") (pinfunction "GND_E5") (pintype "passive"))
      (node (ref "U2") (pin "E7") (pinfunction "GND_E7") (pintype "passive"))
      (node (ref "U2") (pin "E9") (pinfunction "GND_E9") (pintype "passive"))
      (node (ref "U2") (pin "F10") (pinfunction "GND_F10") (pintype "passive"))
      (node (ref "U2") (pin "F12") (pinfunction "GND_F12") (pintype "passive"))
      (node (ref "U2") (pin "F14") (pinfunction "GND_F14") (pintype "passive"))
      (node (ref "U2") (pin "F16") (pinfunction "GND_F16") (pintype "passive"))
      (node (ref "U2") (pin "F18") (pinfunction "GND_F18") (pintype "passive"))
      (node (ref "U2") (pin "F2") (pinfunction "GND_F2") (pintype "passive"))
      (node (ref "U2") (pin "F20") (pinfunction "GND_F20") (pintype "passive"))
      (node (ref "U2") (pin "F22") (pinfunction "GND_F22") (pintype "passive"))
      (node (ref "U2") (pin "F24") (pinfunction "GND_F24") (pintype "passive"))
      (node (ref "U2") (pin "F26") (pinfunction "GND_F26") (pintype "passive"))
      (node (ref "U2") (pin "F28") (pinfunction "GND_F28") (pintype "passive"))
      (node (ref "U2") (pin "F30") (pinfunction "GND_F30") (pintype "passive"))
      (node (ref "U2") (pin "F4") (pinfunction "GND_F4") (pintype "passive"))
      (node (ref "U2") (pin "F6") (pinfunction "GND_F6") (pintype "passive"))
      (node (ref "U2") (pin "F8") (pinfunction "GND_F8") (pintype "passive"))
      (node (ref "U2") (pin "G1") (pinfunction "GND_G1") (pintype "passive"))
      (node (ref "U2") (pin "G11") (pinfunction "GND_G11") (pintype "passive"))
      (node (ref "U2") (pin "G13") (pinfunction "GND_G13") (pintype "passive"))
      (node (ref "U2") (pin "G15") (pinfunction "GND_G15") (pintype "passive"))
      (node (ref "U2") (pin "G17") (pinfunction "GND_G17") (pintype "passive"))
      (node (ref "U2") (pin "G19") (pinfunction "GND_G19") (pintype "passive"))
      (node (ref "U2") (pin "G21") (pinfunction "GND_G21") (pintype "passive"))
      (node (ref "U2") (pin "G23") (pinfunction "GND_G23") (pintype "passive"))
      (node (ref "U2") (pin "G25") (pinfunction "GND_G25") (pintype "passive"))
      (node (ref "U2") (pin "G27") (pinfunction "GND_G27") (pintype "passive"))
      (node (ref "U2") (pin "G29") (pinfunction "GND_G29") (pintype "passive"))
      (node (ref "U2") (pin "G3") (pinfunction "GND_G3") (pintype "passive"))
      (node (ref "U2") (pin "G5") (pinfunction "GND_G5") (pintype "passive"))
      (node (ref "U2") (pin "G7") (pinfunction "GND_G7") (pintype "passive"))
      (node (ref "U2") (pin "G9") (pinfunction "GND_G9") (pintype "passive"))
      (node (ref "U2") (pin "H10") (pinfunction "GND_H10") (pintype "passive"))
      (node (ref "U2") (pin "H12") (pinfunction "GND_H12") (pintype "passive"))
      (node (ref "U2") (pin "H14") (pinfunction "GND_H14") (pintype "passive"))
      (node (ref "U2") (pin "H16") (pinfunction "GND_H16") (pintype "passive"))
      (node (ref "U2") (pin "H18") (pinfunction "GND_H18") (pintype "passive"))
      (node (ref "U2") (pin "H2") (pinfunction "GND_H2") (pintype "passive"))
      (node (ref "U2") (pin "H20") (pinfunction "GND_H20") (pintype "passive"))
      (node (ref "U2") (pin "H22") (pinfunction "GND_H22") (pintype "passive"))
      (node (ref "U2") (pin "H24") (pinfunction "GND_H24") (pintype "passive"))
      (node (ref "U2") (pin "H26") (pinfunction "GND_H26") (pintype "passive"))
      (node (ref "U2") (pin "H28") (pinfunction "GND_H28") (pintype "passive"))
      (node (ref "U2") (pin "H30") (pinfunction "GND_H30") (pintype "passive"))
      (node (ref "U2") (pin "H4") (pinfunction "GND_H4") (pintype "passive"))
      (node (ref "U2") (pin "H6") (pinfunction "GND_H6") (pintype "passive"))
      (node (ref "U2") (pin "H8") (pinfunction "GND_H8") (pintype "passive"))
      (node (ref "U2") (pin "J1") (pinfunction "GND_J1") (pintype "passive"))
      (node (ref "U2") (pin "J11") (pinfunction "GND_J11") (pintype "passive"))
      (node (ref "U2") (pin "J13") (pinfunction "GND_J13") (pintype "passive"))
      (node (ref "U2") (pin "J15") (pinfunction "GND_J15") (pintype "passive"))
      (node (ref "U2") (pin "J17") (pinfunction "GND_J17") (pintype "passive"))
      (node (ref "U2") (pin "J19") (pinfunction "GND_J19") (pintype "passive"))
      (node (ref "U2") (pin "J21") (pinfunction "GND_J21") (pintype "passive"))
      (node (ref "U2") (pin "J23") (pinfunction "GND_J23") (pintype "passive"))
      (node (ref "U2") (pin "J25") (pinfunction "GND_J25") (pintype "passive"))
      (node (ref "U2") (pin "J27") (pinfunction "GND_J27") (pintype "passive"))
      (node (ref "U2") (pin "J29") (pinfunction "GND_J29") (pintype "passive"))
      (node (ref "U2") (pin "J3") (pinfunction "GND_J3") (pintype "passive"))
      (node (ref "U2") (pin "J5") (pinfunction "GND_J5") (pintype "passive"))
      (node (ref "U2") (pin "J7") (pinfunction "GND_J7") (pintype "passive"))
      (node (ref "U2") (pin "J9") (pinfunction "GND_J9") (pintype "passive"))
      (node (ref "U2") (pin "K10") (pinfunction "GND_K10") (pintype "passive"))
      (node (ref "U2") (pin "K12") (pinfunction "GND_K12") (pintype "passive"))
      (node (ref "U2") (pin "K14") (pinfunction "GND_K14") (pintype "passive"))
      (node (ref "U2") (pin "K16") (pinfunction "GND_K16") (pintype "passive"))
      (node (ref "U2") (pin "K18") (pinfunction "GND_K18") (pintype "passive"))
      (node (ref "U2") (pin "K2") (pinfunction "GND_K2") (pintype "passive"))
      (node (ref "U2") (pin "K20") (pinfunction "GND_K20") (pintype "passive"))
      (node (ref "U2") (pin "K22") (pinfunction "GND_K22") (pintype "passive"))
      (node (ref "U2") (pin "K24") (pinfunction "GND_K24") (pintype "passive"))
      (node (ref "U2") (pin "K26") (pinfunction "GND_K26") (pintype "passive"))
      (node (ref "U2") (pin "K28") (pinfunction "GND_K28") (pintype "passive"))
      (node (ref "U2") (pin "K30") (pinfunction "GND_K30") (pintype "passive"))
      (node (ref "U2") (pin "K4") (pinfunction "GND_K4") (pintype "passive"))
      (node (ref "U2") (pin "K6") (pinfunction "GND_K6") (pintype "passive"))
      (node (ref "U2") (pin "K8") (pinfunction "GND_K8") (pintype "passive"))
      (node (ref "U2") (pin "L1") (pinfunction "GND_L1") (pintype "passive"))
      (node (ref "U2") (pin "L11") (pinfunction "GND_L11") (pintype "passive"))
      (node (ref "U2") (pin "L13") (pinfunction "GND_L13") (pintype "passive"))
      (node (ref "U2") (pin "L15") (pinfunction "GND_L15") (pintype "passive"))
      (node (ref "U2") (pin "L17") (pinfunction "GND_L17") (pintype "passive"))
      (node (ref "U2") (pin "L19") (pinfunction "GND_L19") (pintype "passive"))
      (node (ref "U2") (pin "L21") (pinfunction "GND_L21") (pintype "passive"))
      (node (ref "U2") (pin "L23") (pinfunction "GND_L23") (pintype "passive"))
      (node (ref "U2") (pin "L25") (pinfunction "GND_L25") (pintype "passive"))
      (node (ref "U2") (pin "L27") (pinfunction "GND_L27") (pintype "passive"))
      (node (ref "U2") (pin "L29") (pinfunction "GND_L29") (pintype "passive"))
      (node (ref "U2") (pin "L3") (pinfunction "GND_L3") (pintype "passive"))
      (node (ref "U2") (pin "L5") (pinfunction "GND_L5") (pintype "passive"))
      (node (ref "U2") (pin "L7") (pinfunction "GND_L7") (pintype "passive"))
      (node (ref "U2") (pin "L9") (pinfunction "GND_L9") (pintype "passive"))
      (node (ref "U2") (pin "M10") (pinfunction "GND_M10") (pintype "passive"))
      (node (ref "U2") (pin "M12") (pinfunction "GND_M12") (pintype "passive"))
      (node (ref "U2") (pin "M14") (pinfunction "GND_M14") (pintype "passive"))
      (node (ref "U2") (pin "M16") (pinfunction "GND_M16") (pintype "passive"))
      (node (ref "U2") (pin "M18") (pinfunction "GND_M18") (pintype "passive"))
      (node (ref "U2") (pin "M2") (pinfunction "GND_M2") (pintype "passive"))
      (node (ref "U2") (pin "M20") (pinfunction "GND_M20") (pintype "passive"))
      (node (ref "U2") (pin "M22") (pinfunction "GND_M22") (pintype "passive"))
      (node (ref "U2") (pin "M24") (pinfunction "GND_M24") (pintype "passive"))
      (node (ref "U2") (pin "M26") (pinfunction "GND_M26") (pintype "passive"))
      (node (ref "U2") (pin "M28") (pinfunction "GND_M28") (pintype "passive"))
      (node (ref "U2") (pin "M30") (pinfunction "GND_M30") (pintype "passive"))
      (node (ref "U2") (pin "M4") (pinfunction "GND_M4") (pintype "passive"))
      (node (ref "U2") (pin "M6") (pinfunction "GND_M6") (pintype "passive"))
      (node (ref "U2") (pin "M8") (pinfunction "GND_M8") (pintype "passive"))
      (node (ref "U2") (pin "N1") (pinfunction "GND_N1") (pintype "passive"))
      (node (ref "U2") (pin "N11") (pinfunction "GND_N11") (pintype "passive"))
      (node (ref "U2") (pin "N13") (pinfunction "GND_N13") (pintype "passive"))
      (node (ref "U2") (pin "N15") (pinfunction "GND_N15") (pintype "passive"))
      (node (ref "U2") (pin "N17") (pinfunction "GND_N17") (pintype "passive"))
      (node (ref "U2") (pin "N19") (pinfunction "GND_N19") (pintype "passive"))
      (node (ref "U2") (pin "N21") (pinfunction "GND_N21") (pintype "passive"))
      (node (ref "U2") (pin "N23") (pinfunction "GND_N23") (pintype "passive"))
      (node (ref "U2") (pin "N25") (pinfunction "GND_N25") (pintype "passive"))
      (node (ref "U2") (pin "N27") (pinfunction "GND_N27") (pintype "passive"))
      (node (ref "U2") (pin "N29") (pinfunction "GND_N29") (pintype "passive"))
      (node (ref "U2") (pin "N3") (pinfunction "GND_N3") (pintype "passive"))
      (node (ref "U2") (pin "N5") (pinfunction "GND_N5") (pintype "passive"))
      (node (ref "U2") (pin "N7") (pinfunction "GND_N7") (pintype "passive"))
      (node (ref "U2") (pin "N9") (pinfunction "GND_N9") (pintype "passive"))
      (node (ref "U2") (pin "P10") (pinfunction "GND_P10") (pintype "passive"))
      (node (ref "U2") (pin "P12") (pinfunction "GND_P12") (pintype "passive"))
      (node (ref "U2") (pin "P14") (pinfunction "GND_P14") (pintype "passive"))
      (node (ref "U2") (pin "P16") (pinfunction "GND_P16") (pintype "passive"))
      (node (ref "U2") (pin "P18") (pinfunction "GND_P18") (pintype "passive"))
      (node (ref "U2") (pin "P2") (pinfunction "GND_P2") (pintype "passive"))
      (node (ref "U2") (pin "P20") (pinfunction "GND_P20") (pintype "passive"))
      (node (ref "U2") (pin "P22") (pinfunction "GND_P22") (pintype "passive"))
      (node (ref "U2") (pin "P24") (pinfunction "GND_P24") (pintype "passive"))
      (node (ref "U2") (pin "P26") (pinfunction "GND_P26") (pintype "passive"))
      (node (ref "U2") (pin "P28") (pinfunction "GND_P28") (pintype "passive"))
      (node (ref "U2") (pin "P30") (pinfunction "GND_P30") (pintype "passive"))
      (node (ref "U2") (pin "P4") (pinfunction "GND_P4") (pintype "passive"))
      (node (ref "U2") (pin "P6") (pinfunction "GND_P6") (pintype "passive"))
      (node (ref "U2") (pin "P8") (pinfunction "GND_P8") (pintype "passive"))
      (node (ref "U2") (pin "R1") (pinfunction "GND_R1") (pintype "passive"))
      (node (ref "U2") (pin "R11") (pinfunction "GND_R11") (pintype "passive"))
      (node (ref "U2") (pin "R13") (pinfunction "GND_R13") (pintype "passive"))
      (node (ref "U2") (pin "R15") (pinfunction "GND_R15") (pintype "passive"))
      (node (ref "U2") (pin "R17") (pinfunction "GND_R17") (pintype "passive"))
      (node (ref "U2") (pin "R19") (pinfunction "GND_R19") (pintype "passive"))
      (node (ref "U2") (pin "R21") (pinfunction "GND_R21") (pintype "passive"))
      (node (ref "U2") (pin "R23") (pinfunction "GND_R23") (pintype "passive"))
      (node (ref "U2") (pin "R25") (pinfunction "GND_R25") (pintype "passive"))
      (node (ref "U2") (pin "R27") (pinfunction "GND_R27") (pintype "passive"))
      (node (ref "U2") (pin "R29") (pinfunction "GND_R29") (pintype "passive"))
      (node (ref "U2") (pin "R3") (pinfunction "GND_R3") (pintype "passive"))
      (node (ref "U2") (pin "R5") (pinfunction "GND_R5") (pintype "passive"))
      (node (ref "U2") (pin "R7") (pinfunction "GND_R7") (pintype "passive"))
      (node (ref "U2") (pin "R9") (pinfunction "GND_R9") (pintype "passive"))
      (node (ref "U2") (pin "T10") (pinfunction "GND_T10") (pintype "passive"))
      (node (ref "U2") (pin "T12") (pinfunction "GND_T12") (pintype "passive"))
      (node (ref "U2") (pin "T14") (pinfunction "GND_T14") (pintype "passive"))
      (node (ref "U2") (pin "T16") (pinfunction "GND_T16") (pintype "passive"))
      (node (ref "U2") (pin "T18") (pinfunction "GND_T18") (pintype "passive"))
      (node (ref "U2") (pin "T2") (pinfunction "GND_T2") (pintype "passive"))
      (node (ref "U2") (pin "T20") (pinfunction "GND_T20") (pintype "passive"))
      (node (ref "U2") (pin "T22") (pinfunction "GND_T22") (pintype "passive"))
      (node (ref "U2") (pin "T24") (pinfunction "GND_T24") (pintype "passive"))
      (node (ref "U2") (pin "T26") (pinfunction "GND_T26") (pintype "passive"))
      (node (ref "U2") (pin "T28") (pinfunction "GND_T28") (pintype "passive"))
      (node (ref "U2") (pin "T30") (pinfunction "GND_T30") (pintype "passive"))
      (node (ref "U2") (pin "T4") (pinfunction "GND_T4") (pintype "passive"))
      (node (ref "U2") (pin "T6") (pinfunction "GND_T6") (pintype "passive"))
      (node (ref "U2") (pin "T8") (pinfunction "GND_T8") (pintype "passive"))
      (node (ref "U2") (pin "U1") (pinfunction "GND_U1") (pintype "passive"))
      (node (ref "U2") (pin "U11") (pinfunction "GND_U11") (pintype "passive"))
      (node (ref "U2") (pin "U13") (pinfunction "GND_U13") (pintype "passive"))
      (node (ref "U2") (pin "U15") (pinfunction "GND_U15") (pintype "passive"))
      (node (ref "U2") (pin "U17") (pinfunction "GND_U17") (pintype "passive"))
      (node (ref "U2") (pin "U19") (pinfunction "GND_U19") (pintype "passive"))
      (node (ref "U2") (pin "U21") (pinfunction "GND_U21") (pintype "passive"))
      (node (ref "U2") (pin "U23") (pinfunction "GND_U23") (pintype "passive"))
      (node (ref "U2") (pin "U25") (pinfunction "GND_U25") (pintype "passive"))
      (node (ref "U2") (pin "U27") (pinfunction "GND_U27") (pintype "passive"))
      (node (ref "U2") (pin "U29") (pinfunction "GND_U29") (pintype "passive"))
      (node (ref "U2") (pin "U3") (pinfunction "GND_U3") (pintype "passive"))
      (node (ref "U2") (pin "U5") (pinfunction "GND_U5") (pintype "passive"))
      (node (ref "U2") (pin "U7") (pinfunction "GND_U7") (pintype "passive"))
      (node (ref "U2") (pin "U9") (pinfunction "GND_U9") (pintype "passive"))
      (node (ref "U2") (pin "V10") (pinfunction "GND_V10") (pintype "passive"))
      (node (ref "U2") (pin "V12") (pinfunction "GND_V12") (pintype "passive"))
      (node (ref "U2") (pin "V14") (pinfunction "GND_V14") (pintype "passive"))
      (node (ref "U2") (pin "V16") (pinfunction "GND_V16") (pintype "passive"))
      (node (ref "U2") (pin "V18") (pinfunction "GND_V18") (pintype "passive"))
      (node (ref "U2") (pin "V2") (pinfunction "GND_V2") (pintype "passive"))
      (node (ref "U2") (pin "V20") (pinfunction "GND_V20") (pintype "passive"))
      (node (ref "U2") (pin "V22") (pinfunction "GND_V22") (pintype "passive"))
      (node (ref "U2") (pin "V24") (pinfunction "GND_V24") (pintype "passive"))
      (node (ref "U2") (pin "V26") (pinfunction "GND_V26") (pintype "passive"))
      (node (ref "U2") (pin "V28") (pinfunction "GND_V28") (pintype "passive"))
      (node (ref "U2") (pin "V30") (pinfunction "GND_V30") (pintype "passive"))
      (node (ref "U2") (pin "V4") (pinfunction "GND_V4") (pintype "passive"))
      (node (ref "U2") (pin "V6") (pinfunction "GND_V6") (pintype "passive"))
      (node (ref "U2") (pin "V8") (pinfunction "GND_V8") (pintype "passive"))
      (node (ref "U2") (pin "W1") (pinfunction "GND_W1") (pintype "passive"))
      (node (ref "U2") (pin "W11") (pinfunction "GND_W11") (pintype "passive"))
      (node (ref "U2") (pin "W13") (pinfunction "GND_W13") (pintype "passive"))
      (node (ref "U2") (pin "W15") (pinfunction "GND_W15") (pintype "passive"))
      (node (ref "U2") (pin "W17") (pinfunction "GND_W17") (pintype "passive"))
      (node (ref "U2") (pin "W19") (pinfunction "GND_W19") (pintype "passive"))
      (node (ref "U2") (pin "W21") (pinfunction "GND_W21") (pintype "passive"))
      (node (ref "U2") (pin "W23") (pinfunction "GND_W23") (pintype "passive"))
      (node (ref "U2") (pin "W25") (pinfunction "GND_W25") (pintype "passive"))
      (node (ref "U2") (pin "W27") (pinfunction "GND_W27") (pintype "passive"))
      (node (ref "U2") (pin "W29") (pinfunction "GND_W29") (pintype "passive"))
      (node (ref "U2") (pin "W3") (pinfunction "GND_W3") (pintype "passive"))
      (node (ref "U2") (pin "W5") (pinfunction "GND_W5") (pintype "passive"))
      (node (ref "U2") (pin "W7") (pinfunction "GND_W7") (pintype "passive"))
      (node (ref "U2") (pin "W9") (pinfunction "GND_W9") (pintype "passive"))
      (node (ref "U2") (pin "Y10") (pinfunction "GND_Y10") (pintype "passive"))
      (node (ref "U2") (pin "Y12") (pinfunction "GND_Y12") (pintype "passive"))
      (node (ref "U2") (pin "Y14") (pinfunction "GND_Y14") (pintype "passive"))
      (node (ref "U2") (pin "Y16") (pinfunction "GND_Y16") (pintype "passive"))
      (node (ref "U2") (pin "Y18") (pinfunction "GND_Y18") (pintype "passive"))
      (node (ref "U2") (pin "Y2") (pinfunction "GND_Y2") (pintype "passive"))
      (node (ref "U2") (pin "Y20") (pinfunction "GND_Y20") (pintype "passive"))
      (node (ref "U2") (pin "Y22") (pinfunction "GND_Y22") (pintype "passive"))
      (node (ref "U2") (pin "Y24") (pinfunction "GND_Y24") (pintype "passive"))
      (node (ref "U2") (pin "Y26") (pinfunction "GND_Y26") (pintype "passive"))
      (node (ref "U2") (pin "Y28") (pinfunction "GND_Y28") (pintype "passive"))
      (node (ref "U2") (pin "Y30") (pinfunction "GND_Y30") (pintype "passive"))
      (node (ref "U2") (pin "Y4") (pinfunction "GND_Y4") (pintype "passive"))
      (node (ref "U2") (pin "Y6") (pinfunction "GND_Y6") (pintype "passive"))
      (node (ref "U2") (pin "Y8") (pinfunction "GND_Y8") (pintype "passive"))
      (node (ref "U3") (pin "A1") (pinfunction "GND_A1") (pintype "passive"))
      (node (ref "U3") (pin "A11") (pinfunction "GND_A11") (pintype "passive"))
      (node (ref "U3") (pin "A13") (pinfunction "GND_A13") (pintype "passive"))
      (node (ref "U3") (pin "A15") (pinfunction "GND_A15") (pintype "passive"))
      (node (ref "U3") (pin "A17") (pinfunction "GND_A17") (pintype "passive"))
      (node (ref "U3") (pin "A19") (pinfunction "GND_A19") (pintype "passive"))
      (node (ref "U3") (pin "A21") (pinfunction "GND_A21") (pintype "passive"))
      (node (ref "U3") (pin "A23") (pinfunction "GND_A23") (pintype "passive"))
      (node (ref "U3") (pin "A25") (pinfunction "GND_A25") (pintype "passive"))
      (node (ref "U3") (pin "A27") (pinfunction "GND_A27") (pintype "passive"))
      (node (ref "U3") (pin "A29") (pinfunction "GND_A29") (pintype "passive"))
      (node (ref "U3") (pin "A3") (pinfunction "GND_A3") (pintype "passive"))
      (node (ref "U3") (pin "A5") (pinfunction "GND_A5") (pintype "passive"))
      (node (ref "U3") (pin "A7") (pinfunction "GND_A7") (pintype "passive"))
      (node (ref "U3") (pin "A9") (pinfunction "GND_A9") (pintype "passive"))
      (node (ref "U3") (pin "AA1") (pinfunction "GND_AA1") (pintype "passive"))
      (node (ref "U3") (pin "AA11") (pinfunction "GND_AA11") (pintype "passive"))
      (node (ref "U3") (pin "AA13") (pinfunction "GND_AA13") (pintype "passive"))
      (node (ref "U3") (pin "AA15") (pinfunction "GND_AA15") (pintype "passive"))
      (node (ref "U3") (pin "AA17") (pinfunction "GND_AA17") (pintype "passive"))
      (node (ref "U3") (pin "AA19") (pinfunction "GND_AA19") (pintype "passive"))
      (node (ref "U3") (pin "AA21") (pinfunction "GND_AA21") (pintype "passive"))
      (node (ref "U3") (pin "AA23") (pinfunction "GND_AA23") (pintype "passive"))
      (node (ref "U3") (pin "AA25") (pinfunction "GND_AA25") (pintype "passive"))
      (node (ref "U3") (pin "AA27") (pinfunction "GND_AA27") (pintype "passive"))
      (node (ref "U3") (pin "AA29") (pinfunction "GND_AA29") (pintype "passive"))
      (node (ref "U3") (pin "AA3") (pinfunction "GND_AA3") (pintype "passive"))
      (node (ref "U3") (pin "AA5") (pinfunction "GND_AA5") (pintype "passive"))
      (node (ref "U3") (pin "AA7") (pinfunction "GND_AA7") (pintype "passive"))
      (node (ref "U3") (pin "AA9") (pinfunction "GND_AA9") (pintype "passive"))
      (node (ref "U3") (pin "AB10") (pinfunction "GND_AB10") (pintype "passive"))
      (node (ref "U3") (pin "AB12") (pinfunction "GND_AB12") (pintype "passive"))
      (node (ref "U3") (pin "AB14") (pinfunction "GND_AB14") (pintype "passive"))
      (node (ref "U3") (pin "AB16") (pinfunction "GND_AB16") (pintype "passive"))
      (node (ref "U3") (pin "AB18") (pinfunction "GND_AB18") (pintype "passive"))
      (node (ref "U3") (pin "AB2") (pinfunction "GND_AB2") (pintype "passive"))
      (node (ref "U3") (pin "AB20") (pinfunction "GND_AB20") (pintype "passive"))
      (node (ref "U3") (pin "AB22") (pinfunction "GND_AB22") (pintype "passive"))
      (node (ref "U3") (pin "AB24") (pinfunction "GND_AB24") (pintype "passive"))
      (node (ref "U3") (pin "AB26") (pinfunction "GND_AB26") (pintype "passive"))
      (node (ref "U3") (pin "AB28") (pinfunction "GND_AB28") (pintype "passive"))
      (node (ref "U3") (pin "AB30") (pinfunction "GND_AB30") (pintype "passive"))
      (node (ref "U3") (pin "AB4") (pinfunction "GND_AB4") (pintype "passive"))
      (node (ref "U3") (pin "AB6") (pinfunction "GND_AB6") (pintype "passive"))
      (node (ref "U3") (pin "AB8") (pinfunction "GND_AB8") (pintype "passive"))
      (node (ref "U3") (pin "AC1") (pinfunction "GND_AC1") (pintype "passive"))
      (node (ref "U3") (pin "AC11") (pinfunction "GND_AC11") (pintype "passive"))
      (node (ref "U3") (pin "AC13") (pinfunction "GND_AC13") (pintype "passive"))
      (node (ref "U3") (pin "AC15") (pinfunction "GND_AC15") (pintype "passive"))
      (node (ref "U3") (pin "AC17") (pinfunction "GND_AC17") (pintype "passive"))
      (node (ref "U3") (pin "AC19") (pinfunction "GND_AC19") (pintype "passive"))
      (node (ref "U3") (pin "AC21") (pinfunction "GND_AC21") (pintype "passive"))
      (node (ref "U3") (pin "AC23") (pinfunction "GND_AC23") (pintype "passive"))
      (node (ref "U3") (pin "AC25") (pinfunction "GND_AC25") (pintype "passive"))
      (node (ref "U3") (pin "AC27") (pinfunction "GND_AC27") (pintype "passive"))
      (node (ref "U3") (pin "AC29") (pinfunction "GND_AC29") (pintype "passive"))
      (node (ref "U3") (pin "AC3") (pinfunction "GND_AC3") (pintype "passive"))
      (node (ref "U3") (pin "AC5") (pinfunction "GND_AC5") (pintype "passive"))
      (node (ref "U3") (pin "AC7") (pinfunction "GND_AC7") (pintype "passive"))
      (node (ref "U3") (pin "AC9") (pinfunction "GND_AC9") (pintype "passive"))
      (node (ref "U3") (pin "AD10") (pinfunction "GND_AD10") (pintype "passive"))
      (node (ref "U3") (pin "AD12") (pinfunction "GND_AD12") (pintype "passive"))
      (node (ref "U3") (pin "AD14") (pinfunction "GND_AD14") (pintype "passive"))
      (node (ref "U3") (pin "AD16") (pinfunction "GND_AD16") (pintype "passive"))
      (node (ref "U3") (pin "AD18") (pinfunction "GND_AD18") (pintype "passive"))
      (node (ref "U3") (pin "AD2") (pinfunction "GND_AD2") (pintype "passive"))
      (node (ref "U3") (pin "AD20") (pinfunction "GND_AD20") (pintype "passive"))
      (node (ref "U3") (pin "AD22") (pinfunction "GND_AD22") (pintype "passive"))
      (node (ref "U3") (pin "AD24") (pinfunction "GND_AD24") (pintype "passive"))
      (node (ref "U3") (pin "AD26") (pinfunction "GND_AD26") (pintype "passive"))
      (node (ref "U3") (pin "AD28") (pinfunction "GND_AD28") (pintype "passive"))
      (node (ref "U3") (pin "AD30") (pinfunction "GND_AD30") (pintype "passive"))
      (node (ref "U3") (pin "AD4") (pinfunction "GND_AD4") (pintype "passive"))
      (node (ref "U3") (pin "AD6") (pinfunction "GND_AD6") (pintype "passive"))
      (node (ref "U3") (pin "AD8") (pinfunction "GND_AD8") (pintype "passive"))
      (node (ref "U3") (pin "AE1") (pinfunction "GND_AE1") (pintype "passive"))
      (node (ref "U3") (pin "AE11") (pinfunction "GND_AE11") (pintype "passive"))
      (node (ref "U3") (pin "AE13") (pinfunction "GND_AE13") (pintype "passive"))
      (node (ref "U3") (pin "AE15") (pinfunction "GND_AE15") (pintype "passive"))
      (node (ref "U3") (pin "AE17") (pinfunction "GND_AE17") (pintype "passive"))
      (node (ref "U3") (pin "AE19") (pinfunction "GND_AE19") (pintype "passive"))
      (node (ref "U3") (pin "AE21") (pinfunction "GND_AE21") (pintype "passive"))
      (node (ref "U3") (pin "AE23") (pinfunction "GND_AE23") (pintype "passive"))
      (node (ref "U3") (pin "AE25") (pinfunction "GND_AE25") (pintype "passive"))
      (node (ref "U3") (pin "AE27") (pinfunction "GND_AE27") (pintype "passive"))
      (node (ref "U3") (pin "AE29") (pinfunction "GND_AE29") (pintype "passive"))
      (node (ref "U3") (pin "AE3") (pinfunction "GND_AE3") (pintype "passive"))
      (node (ref "U3") (pin "AE5") (pinfunction "GND_AE5") (pintype "passive"))
      (node (ref "U3") (pin "AE7") (pinfunction "GND_AE7") (pintype "passive"))
      (node (ref "U3") (pin "AE9") (pinfunction "GND_AE9") (pintype "passive"))
      (node (ref "U3") (pin "AF10") (pinfunction "GND_AF10") (pintype "passive"))
      (node (ref "U3") (pin "AF12") (pinfunction "GND_AF12") (pintype "passive"))
      (node (ref "U3") (pin "AF14") (pinfunction "GND_AF14") (pintype "passive"))
      (node (ref "U3") (pin "AF16") (pinfunction "GND_AF16") (pintype "passive"))
      (node (ref "U3") (pin "AF18") (pinfunction "GND_AF18") (pintype "passive"))
      (node (ref "U3") (pin "AF2") (pinfunction "GND_AF2") (pintype "passive"))
      (node (ref "U3") (pin "AF20") (pinfunction "GND_AF20") (pintype "passive"))
      (node (ref "U3") (pin "AF22") (pinfunction "GND_AF22") (pintype "passive"))
      (node (ref "U3") (pin "AF24") (pinfunction "GND_AF24") (pintype "passive"))
      (node (ref "U3") (pin "AF26") (pinfunction "GND_AF26") (pintype "passive"))
      (node (ref "U3") (pin "AF28") (pinfunction "GND_AF28") (pintype "passive"))
      (node (ref "U3") (pin "AF30") (pinfunction "GND_AF30") (pintype "passive"))
      (node (ref "U3") (pin "AF4") (pinfunction "GND_AF4") (pintype "passive"))
      (node (ref "U3") (pin "AF6") (pinfunction "GND_AF6") (pintype "passive"))
      (node (ref "U3") (pin "AF8") (pinfunction "GND_AF8") (pintype "passive"))
      (node (ref "U3") (pin "AG1") (pinfunction "GND_AG1") (pintype "passive"))
      (node (ref "U3") (pin "AG11") (pinfunction "GND_AG11") (pintype "passive"))
      (node (ref "U3") (pin "AG13") (pinfunction "GND_AG13") (pintype "passive"))
      (node (ref "U3") (pin "AG15") (pinfunction "GND_AG15") (pintype "passive"))
      (node (ref "U3") (pin "AG17") (pinfunction "GND_AG17") (pintype "passive"))
      (node (ref "U3") (pin "AG19") (pinfunction "GND_AG19") (pintype "passive"))
      (node (ref "U3") (pin "AG21") (pinfunction "GND_AG21") (pintype "passive"))
      (node (ref "U3") (pin "AG23") (pinfunction "GND_AG23") (pintype "passive"))
      (node (ref "U3") (pin "AG25") (pinfunction "GND_AG25") (pintype "passive"))
      (node (ref "U3") (pin "AG27") (pinfunction "GND_AG27") (pintype "passive"))
      (node (ref "U3") (pin "AG29") (pinfunction "GND_AG29") (pintype "passive"))
      (node (ref "U3") (pin "AG3") (pinfunction "GND_AG3") (pintype "passive"))
      (node (ref "U3") (pin "AG5") (pinfunction "GND_AG5") (pintype "passive"))
      (node (ref "U3") (pin "AG7") (pinfunction "GND_AG7") (pintype "passive"))
      (node (ref "U3") (pin "AG9") (pinfunction "GND_AG9") (pintype "passive"))
      (node (ref "U3") (pin "AH10") (pinfunction "GND_AH10") (pintype "passive"))
      (node (ref "U3") (pin "AH12") (pinfunction "GND_AH12") (pintype "passive"))
      (node (ref "U3") (pin "AH14") (pinfunction "GND_AH14") (pintype "passive"))
      (node (ref "U3") (pin "AH16") (pinfunction "GND_AH16") (pintype "passive"))
      (node (ref "U3") (pin "AH18") (pinfunction "GND_AH18") (pintype "passive"))
      (node (ref "U3") (pin "AH2") (pinfunction "GND_AH2") (pintype "passive"))
      (node (ref "U3") (pin "AH20") (pinfunction "GND_AH20") (pintype "passive"))
      (node (ref "U3") (pin "AH22") (pinfunction "GND_AH22") (pintype "passive"))
      (node (ref "U3") (pin "AH24") (pinfunction "GND_AH24") (pintype "passive"))
      (node (ref "U3") (pin "AH26") (pinfunction "GND_AH26") (pintype "passive"))
      (node (ref "U3") (pin "AH28") (pinfunction "GND_AH28") (pintype "passive"))
      (node (ref "U3") (pin "AH30") (pinfunction "GND_AH30") (pintype "passive"))
      (node (ref "U3") (pin "AH4") (pinfunction "GND_AH4") (pintype "passive"))
      (node (ref "U3") (pin "AH6") (pinfunction "GND_AH6") (pintype "passive"))
      (node (ref "U3") (pin "AH8") (pinfunction "GND_AH8") (pintype "passive"))
      (node (ref "U3") (pin "AJ1") (pinfunction "GND_AJ1") (pintype "passive"))
      (node (ref "U3") (pin "AJ11") (pinfunction "GND_AJ11") (pintype "passive"))
      (node (ref "U3") (pin "AJ17") (pinfunction "GND_AJ17") (pintype "passive"))
      (node (ref "U3") (pin "AJ27") (pinfunction "GND_AJ27") (pintype "passive"))
      (node (ref "U3") (pin "AJ29") (pinfunction "GND_AJ29") (pintype "passive"))
      (node (ref "U3") (pin "AJ3") (pinfunction "GND_AJ3") (pintype "passive"))
      (node (ref "U3") (pin "AJ4") (pinfunction "GND_AJ4") (pintype "passive"))
      (node (ref "U3") (pin "AJ6") (pinfunction "GND_AJ6") (pintype "passive"))
      (node (ref "U3") (pin "AJ9") (pinfunction "GND_AJ9") (pintype "passive"))
      (node (ref "U3") (pin "AK14") (pinfunction "GND_AK14") (pintype "passive"))
      (node (ref "U3") (pin "AK17") (pinfunction "GND_AK17") (pintype "passive"))
      (node (ref "U3") (pin "AK2") (pinfunction "GND_AK2") (pintype "passive"))
      (node (ref "U3") (pin "AK20") (pinfunction "GND_AK20") (pintype "passive"))
      (node (ref "U3") (pin "AK23") (pinfunction "GND_AK23") (pintype "passive"))
      (node (ref "U3") (pin "AK30") (pinfunction "GND_AK30") (pintype "passive"))
      (node (ref "U3") (pin "B10") (pinfunction "GND_B10") (pintype "passive"))
      (node (ref "U3") (pin "B12") (pinfunction "GND_B12") (pintype "passive"))
      (node (ref "U3") (pin "B14") (pinfunction "GND_B14") (pintype "passive"))
      (node (ref "U3") (pin "B16") (pinfunction "GND_B16") (pintype "passive"))
      (node (ref "U3") (pin "B18") (pinfunction "GND_B18") (pintype "passive"))
      (node (ref "U3") (pin "B2") (pinfunction "GND_B2") (pintype "passive"))
      (node (ref "U3") (pin "B20") (pinfunction "GND_B20") (pintype "passive"))
      (node (ref "U3") (pin "B22") (pinfunction "GND_B22") (pintype "passive"))
      (node (ref "U3") (pin "B24") (pinfunction "GND_B24") (pintype "passive"))
      (node (ref "U3") (pin "B26") (pinfunction "GND_B26") (pintype "passive"))
      (node (ref "U3") (pin "B28") (pinfunction "GND_B28") (pintype "passive"))
      (node (ref "U3") (pin "B30") (pinfunction "GND_B30") (pintype "passive"))
      (node (ref "U3") (pin "B4") (pinfunction "GND_B4") (pintype "passive"))
      (node (ref "U3") (pin "B6") (pinfunction "GND_B6") (pintype "passive"))
      (node (ref "U3") (pin "B8") (pinfunction "GND_B8") (pintype "passive"))
      (node (ref "U3") (pin "C1") (pinfunction "GND_C1") (pintype "passive"))
      (node (ref "U3") (pin "C11") (pinfunction "GND_C11") (pintype "passive"))
      (node (ref "U3") (pin "C13") (pinfunction "GND_C13") (pintype "passive"))
      (node (ref "U3") (pin "C15") (pinfunction "GND_C15") (pintype "passive"))
      (node (ref "U3") (pin "C17") (pinfunction "GND_C17") (pintype "passive"))
      (node (ref "U3") (pin "C19") (pinfunction "GND_C19") (pintype "passive"))
      (node (ref "U3") (pin "C21") (pinfunction "GND_C21") (pintype "passive"))
      (node (ref "U3") (pin "C23") (pinfunction "GND_C23") (pintype "passive"))
      (node (ref "U3") (pin "C25") (pinfunction "GND_C25") (pintype "passive"))
      (node (ref "U3") (pin "C27") (pinfunction "GND_C27") (pintype "passive"))
      (node (ref "U3") (pin "C29") (pinfunction "GND_C29") (pintype "passive"))
      (node (ref "U3") (pin "C3") (pinfunction "GND_C3") (pintype "passive"))
      (node (ref "U3") (pin "C5") (pinfunction "GND_C5") (pintype "passive"))
      (node (ref "U3") (pin "C7") (pinfunction "GND_C7") (pintype "passive"))
      (node (ref "U3") (pin "C9") (pinfunction "GND_C9") (pintype "passive"))
      (node (ref "U3") (pin "D10") (pinfunction "GND_D10") (pintype "passive"))
      (node (ref "U3") (pin "D12") (pinfunction "GND_D12") (pintype "passive"))
      (node (ref "U3") (pin "D14") (pinfunction "GND_D14") (pintype "passive"))
      (node (ref "U3") (pin "D16") (pinfunction "GND_D16") (pintype "passive"))
      (node (ref "U3") (pin "D18") (pinfunction "GND_D18") (pintype "passive"))
      (node (ref "U3") (pin "D2") (pinfunction "GND_D2") (pintype "passive"))
      (node (ref "U3") (pin "D20") (pinfunction "GND_D20") (pintype "passive"))
      (node (ref "U3") (pin "D22") (pinfunction "GND_D22") (pintype "passive"))
      (node (ref "U3") (pin "D24") (pinfunction "GND_D24") (pintype "passive"))
      (node (ref "U3") (pin "D26") (pinfunction "GND_D26") (pintype "passive"))
      (node (ref "U3") (pin "D28") (pinfunction "GND_D28") (pintype "passive"))
      (node (ref "U3") (pin "D30") (pinfunction "GND_D30") (pintype "passive"))
      (node (ref "U3") (pin "D4") (pinfunction "GND_D4") (pintype "passive"))
      (node (ref "U3") (pin "D6") (pinfunction "GND_D6") (pintype "passive"))
      (node (ref "U3") (pin "D8") (pinfunction "GND_D8") (pintype "passive"))
      (node (ref "U3") (pin "E1") (pinfunction "GND_E1") (pintype "passive"))
      (node (ref "U3") (pin "E11") (pinfunction "GND_E11") (pintype "passive"))
      (node (ref "U3") (pin "E13") (pinfunction "GND_E13") (pintype "passive"))
      (node (ref "U3") (pin "E15") (pinfunction "GND_E15") (pintype "passive"))
      (node (ref "U3") (pin "E17") (pinfunction "GND_E17") (pintype "passive"))
      (node (ref "U3") (pin "E19") (pinfunction "GND_E19") (pintype "passive"))
      (node (ref "U3") (pin "E21") (pinfunction "GND_E21") (pintype "passive"))
      (node (ref "U3") (pin "E23") (pinfunction "GND_E23") (pintype "passive"))
      (node (ref "U3") (pin "E25") (pinfunction "GND_E25") (pintype "passive"))
      (node (ref "U3") (pin "E27") (pinfunction "GND_E27") (pintype "passive"))
      (node (ref "U3") (pin "E29") (pinfunction "GND_E29") (pintype "passive"))
      (node (ref "U3") (pin "E3") (pinfunction "GND_E3") (pintype "passive"))
      (node (ref "U3") (pin "E5") (pinfunction "GND_E5") (pintype "passive"))
      (node (ref "U3") (pin "E7") (pinfunction "GND_E7") (pintype "passive"))
      (node (ref "U3") (pin "E9") (pinfunction "GND_E9") (pintype "passive"))
      (node (ref "U3") (pin "F10") (pinfunction "GND_F10") (pintype "passive"))
      (node (ref "U3") (pin "F12") (pinfunction "GND_F12") (pintype "passive"))
      (node (ref "U3") (pin "F14") (pinfunction "GND_F14") (pintype "passive"))
      (node (ref "U3") (pin "F16") (pinfunction "GND_F16") (pintype "passive"))
      (node (ref "U3") (pin "F18") (pinfunction "GND_F18") (pintype "passive"))
      (node (ref "U3") (pin "F2") (pinfunction "GND_F2") (pintype "passive"))
      (node (ref "U3") (pin "F20") (pinfunction "GND_F20") (pintype "passive"))
      (node (ref "U3") (pin "F22") (pinfunction "GND_F22") (pintype "passive"))
      (node (ref "U3") (pin "F24") (pinfunction "GND_F24") (pintype "passive"))
      (node (ref "U3") (pin "F26") (pinfunction "GND_F26") (pintype "passive"))
      (node (ref "U3") (pin "F28") (pinfunction "GND_F28") (pintype "passive"))
      (node (ref "U3") (pin "F30") (pinfunction "GND_F30") (pintype "passive"))
      (node (ref "U3") (pin "F4") (pinfunction "GND_F4") (pintype "passive"))
      (node (ref "U3") (pin "F6") (pinfunction "GND_F6") (pintype "passive"))
      (node (ref "U3") (pin "F8") (pinfunction "GND_F8") (pintype "passive"))
      (node (ref "U3") (pin "G1") (pinfunction "GND_G1") (pintype "passive"))
      (node (ref "U3") (pin "G11") (pinfunction "GND_G11") (pintype "passive"))
      (node (ref "U3") (pin "G13") (pinfunction "GND_G13") (pintype "passive"))
      (node (ref "U3") (pin "G15") (pinfunction "GND_G15") (pintype "passive"))
      (node (ref "U3") (pin "G17") (pinfunction "GND_G17") (pintype "passive"))
      (node (ref "U3") (pin "G19") (pinfunction "GND_G19") (pintype "passive"))
      (node (ref "U3") (pin "G21") (pinfunction "GND_G21") (pintype "passive"))
      (node (ref "U3") (pin "G23") (pinfunction "GND_G23") (pintype "passive"))
      (node (ref "U3") (pin "G25") (pinfunction "GND_G25") (pintype "passive"))
      (node (ref "U3") (pin "G27") (pinfunction "GND_G27") (pintype "passive"))
      (node (ref "U3") (pin "G29") (pinfunction "GND_G29") (pintype "passive"))
      (node (ref "U3") (pin "G3") (pinfunction "GND_G3") (pintype "passive"))
      (node (ref "U3") (pin "G5") (pinfunction "GND_G5") (pintype "passive"))
      (node (ref "U3") (pin "G7") (pinfunction "GND_G7") (pintype "passive"))
      (node (ref "U3") (pin "G9") (pinfunction "GND_G9") (pintype "passive"))
      (node (ref "U3") (pin "H10") (pinfunction "GND_H10") (pintype "passive"))
      (node (ref "U3") (pin "H12") (pinfunction "GND_H12") (pintype "passive"))
      (node (ref "U3") (pin "H14") (pinfunction "GND_H14") (pintype "passive"))
      (node (ref "U3") (pin "H16") (pinfunction "GND_H16") (pintype "passive"))
      (node (ref "U3") (pin "H18") (pinfunction "GND_H18") (pintype "passive"))
      (node (ref "U3") (pin "H2") (pinfunction "GND_H2") (pintype "passive"))
      (node (ref "U3") (pin "H20") (pinfunction "GND_H20") (pintype "passive"))
      (node (ref "U3") (pin "H22") (pinfunction "GND_H22") (pintype "passive"))
      (node (ref "U3") (pin "H24") (pinfunction "GND_H24") (pintype "passive"))
      (node (ref "U3") (pin "H26") (pinfunction "GND_H26") (pintype "passive"))
      (node (ref "U3") (pin "H28") (pinfunction "GND_H28") (pintype "passive"))
      (node (ref "U3") (pin "H30") (pinfunction "GND_H30") (pintype "passive"))
      (node (ref "U3") (pin "H4") (pinfunction "GND_H4") (pintype "passive"))
      (node (ref "U3") (pin "H6") (pinfunction "GND_H6") (pintype "passive"))
      (node (ref "U3") (pin "H8") (pinfunction "GND_H8") (pintype "passive"))
      (node (ref "U3") (pin "J1") (pinfunction "GND_J1") (pintype "passive"))
      (node (ref "U3") (pin "J11") (pinfunction "GND_J11") (pintype "passive"))
      (node (ref "U3") (pin "J13") (pinfunction "GND_J13") (pintype "passive"))
      (node (ref "U3") (pin "J15") (pinfunction "GND_J15") (pintype "passive"))
      (node (ref "U3") (pin "J17") (pinfunction "GND_J17") (pintype "passive"))
      (node (ref "U3") (pin "J19") (pinfunction "GND_J19") (pintype "passive"))
      (node (ref "U3") (pin "J21") (pinfunction "GND_J21") (pintype "passive"))
      (node (ref "U3") (pin "J23") (pinfunction "GND_J23") (pintype "passive"))
      (node (ref "U3") (pin "J25") (pinfunction "GND_J25") (pintype "passive"))
      (node (ref "U3") (pin "J27") (pinfunction "GND_J27") (pintype "passive"))
      (node (ref "U3") (pin "J29") (pinfunction "GND_J29") (pintype "passive"))
      (node (ref "U3") (pin "J3") (pinfunction "GND_J3") (pintype "passive"))
      (node (ref "U3") (pin "J5") (pinfunction "GND_J5") (pintype "passive"))
      (node (ref "U3") (pin "J7") (pinfunction "GND_J7") (pintype "passive"))
      (node (ref "U3") (pin "J9") (pinfunction "GND_J9") (pintype "passive"))
      (node (ref "U3") (pin "K10") (pinfunction "GND_K10") (pintype "passive"))
      (node (ref "U3") (pin "K12") (pinfunction "GND_K12") (pintype "passive"))
      (node (ref "U3") (pin "K14") (pinfunction "GND_K14") (pintype "passive"))
      (node (ref "U3") (pin "K16") (pinfunction "GND_K16") (pintype "passive"))
      (node (ref "U3") (pin "K18") (pinfunction "GND_K18") (pintype "passive"))
      (node (ref "U3") (pin "K2") (pinfunction "GND_K2") (pintype "passive"))
      (node (ref "U3") (pin "K20") (pinfunction "GND_K20") (pintype "passive"))
      (node (ref "U3") (pin "K22") (pinfunction "GND_K22") (pintype "passive"))
      (node (ref "U3") (pin "K24") (pinfunction "GND_K24") (pintype "passive"))
      (node (ref "U3") (pin "K26") (pinfunction "GND_K26") (pintype "passive"))
      (node (ref "U3") (pin "K28") (pinfunction "GND_K28") (pintype "passive"))
      (node (ref "U3") (pin "K30") (pinfunction "GND_K30") (pintype "passive"))
      (node (ref "U3") (pin "K4") (pinfunction "GND_K4") (pintype "passive"))
      (node (ref "U3") (pin "K6") (pinfunction "GND_K6") (pintype "passive"))
      (node (ref "U3") (pin "K8") (pinfunction "GND_K8") (pintype "passive"))
      (node (ref "U3") (pin "L1") (pinfunction "GND_L1") (pintype "passive"))
      (node (ref "U3") (pin "L11") (pinfunction "GND_L11") (pintype "passive"))
      (node (ref "U3") (pin "L13") (pinfunction "GND_L13") (pintype "passive"))
      (node (ref "U3") (pin "L15") (pinfunction "GND_L15") (pintype "passive"))
      (node (ref "U3") (pin "L17") (pinfunction "GND_L17") (pintype "passive"))
      (node (ref "U3") (pin "L19") (pinfunction "GND_L19") (pintype "passive"))
      (node (ref "U3") (pin "L21") (pinfunction "GND_L21") (pintype "passive"))
      (node (ref "U3") (pin "L23") (pinfunction "GND_L23") (pintype "passive"))
      (node (ref "U3") (pin "L25") (pinfunction "GND_L25") (pintype "passive"))
      (node (ref "U3") (pin "L27") (pinfunction "GND_L27") (pintype "passive"))
      (node (ref "U3") (pin "L29") (pinfunction "GND_L29") (pintype "passive"))
      (node (ref "U3") (pin "L3") (pinfunction "GND_L3") (pintype "passive"))
      (node (ref "U3") (pin "L5") (pinfunction "GND_L5") (pintype "passive"))
      (node (ref "U3") (pin "L7") (pinfunction "GND_L7") (pintype "passive"))
      (node (ref "U3") (pin "L9") (pinfunction "GND_L9") (pintype "passive"))
      (node (ref "U3") (pin "M10") (pinfunction "GND_M10") (pintype "passive"))
      (node (ref "U3") (pin "M12") (pinfunction "GND_M12") (pintype "passive"))
      (node (ref "U3") (pin "M14") (pinfunction "GND_M14") (pintype "passive"))
      (node (ref "U3") (pin "M16") (pinfunction "GND_M16") (pintype "passive"))
      (node (ref "U3") (pin "M18") (pinfunction "GND_M18") (pintype "passive"))
      (node (ref "U3") (pin "M2") (pinfunction "GND_M2") (pintype "passive"))
      (node (ref "U3") (pin "M20") (pinfunction "GND_M20") (pintype "passive"))
      (node (ref "U3") (pin "M22") (pinfunction "GND_M22") (pintype "passive"))
      (node (ref "U3") (pin "M24") (pinfunction "GND_M24") (pintype "passive"))
      (node (ref "U3") (pin "M26") (pinfunction "GND_M26") (pintype "passive"))
      (node (ref "U3") (pin "M28") (pinfunction "GND_M28") (pintype "passive"))
      (node (ref "U3") (pin "M30") (pinfunction "GND_M30") (pintype "passive"))
      (node (ref "U3") (pin "M4") (pinfunction "GND_M4") (pintype "passive"))
      (node (ref "U3") (pin "M6") (pinfunction "GND_M6") (pintype "passive"))
      (node (ref "U3") (pin "M8") (pinfunction "GND_M8") (pintype "passive"))
      (node (ref "U3") (pin "N1") (pinfunction "GND_N1") (pintype "passive"))
      (node (ref "U3") (pin "N11") (pinfunction "GND_N11") (pintype "passive"))
      (node (ref "U3") (pin "N13") (pinfunction "GND_N13") (pintype "passive"))
      (node (ref "U3") (pin "N15") (pinfunction "GND_N15") (pintype "passive"))
      (node (ref "U3") (pin "N17") (pinfunction "GND_N17") (pintype "passive"))
      (node (ref "U3") (pin "N19") (pinfunction "GND_N19") (pintype "passive"))
      (node (ref "U3") (pin "N21") (pinfunction "GND_N21") (pintype "passive"))
      (node (ref "U3") (pin "N23") (pinfunction "GND_N23") (pintype "passive"))
      (node (ref "U3") (pin "N25") (pinfunction "GND_N25") (pintype "passive"))
      (node (ref "U3") (pin "N27") (pinfunction "GND_N27") (pintype "passive"))
      (node (ref "U3") (pin "N29") (pinfunction "GND_N29") (pintype "passive"))
      (node (ref "U3") (pin "N3") (pinfunction "GND_N3") (pintype "passive"))
      (node (ref "U3") (pin "N5") (pinfunction "GND_N5") (pintype "passive"))
      (node (ref "U3") (pin "N7") (pinfunction "GND_N7") (pintype "passive"))
      (node (ref "U3") (pin "N9") (pinfunction "GND_N9") (pintype "passive"))
      (node (ref "U3") (pin "P10") (pinfunction "GND_P10") (pintype "passive"))
      (node (ref "U3") (pin "P12") (pinfunction "GND_P12") (pintype "passive"))
      (node (ref "U3") (pin "P14") (pinfunction "GND_P14") (pintype "passive"))
      (node (ref "U3") (pin "P16") (pinfunction "GND_P16") (pintype "passive"))
      (node (ref "U3") (pin "P18") (pinfunction "GND_P18") (pintype "passive"))
      (node (ref "U3") (pin "P2") (pinfunction "GND_P2") (pintype "passive"))
      (node (ref "U3") (pin "P20") (pinfunction "GND_P20") (pintype "passive"))
      (node (ref "U3") (pin "P22") (pinfunction "GND_P22") (pintype "passive"))
      (node (ref "U3") (pin "P24") (pinfunction "GND_P24") (pintype "passive"))
      (node (ref "U3") (pin "P26") (pinfunction "GND_P26") (pintype "passive"))
      (node (ref "U3") (pin "P28") (pinfunction "GND_P28") (pintype "passive"))
      (node (ref "U3") (pin "P30") (pinfunction "GND_P30") (pintype "passive"))
      (node (ref "U3") (pin "P4") (pinfunction "GND_P4") (pintype "passive"))
      (node (ref "U3") (pin "P6") (pinfunction "GND_P6") (pintype "passive"))
      (node (ref "U3") (pin "P8") (pinfunction "GND_P8") (pintype "passive"))
      (node (ref "U3") (pin "R1") (pinfunction "GND_R1") (pintype "passive"))
      (node (ref "U3") (pin "R11") (pinfunction "GND_R11") (pintype "passive"))
      (node (ref "U3") (pin "R13") (pinfunction "GND_R13") (pintype "passive"))
      (node (ref "U3") (pin "R15") (pinfunction "GND_R15") (pintype "passive"))
      (node (ref "U3") (pin "R17") (pinfunction "GND_R17") (pintype "passive"))
      (node (ref "U3") (pin "R19") (pinfunction "GND_R19") (pintype "passive"))
      (node (ref "U3") (pin "R21") (pinfunction "GND_R21") (pintype "passive"))
      (node (ref "U3") (pin "R23") (pinfunction "GND_R23") (pintype "passive"))
      (node (ref "U3") (pin "R25") (pinfunction "GND_R25") (pintype "passive"))
      (node (ref "U3") (pin "R27") (pinfunction "GND_R27") (pintype "passive"))
      (node (ref "U3") (pin "R29") (pinfunction "GND_R29") (pintype "passive"))
      (node (ref "U3") (pin "R3") (pinfunction "GND_R3") (pintype "passive"))
      (node (ref "U3") (pin "R5") (pinfunction "GND_R5") (pintype "passive"))
      (node (ref "U3") (pin "R7") (pinfunction "GND_R7") (pintype "passive"))
      (node (ref "U3") (pin "R9") (pinfunction "GND_R9") (pintype "passive"))
      (node (ref "U3") (pin "T10") (pinfunction "GND_T10") (pintype "passive"))
      (node (ref "U3") (pin "T12") (pinfunction "GND_T12") (pintype "passive"))
      (node (ref "U3") (pin "T14") (pinfunction "GND_T14") (pintype "passive"))
      (node (ref "U3") (pin "T16") (pinfunction "GND_T16") (pintype "passive"))
      (node (ref "U3") (pin "T18") (pinfunction "GND_T18") (pintype "passive"))
      (node (ref "U3") (pin "T2") (pinfunction "GND_T2") (pintype "passive"))
      (node (ref "U3") (pin "T20") (pinfunction "GND_T20") (pintype "passive"))
      (node (ref "U3") (pin "T22") (pinfunction "GND_T22") (pintype "passive"))
      (node (ref "U3") (pin "T24") (pinfunction "GND_T24") (pintype "passive"))
      (node (ref "U3") (pin "T26") (pinfunction "GND_T26") (pintype "passive"))
      (node (ref "U3") (pin "T28") (pinfunction "GND_T28") (pintype "passive"))
      (node (ref "U3") (pin "T30") (pinfunction "GND_T30") (pintype "passive"))
      (node (ref "U3") (pin "T4") (pinfunction "GND_T4") (pintype "passive"))
      (node (ref "U3") (pin "T6") (pinfunction "GND_T6") (pintype "passive"))
      (node (ref "U3") (pin "T8") (pinfunction "GND_T8") (pintype "passive"))
      (node (ref "U3") (pin "U1") (pinfunction "GND_U1") (pintype "passive"))
      (node (ref "U3") (pin "U11") (pinfunction "GND_U11") (pintype "passive"))
      (node (ref "U3") (pin "U13") (pinfunction "GND_U13") (pintype "passive"))
      (node (ref "U3") (pin "U15") (pinfunction "GND_U15") (pintype "passive"))
      (node (ref "U3") (pin "U17") (pinfunction "GND_U17") (pintype "passive"))
      (node (ref "U3") (pin "U19") (pinfunction "GND_U19") (pintype "passive"))
      (node (ref "U3") (pin "U21") (pinfunction "GND_U21") (pintype "passive"))
      (node (ref "U3") (pin "U23") (pinfunction "GND_U23") (pintype "passive"))
      (node (ref "U3") (pin "U25") (pinfunction "GND_U25") (pintype "passive"))
      (node (ref "U3") (pin "U27") (pinfunction "GND_U27") (pintype "passive"))
      (node (ref "U3") (pin "U29") (pinfunction "GND_U29") (pintype "passive"))
      (node (ref "U3") (pin "U3") (pinfunction "GND_U3") (pintype "passive"))
      (node (ref "U3") (pin "U5") (pinfunction "GND_U5") (pintype "passive"))
      (node (ref "U3") (pin "U7") (pinfunction "GND_U7") (pintype "passive"))
      (node (ref "U3") (pin "U9") (pinfunction "GND_U9") (pintype "passive"))
      (node (ref "U3") (pin "V10") (pinfunction "GND_V10") (pintype "passive"))
      (node (ref "U3") (pin "V12") (pinfunction "GND_V12") (pintype "passive"))
      (node (ref "U3") (pin "V14") (pinfunction "GND_V14") (pintype "passive"))
      (node (ref "U3") (pin "V16") (pinfunction "GND_V16") (pintype "passive"))
      (node (ref "U3") (pin "V18") (pinfunction "GND_V18") (pintype "passive"))
      (node (ref "U3") (pin "V2") (pinfunction "GND_V2") (pintype "passive"))
      (node (ref "U3") (pin "V20") (pinfunction "GND_V20") (pintype "passive"))
      (node (ref "U3") (pin "V22") (pinfunction "GND_V22") (pintype "passive"))
      (node (ref "U3") (pin "V24") (pinfunction "GND_V24") (pintype "passive"))
      (node (ref "U3") (pin "V26") (pinfunction "GND_V26") (pintype "passive"))
      (node (ref "U3") (pin "V28") (pinfunction "GND_V28") (pintype "passive"))
      (node (ref "U3") (pin "V30") (pinfunction "GND_V30") (pintype "passive"))
      (node (ref "U3") (pin "V4") (pinfunction "GND_V4") (pintype "passive"))
      (node (ref "U3") (pin "V6") (pinfunction "GND_V6") (pintype "passive"))
      (node (ref "U3") (pin "V8") (pinfunction "GND_V8") (pintype "passive"))
      (node (ref "U3") (pin "W1") (pinfunction "GND_W1") (pintype "passive"))
      (node (ref "U3") (pin "W11") (pinfunction "GND_W11") (pintype "passive"))
      (node (ref "U3") (pin "W13") (pinfunction "GND_W13") (pintype "passive"))
      (node (ref "U3") (pin "W15") (pinfunction "GND_W15") (pintype "passive"))
      (node (ref "U3") (pin "W17") (pinfunction "GND_W17") (pintype "passive"))
      (node (ref "U3") (pin "W19") (pinfunction "GND_W19") (pintype "passive"))
      (node (ref "U3") (pin "W21") (pinfunction "GND_W21") (pintype "passive"))
      (node (ref "U3") (pin "W23") (pinfunction "GND_W23") (pintype "passive"))
      (node (ref "U3") (pin "W25") (pinfunction "GND_W25") (pintype "passive"))
      (node (ref "U3") (pin "W27") (pinfunction "GND_W27") (pintype "passive"))
      (node (ref "U3") (pin "W29") (pinfunction "GND_W29") (pintype "passive"))
      (node (ref "U3") (pin "W3") (pinfunction "GND_W3") (pintype "passive"))
      (node (ref "U3") (pin "W5") (pinfunction "GND_W5") (pintype "passive"))
      (node (ref "U3") (pin "W7") (pinfunction "GND_W7") (pintype "passive"))
      (node (ref "U3") (pin "W9") (pinfunction "GND_W9") (pintype "passive"))
      (node (ref "U3") (pin "Y10") (pinfunction "GND_Y10") (pintype "passive"))
      (node (ref "U3") (pin "Y12") (pinfunction "GND_Y12") (pintype "passive"))
      (node (ref "U3") (pin "Y14") (pinfunction "GND_Y14") (pintype "passive"))
      (node (ref "U3") (pin "Y16") (pinfunction "GND_Y16") (pintype "passive"))
      (node (ref "U3") (pin "Y18") (pinfunction "GND_Y18") (pintype "passive"))
      (node (ref "U3") (pin "Y2") (pinfunction "GND_Y2") (pintype "passive"))
      (node (ref "U3") (pin "Y20") (pinfunction "GND_Y20") (pintype "passive"))
      (node (ref "U3") (pin "Y22") (pinfunction "GND_Y22") (pintype "passive"))
      (node (ref "U3") (pin "Y24") (pinfunction "GND_Y24") (pintype "passive"))
      (node (ref "U3") (pin "Y26") (pinfunction "GND_Y26") (pintype "passive"))
      (node (ref "U3") (pin "Y28") (pinfunction "GND_Y28") (pintype "passive"))
      (node (ref "U3") (pin "Y30") (pinfunction "GND_Y30") (pintype "passive"))
      (node (ref "U3") (pin "Y4") (pinfunction "GND_Y4") (pintype "passive"))
      (node (ref "U3") (pin "Y6") (pinfunction "GND_Y6") (pintype "passive"))
      (node (ref "U3") (pin "Y8") (pinfunction "GND_Y8") (pintype "passive"))
      (node (ref "U4") (pin "A1") (pinfunction "GND_A1") (pintype "passive"))
      (node (ref "U4") (pin "A11") (pinfunction "GND_A11") (pintype "passive"))
      (node (ref "U4") (pin "A13") (pinfunction "GND_A13") (pintype "passive"))
      (node (ref "U4") (pin "A15") (pinfunction "GND_A15") (pintype "passive"))
      (node (ref "U4") (pin "A17") (pinfunction "GND_A17") (pintype "passive"))
      (node (ref "U4") (pin "A19") (pinfunction "GND_A19") (pintype "passive"))
      (node (ref "U4") (pin "A21") (pinfunction "GND_A21") (pintype "passive"))
      (node (ref "U4") (pin "A23") (pinfunction "GND_A23") (pintype "passive"))
      (node (ref "U4") (pin "A25") (pinfunction "GND_A25") (pintype "passive"))
      (node (ref "U4") (pin "A27") (pinfunction "GND_A27") (pintype "passive"))
      (node (ref "U4") (pin "A29") (pinfunction "GND_A29") (pintype "passive"))
      (node (ref "U4") (pin "A3") (pinfunction "GND_A3") (pintype "passive"))
      (node (ref "U4") (pin "A5") (pinfunction "GND_A5") (pintype "passive"))
      (node (ref "U4") (pin "A7") (pinfunction "GND_A7") (pintype "passive"))
      (node (ref "U4") (pin "A9") (pinfunction "GND_A9") (pintype "passive"))
      (node (ref "U4") (pin "AA1") (pinfunction "GND_AA1") (pintype "passive"))
      (node (ref "U4") (pin "AA11") (pinfunction "GND_AA11") (pintype "passive"))
      (node (ref "U4") (pin "AA13") (pinfunction "GND_AA13") (pintype "passive"))
      (node (ref "U4") (pin "AA15") (pinfunction "GND_AA15") (pintype "passive"))
      (node (ref "U4") (pin "AA17") (pinfunction "GND_AA17") (pintype "passive"))
      (node (ref "U4") (pin "AA19") (pinfunction "GND_AA19") (pintype "passive"))
      (node (ref "U4") (pin "AA21") (pinfunction "GND_AA21") (pintype "passive"))
      (node (ref "U4") (pin "AA23") (pinfunction "GND_AA23") (pintype "passive"))
      (node (ref "U4") (pin "AA25") (pinfunction "GND_AA25") (pintype "passive"))
      (node (ref "U4") (pin "AA27") (pinfunction "GND_AA27") (pintype "passive"))
      (node (ref "U4") (pin "AA29") (pinfunction "GND_AA29") (pintype "passive"))
      (node (ref "U4") (pin "AA3") (pinfunction "GND_AA3") (pintype "passive"))
      (node (ref "U4") (pin "AA5") (pinfunction "GND_AA5") (pintype "passive"))
      (node (ref "U4") (pin "AA7") (pinfunction "GND_AA7") (pintype "passive"))
      (node (ref "U4") (pin "AA9") (pinfunction "GND_AA9") (pintype "passive"))
      (node (ref "U4") (pin "AB10") (pinfunction "GND_AB10") (pintype "passive"))
      (node (ref "U4") (pin "AB12") (pinfunction "GND_AB12") (pintype "passive"))
      (node (ref "U4") (pin "AB14") (pinfunction "GND_AB14") (pintype "passive"))
      (node (ref "U4") (pin "AB16") (pinfunction "GND_AB16") (pintype "passive"))
      (node (ref "U4") (pin "AB18") (pinfunction "GND_AB18") (pintype "passive"))
      (node (ref "U4") (pin "AB2") (pinfunction "GND_AB2") (pintype "passive"))
      (node (ref "U4") (pin "AB20") (pinfunction "GND_AB20") (pintype "passive"))
      (node (ref "U4") (pin "AB22") (pinfunction "GND_AB22") (pintype "passive"))
      (node (ref "U4") (pin "AB24") (pinfunction "GND_AB24") (pintype "passive"))
      (node (ref "U4") (pin "AB26") (pinfunction "GND_AB26") (pintype "passive"))
      (node (ref "U4") (pin "AB28") (pinfunction "GND_AB28") (pintype "passive"))
      (node (ref "U4") (pin "AB30") (pinfunction "GND_AB30") (pintype "passive"))
      (node (ref "U4") (pin "AB4") (pinfunction "GND_AB4") (pintype "passive"))
      (node (ref "U4") (pin "AB6") (pinfunction "GND_AB6") (pintype "passive"))
      (node (ref "U4") (pin "AB8") (pinfunction "GND_AB8") (pintype "passive"))
      (node (ref "U4") (pin "AC1") (pinfunction "GND_AC1") (pintype "passive"))
      (node (ref "U4") (pin "AC11") (pinfunction "GND_AC11") (pintype "passive"))
      (node (ref "U4") (pin "AC13") (pinfunction "GND_AC13") (pintype "passive"))
      (node (ref "U4") (pin "AC15") (pinfunction "GND_AC15") (pintype "passive"))
      (node (ref "U4") (pin "AC17") (pinfunction "GND_AC17") (pintype "passive"))
      (node (ref "U4") (pin "AC19") (pinfunction "GND_AC19") (pintype "passive"))
      (node (ref "U4") (pin "AC21") (pinfunction "GND_AC21") (pintype "passive"))
      (node (ref "U4") (pin "AC23") (pinfunction "GND_AC23") (pintype "passive"))
      (node (ref "U4") (pin "AC25") (pinfunction "GND_AC25") (pintype "passive"))
      (node (ref "U4") (pin "AC27") (pinfunction "GND_AC27") (pintype "passive"))
      (node (ref "U4") (pin "AC29") (pinfunction "GND_AC29") (pintype "passive"))
      (node (ref "U4") (pin "AC3") (pinfunction "GND_AC3") (pintype "passive"))
      (node (ref "U4") (pin "AC5") (pinfunction "GND_AC5") (pintype "passive"))
      (node (ref "U4") (pin "AC7") (pinfunction "GND_AC7") (pintype "passive"))
      (node (ref "U4") (pin "AC9") (pinfunction "GND_AC9") (pintype "passive"))
      (node (ref "U4") (pin "AD10") (pinfunction "GND_AD10") (pintype "passive"))
      (node (ref "U4") (pin "AD12") (pinfunction "GND_AD12") (pintype "passive"))
      (node (ref "U4") (pin "AD14") (pinfunction "GND_AD14") (pintype "passive"))
      (node (ref "U4") (pin "AD16") (pinfunction "GND_AD16") (pintype "passive"))
      (node (ref "U4") (pin "AD18") (pinfunction "GND_AD18") (pintype "passive"))
      (node (ref "U4") (pin "AD2") (pinfunction "GND_AD2") (pintype "passive"))
      (node (ref "U4") (pin "AD20") (pinfunction "GND_AD20") (pintype "passive"))
      (node (ref "U4") (pin "AD22") (pinfunction "GND_AD22") (pintype "passive"))
      (node (ref "U4") (pin "AD24") (pinfunction "GND_AD24") (pintype "passive"))
      (node (ref "U4") (pin "AD26") (pinfunction "GND_AD26") (pintype "passive"))
      (node (ref "U4") (pin "AD28") (pinfunction "GND_AD28") (pintype "passive"))
      (node (ref "U4") (pin "AD30") (pinfunction "GND_AD30") (pintype "passive"))
      (node (ref "U4") (pin "AD4") (pinfunction "GND_AD4") (pintype "passive"))
      (node (ref "U4") (pin "AD6") (pinfunction "GND_AD6") (pintype "passive"))
      (node (ref "U4") (pin "AD8") (pinfunction "GND_AD8") (pintype "passive"))
      (node (ref "U4") (pin "AE1") (pinfunction "GND_AE1") (pintype "passive"))
      (node (ref "U4") (pin "AE11") (pinfunction "GND_AE11") (pintype "passive"))
      (node (ref "U4") (pin "AE13") (pinfunction "GND_AE13") (pintype "passive"))
      (node (ref "U4") (pin "AE15") (pinfunction "GND_AE15") (pintype "passive"))
      (node (ref "U4") (pin "AE17") (pinfunction "GND_AE17") (pintype "passive"))
      (node (ref "U4") (pin "AE19") (pinfunction "GND_AE19") (pintype "passive"))
      (node (ref "U4") (pin "AE21") (pinfunction "GND_AE21") (pintype "passive"))
      (node (ref "U4") (pin "AE23") (pinfunction "GND_AE23") (pintype "passive"))
      (node (ref "U4") (pin "AE25") (pinfunction "GND_AE25") (pintype "passive"))
      (node (ref "U4") (pin "AE27") (pinfunction "GND_AE27") (pintype "passive"))
      (node (ref "U4") (pin "AE29") (pinfunction "GND_AE29") (pintype "passive"))
      (node (ref "U4") (pin "AE3") (pinfunction "GND_AE3") (pintype "passive"))
      (node (ref "U4") (pin "AE5") (pinfunction "GND_AE5") (pintype "passive"))
      (node (ref "U4") (pin "AE7") (pinfunction "GND_AE7") (pintype "passive"))
      (node (ref "U4") (pin "AE9") (pinfunction "GND_AE9") (pintype "passive"))
      (node (ref "U4") (pin "AF10") (pinfunction "GND_AF10") (pintype "passive"))
      (node (ref "U4") (pin "AF12") (pinfunction "GND_AF12") (pintype "passive"))
      (node (ref "U4") (pin "AF14") (pinfunction "GND_AF14") (pintype "passive"))
      (node (ref "U4") (pin "AF16") (pinfunction "GND_AF16") (pintype "passive"))
      (node (ref "U4") (pin "AF18") (pinfunction "GND_AF18") (pintype "passive"))
      (node (ref "U4") (pin "AF2") (pinfunction "GND_AF2") (pintype "passive"))
      (node (ref "U4") (pin "AF20") (pinfunction "GND_AF20") (pintype "passive"))
      (node (ref "U4") (pin "AF22") (pinfunction "GND_AF22") (pintype "passive"))
      (node (ref "U4") (pin "AF24") (pinfunction "GND_AF24") (pintype "passive"))
      (node (ref "U4") (pin "AF26") (pinfunction "GND_AF26") (pintype "passive"))
      (node (ref "U4") (pin "AF28") (pinfunction "GND_AF28") (pintype "passive"))
      (node (ref "U4") (pin "AF30") (pinfunction "GND_AF30") (pintype "passive"))
      (node (ref "U4") (pin "AF4") (pinfunction "GND_AF4") (pintype "passive"))
      (node (ref "U4") (pin "AF6") (pinfunction "GND_AF6") (pintype "passive"))
      (node (ref "U4") (pin "AF8") (pinfunction "GND_AF8") (pintype "passive"))
      (node (ref "U4") (pin "AG1") (pinfunction "GND_AG1") (pintype "passive"))
      (node (ref "U4") (pin "AG11") (pinfunction "GND_AG11") (pintype "passive"))
      (node (ref "U4") (pin "AG13") (pinfunction "GND_AG13") (pintype "passive"))
      (node (ref "U4") (pin "AG15") (pinfunction "GND_AG15") (pintype "passive"))
      (node (ref "U4") (pin "AG17") (pinfunction "GND_AG17") (pintype "passive"))
      (node (ref "U4") (pin "AG19") (pinfunction "GND_AG19") (pintype "passive"))
      (node (ref "U4") (pin "AG21") (pinfunction "GND_AG21") (pintype "passive"))
      (node (ref "U4") (pin "AG23") (pinfunction "GND_AG23") (pintype "passive"))
      (node (ref "U4") (pin "AG25") (pinfunction "GND_AG25") (pintype "passive"))
      (node (ref "U4") (pin "AG27") (pinfunction "GND_AG27") (pintype "passive"))
      (node (ref "U4") (pin "AG29") (pinfunction "GND_AG29") (pintype "passive"))
      (node (ref "U4") (pin "AG3") (pinfunction "GND_AG3") (pintype "passive"))
      (node (ref "U4") (pin "AG5") (pinfunction "GND_AG5") (pintype "passive"))
      (node (ref "U4") (pin "AG7") (pinfunction "GND_AG7") (pintype "passive"))
      (node (ref "U4") (pin "AG9") (pinfunction "GND_AG9") (pintype "passive"))
      (node (ref "U4") (pin "AH10") (pinfunction "GND_AH10") (pintype "passive"))
      (node (ref "U4") (pin "AH12") (pinfunction "GND_AH12") (pintype "passive"))
      (node (ref "U4") (pin "AH14") (pinfunction "GND_AH14") (pintype "passive"))
      (node (ref "U4") (pin "AH16") (pinfunction "GND_AH16") (pintype "passive"))
      (node (ref "U4") (pin "AH18") (pinfunction "GND_AH18") (pintype "passive"))
      (node (ref "U4") (pin "AH2") (pinfunction "GND_AH2") (pintype "passive"))
      (node (ref "U4") (pin "AH20") (pinfunction "GND_AH20") (pintype "passive"))
      (node (ref "U4") (pin "AH22") (pinfunction "GND_AH22") (pintype "passive"))
      (node (ref "U4") (pin "AH24") (pinfunction "GND_AH24") (pintype "passive"))
      (node (ref "U4") (pin "AH26") (pinfunction "GND_AH26") (pintype "passive"))
      (node (ref "U4") (pin "AH28") (pinfunction "GND_AH28") (pintype "passive"))
      (node (ref "U4") (pin "AH30") (pinfunction "GND_AH30") (pintype "passive"))
      (node (ref "U4") (pin "AH4") (pinfunction "GND_AH4") (pintype "passive"))
      (node (ref "U4") (pin "AH6") (pinfunction "GND_AH6") (pintype "passive"))
      (node (ref "U4") (pin "AH8") (pinfunction "GND_AH8") (pintype "passive"))
      (node (ref "U4") (pin "AJ1") (pinfunction "GND_AJ1") (pintype "passive"))
      (node (ref "U4") (pin "AJ11") (pinfunction "GND_AJ11") (pintype "passive"))
      (node (ref "U4") (pin "AJ17") (pinfunction "GND_AJ17") (pintype "passive"))
      (node (ref "U4") (pin "AJ27") (pinfunction "GND_AJ27") (pintype "passive"))
      (node (ref "U4") (pin "AJ29") (pinfunction "GND_AJ29") (pintype "passive"))
      (node (ref "U4") (pin "AJ3") (pinfunction "GND_AJ3") (pintype "passive"))
      (node (ref "U4") (pin "AJ4") (pinfunction "GND_AJ4") (pintype "passive"))
      (node (ref "U4") (pin "AJ6") (pinfunction "GND_AJ6") (pintype "passive"))
      (node (ref "U4") (pin "AJ9") (pinfunction "GND_AJ9") (pintype "passive"))
      (node (ref "U4") (pin "AK14") (pinfunction "GND_AK14") (pintype "passive"))
      (node (ref "U4") (pin "AK17") (pinfunction "GND_AK17") (pintype "passive"))
      (node (ref "U4") (pin "AK2") (pinfunction "GND_AK2") (pintype "passive"))
      (node (ref "U4") (pin "AK20") (pinfunction "GND_AK20") (pintype "passive"))
      (node (ref "U4") (pin "AK23") (pinfunction "GND_AK23") (pintype "passive"))
      (node (ref "U4") (pin "AK30") (pinfunction "GND_AK30") (pintype "passive"))
      (node (ref "U4") (pin "B10") (pinfunction "GND_B10") (pintype "passive"))
      (node (ref "U4") (pin "B12") (pinfunction "GND_B12") (pintype "passive"))
      (node (ref "U4") (pin "B14") (pinfunction "GND_B14") (pintype "passive"))
      (node (ref "U4") (pin "B16") (pinfunction "GND_B16") (pintype "passive"))
      (node (ref "U4") (pin "B18") (pinfunction "GND_B18") (pintype "passive"))
      (node (ref "U4") (pin "B2") (pinfunction "GND_B2") (pintype "passive"))
      (node (ref "U4") (pin "B20") (pinfunction "GND_B20") (pintype "passive"))
      (node (ref "U4") (pin "B22") (pinfunction "GND_B22") (pintype "passive"))
      (node (ref "U4") (pin "B24") (pinfunction "GND_B24") (pintype "passive"))
      (node (ref "U4") (pin "B26") (pinfunction "GND_B26") (pintype "passive"))
      (node (ref "U4") (pin "B28") (pinfunction "GND_B28") (pintype "passive"))
      (node (ref "U4") (pin "B30") (pinfunction "GND_B30") (pintype "passive"))
      (node (ref "U4") (pin "B4") (pinfunction "GND_B4") (pintype "passive"))
      (node (ref "U4") (pin "B6") (pinfunction "GND_B6") (pintype "passive"))
      (node (ref "U4") (pin "B8") (pinfunction "GND_B8") (pintype "passive"))
      (node (ref "U4") (pin "C1") (pinfunction "GND_C1") (pintype "passive"))
      (node (ref "U4") (pin "C11") (pinfunction "GND_C11") (pintype "passive"))
      (node (ref "U4") (pin "C13") (pinfunction "GND_C13") (pintype "passive"))
      (node (ref "U4") (pin "C15") (pinfunction "GND_C15") (pintype "passive"))
      (node (ref "U4") (pin "C17") (pinfunction "GND_C17") (pintype "passive"))
      (node (ref "U4") (pin "C19") (pinfunction "GND_C19") (pintype "passive"))
      (node (ref "U4") (pin "C21") (pinfunction "GND_C21") (pintype "passive"))
      (node (ref "U4") (pin "C23") (pinfunction "GND_C23") (pintype "passive"))
      (node (ref "U4") (pin "C25") (pinfunction "GND_C25") (pintype "passive"))
      (node (ref "U4") (pin "C27") (pinfunction "GND_C27") (pintype "passive"))
      (node (ref "U4") (pin "C29") (pinfunction "GND_C29") (pintype "passive"))
      (node (ref "U4") (pin "C3") (pinfunction "GND_C3") (pintype "passive"))
      (node (ref "U4") (pin "C5") (pinfunction "GND_C5") (pintype "passive"))
      (node (ref "U4") (pin "C7") (pinfunction "GND_C7") (pintype "passive"))
      (node (ref "U4") (pin "C9") (pinfunction "GND_C9") (pintype "passive"))
      (node (ref "U4") (pin "D10") (pinfunction "GND_D10") (pintype "passive"))
      (node (ref "U4") (pin "D12") (pinfunction "GND_D12") (pintype "passive"))
      (node (ref "U4") (pin "D14") (pinfunction "GND_D14") (pintype "passive"))
      (node (ref "U4") (pin "D16") (pinfunction "GND_D16") (pintype "passive"))
      (node (ref "U4") (pin "D18") (pinfunction "GND_D18") (pintype "passive"))
      (node (ref "U4") (pin "D2") (pinfunction "GND_D2") (pintype "passive"))
      (node (ref "U4") (pin "D20") (pinfunction "GND_D20") (pintype "passive"))
      (node (ref "U4") (pin "D22") (pinfunction "GND_D22") (pintype "passive"))
      (node (ref "U4") (pin "D24") (pinfunction "GND_D24") (pintype "passive"))
      (node (ref "U4") (pin "D26") (pinfunction "GND_D26") (pintype "passive"))
      (node (ref "U4") (pin "D28") (pinfunction "GND_D28") (pintype "passive"))
      (node (ref "U4") (pin "D30") (pinfunction "GND_D30") (pintype "passive"))
      (node (ref "U4") (pin "D4") (pinfunction "GND_D4") (pintype "passive"))
      (node (ref "U4") (pin "D6") (pinfunction "GND_D6") (pintype "passive"))
      (node (ref "U4") (pin "D8") (pinfunction "GND_D8") (pintype "passive"))
      (node (ref "U4") (pin "E1") (pinfunction "GND_E1") (pintype "passive"))
      (node (ref "U4") (pin "E11") (pinfunction "GND_E11") (pintype "passive"))
      (node (ref "U4") (pin "E13") (pinfunction "GND_E13") (pintype "passive"))
      (node (ref "U4") (pin "E15") (pinfunction "GND_E15") (pintype "passive"))
      (node (ref "U4") (pin "E17") (pinfunction "GND_E17") (pintype "passive"))
      (node (ref "U4") (pin "E19") (pinfunction "GND_E19") (pintype "passive"))
      (node (ref "U4") (pin "E21") (pinfunction "GND_E21") (pintype "passive"))
      (node (ref "U4") (pin "E23") (pinfunction "GND_E23") (pintype "passive"))
      (node (ref "U4") (pin "E25") (pinfunction "GND_E25") (pintype "passive"))
      (node (ref "U4") (pin "E27") (pinfunction "GND_E27") (pintype "passive"))
      (node (ref "U4") (pin "E29") (pinfunction "GND_E29") (pintype "passive"))
      (node (ref "U4") (pin "E3") (pinfunction "GND_E3") (pintype "passive"))
      (node (ref "U4") (pin "E5") (pinfunction "GND_E5") (pintype "passive"))
      (node (ref "U4") (pin "E7") (pinfunction "GND_E7") (pintype "passive"))
      (node (ref "U4") (pin "E9") (pinfunction "GND_E9") (pintype "passive"))
      (node (ref "U4") (pin "F10") (pinfunction "GND_F10") (pintype "passive"))
      (node (ref "U4") (pin "F12") (pinfunction "GND_F12") (pintype "passive"))
      (node (ref "U4") (pin "F14") (pinfunction "GND_F14") (pintype "passive"))
      (node (ref "U4") (pin "F16") (pinfunction "GND_F16") (pintype "passive"))
      (node (ref "U4") (pin "F18") (pinfunction "GND_F18") (pintype "passive"))
      (node (ref "U4") (pin "F2") (pinfunction "GND_F2") (pintype "passive"))
      (node (ref "U4") (pin "F20") (pinfunction "GND_F20") (pintype "passive"))
      (node (ref "U4") (pin "F22") (pinfunction "GND_F22") (pintype "passive"))
      (node (ref "U4") (pin "F24") (pinfunction "GND_F24") (pintype "passive"))
      (node (ref "U4") (pin "F26") (pinfunction "GND_F26") (pintype "passive"))
      (node (ref "U4") (pin "F28") (pinfunction "GND_F28") (pintype "passive"))
      (node (ref "U4") (pin "F30") (pinfunction "GND_F30") (pintype "passive"))
      (node (ref "U4") (pin "F4") (pinfunction "GND_F4") (pintype "passive"))
      (node (ref "U4") (pin "F6") (pinfunction "GND_F6") (pintype "passive"))
      (node (ref "U4") (pin "F8") (pinfunction "GND_F8") (pintype "passive"))
      (node (ref "U4") (pin "G1") (pinfunction "GND_G1") (pintype "passive"))
      (node (ref "U4") (pin "G11") (pinfunction "GND_G11") (pintype "passive"))
      (node (ref "U4") (pin "G13") (pinfunction "GND_G13") (pintype "passive"))
      (node (ref "U4") (pin "G15") (pinfunction "GND_G15") (pintype "passive"))
      (node (ref "U4") (pin "G17") (pinfunction "GND_G17") (pintype "passive"))
      (node (ref "U4") (pin "G19") (pinfunction "GND_G19") (pintype "passive"))
      (node (ref "U4") (pin "G21") (pinfunction "GND_G21") (pintype "passive"))
      (node (ref "U4") (pin "G23") (pinfunction "GND_G23") (pintype "passive"))
      (node (ref "U4") (pin "G25") (pinfunction "GND_G25") (pintype "passive"))
      (node (ref "U4") (pin "G27") (pinfunction "GND_G27") (pintype "passive"))
      (node (ref "U4") (pin "G29") (pinfunction "GND_G29") (pintype "passive"))
      (node (ref "U4") (pin "G3") (pinfunction "GND_G3") (pintype "passive"))
      (node (ref "U4") (pin "G5") (pinfunction "GND_G5") (pintype "passive"))
      (node (ref "U4") (pin "G7") (pinfunction "GND_G7") (pintype "passive"))
      (node (ref "U4") (pin "G9") (pinfunction "GND_G9") (pintype "passive"))
      (node (ref "U4") (pin "H10") (pinfunction "GND_H10") (pintype "passive"))
      (node (ref "U4") (pin "H12") (pinfunction "GND_H12") (pintype "passive"))
      (node (ref "U4") (pin "H14") (pinfunction "GND_H14") (pintype "passive"))
      (node (ref "U4") (pin "H16") (pinfunction "GND_H16") (pintype "passive"))
      (node (ref "U4") (pin "H18") (pinfunction "GND_H18") (pintype "passive"))
      (node (ref "U4") (pin "H2") (pinfunction "GND_H2") (pintype "passive"))
      (node (ref "U4") (pin "H20") (pinfunction "GND_H20") (pintype "passive"))
      (node (ref "U4") (pin "H22") (pinfunction "GND_H22") (pintype "passive"))
      (node (ref "U4") (pin "H24") (pinfunction "GND_H24") (pintype "passive"))
      (node (ref "U4") (pin "H26") (pinfunction "GND_H26") (pintype "passive"))
      (node (ref "U4") (pin "H28") (pinfunction "GND_H28") (pintype "passive"))
      (node (ref "U4") (pin "H30") (pinfunction "GND_H30") (pintype "passive"))
      (node (ref "U4") (pin "H4") (pinfunction "GND_H4") (pintype "passive"))
      (node (ref "U4") (pin "H6") (pinfunction "GND_H6") (pintype "passive"))
      (node (ref "U4") (pin "H8") (pinfunction "GND_H8") (pintype "passive"))
      (node (ref "U4") (pin "J1") (pinfunction "GND_J1") (pintype "passive"))
      (node (ref "U4") (pin "J11") (pinfunction "GND_J11") (pintype "passive"))
      (node (ref "U4") (pin "J13") (pinfunction "GND_J13") (pintype "passive"))
      (node (ref "U4") (pin "J15") (pinfunction "GND_J15") (pintype "passive"))
      (node (ref "U4") (pin "J17") (pinfunction "GND_J17") (pintype "passive"))
      (node (ref "U4") (pin "J19") (pinfunction "GND_J19") (pintype "passive"))
      (node (ref "U4") (pin "J21") (pinfunction "GND_J21") (pintype "passive"))
      (node (ref "U4") (pin "J23") (pinfunction "GND_J23") (pintype "passive"))
      (node (ref "U4") (pin "J25") (pinfunction "GND_J25") (pintype "passive"))
      (node (ref "U4") (pin "J27") (pinfunction "GND_J27") (pintype "passive"))
      (node (ref "U4") (pin "J29") (pinfunction "GND_J29") (pintype "passive"))
      (node (ref "U4") (pin "J3") (pinfunction "GND_J3") (pintype "passive"))
      (node (ref "U4") (pin "J5") (pinfunction "GND_J5") (pintype "passive"))
      (node (ref "U4") (pin "J7") (pinfunction "GND_J7") (pintype "passive"))
      (node (ref "U4") (pin "J9") (pinfunction "GND_J9") (pintype "passive"))
      (node (ref "U4") (pin "K10") (pinfunction "GND_K10") (pintype "passive"))
      (node (ref "U4") (pin "K12") (pinfunction "GND_K12") (pintype "passive"))
      (node (ref "U4") (pin "K14") (pinfunction "GND_K14") (pintype "passive"))
      (node (ref "U4") (pin "K16") (pinfunction "GND_K16") (pintype "passive"))
      (node (ref "U4") (pin "K18") (pinfunction "GND_K18") (pintype "passive"))
      (node (ref "U4") (pin "K2") (pinfunction "GND_K2") (pintype "passive"))
      (node (ref "U4") (pin "K20") (pinfunction "GND_K20") (pintype "passive"))
      (node (ref "U4") (pin "K22") (pinfunction "GND_K22") (pintype "passive"))
      (node (ref "U4") (pin "K24") (pinfunction "GND_K24") (pintype "passive"))
      (node (ref "U4") (pin "K26") (pinfunction "GND_K26") (pintype "passive"))
      (node (ref "U4") (pin "K28") (pinfunction "GND_K28") (pintype "passive"))
      (node (ref "U4") (pin "K30") (pinfunction "GND_K30") (pintype "passive"))
      (node (ref "U4") (pin "K4") (pinfunction "GND_K4") (pintype "passive"))
      (node (ref "U4") (pin "K6") (pinfunction "GND_K6") (pintype "passive"))
      (node (ref "U4") (pin "K8") (pinfunction "GND_K8") (pintype "passive"))
      (node (ref "U4") (pin "L1") (pinfunction "GND_L1") (pintype "passive"))
      (node (ref "U4") (pin "L11") (pinfunction "GND_L11") (pintype "passive"))
      (node (ref "U4") (pin "L13") (pinfunction "GND_L13") (pintype "passive"))
      (node (ref "U4") (pin "L15") (pinfunction "GND_L15") (pintype "passive"))
      (node (ref "U4") (pin "L17") (pinfunction "GND_L17") (pintype "passive"))
      (node (ref "U4") (pin "L19") (pinfunction "GND_L19") (pintype "passive"))
      (node (ref "U4") (pin "L21") (pinfunction "GND_L21") (pintype "passive"))
      (node (ref "U4") (pin "L23") (pinfunction "GND_L23") (pintype "passive"))
      (node (ref "U4") (pin "L25") (pinfunction "GND_L25") (pintype "passive"))
      (node (ref "U4") (pin "L27") (pinfunction "GND_L27") (pintype "passive"))
      (node (ref "U4") (pin "L29") (pinfunction "GND_L29") (pintype "passive"))
      (node (ref "U4") (pin "L3") (pinfunction "GND_L3") (pintype "passive"))
      (node (ref "U4") (pin "L5") (pinfunction "GND_L5") (pintype "passive"))
      (node (ref "U4") (pin "L7") (pinfunction "GND_L7") (pintype "passive"))
      (node (ref "U4") (pin "L9") (pinfunction "GND_L9") (pintype "passive"))
      (node (ref "U4") (pin "M10") (pinfunction "GND_M10") (pintype "passive"))
      (node (ref "U4") (pin "M12") (pinfunction "GND_M12") (pintype "passive"))
      (node (ref "U4") (pin "M14") (pinfunction "GND_M14") (pintype "passive"))
      (node (ref "U4") (pin "M16") (pinfunction "GND_M16") (pintype "passive"))
      (node (ref "U4") (pin "M18") (pinfunction "GND_M18") (pintype "passive"))
      (node (ref "U4") (pin "M2") (pinfunction "GND_M2") (pintype "passive"))
      (node (ref "U4") (pin "M20") (pinfunction "GND_M20") (pintype "passive"))
      (node (ref "U4") (pin "M22") (pinfunction "GND_M22") (pintype "passive"))
      (node (ref "U4") (pin "M24") (pinfunction "GND_M24") (pintype "passive"))
      (node (ref "U4") (pin "M26") (pinfunction "GND_M26") (pintype "passive"))
      (node (ref "U4") (pin "M28") (pinfunction "GND_M28") (pintype "passive"))
      (node (ref "U4") (pin "M30") (pinfunction "GND_M30") (pintype "passive"))
      (node (ref "U4") (pin "M4") (pinfunction "GND_M4") (pintype "passive"))
      (node (ref "U4") (pin "M6") (pinfunction "GND_M6") (pintype "passive"))
      (node (ref "U4") (pin "M8") (pinfunction "GND_M8") (pintype "passive"))
      (node (ref "U4") (pin "N1") (pinfunction "GND_N1") (pintype "passive"))
      (node (ref "U4") (pin "N11") (pinfunction "GND_N11") (pintype "passive"))
      (node (ref "U4") (pin "N13") (pinfunction "GND_N13") (pintype "passive"))
      (node (ref "U4") (pin "N15") (pinfunction "GND_N15") (pintype "passive"))
      (node (ref "U4") (pin "N17") (pinfunction "GND_N17") (pintype "passive"))
      (node (ref "U4") (pin "N19") (pinfunction "GND_N19") (pintype "passive"))
      (node (ref "U4") (pin "N21") (pinfunction "GND_N21") (pintype "passive"))
      (node (ref "U4") (pin "N23") (pinfunction "GND_N23") (pintype "passive"))
      (node (ref "U4") (pin "N25") (pinfunction "GND_N25") (pintype "passive"))
      (node (ref "U4") (pin "N27") (pinfunction "GND_N27") (pintype "passive"))
      (node (ref "U4") (pin "N29") (pinfunction "GND_N29") (pintype "passive"))
      (node (ref "U4") (pin "N3") (pinfunction "GND_N3") (pintype "passive"))
      (node (ref "U4") (pin "N5") (pinfunction "GND_N5") (pintype "passive"))
      (node (ref "U4") (pin "N7") (pinfunction "GND_N7") (pintype "passive"))
      (node (ref "U4") (pin "N9") (pinfunction "GND_N9") (pintype "passive"))
      (node (ref "U4") (pin "P10") (pinfunction "GND_P10") (pintype "passive"))
      (node (ref "U4") (pin "P12") (pinfunction "GND_P12") (pintype "passive"))
      (node (ref "U4") (pin "P14") (pinfunction "GND_P14") (pintype "passive"))
      (node (ref "U4") (pin "P16") (pinfunction "GND_P16") (pintype "passive"))
      (node (ref "U4") (pin "P18") (pinfunction "GND_P18") (pintype "passive"))
      (node (ref "U4") (pin "P2") (pinfunction "GND_P2") (pintype "passive"))
      (node (ref "U4") (pin "P20") (pinfunction "GND_P20") (pintype "passive"))
      (node (ref "U4") (pin "P22") (pinfunction "GND_P22") (pintype "passive"))
      (node (ref "U4") (pin "P24") (pinfunction "GND_P24") (pintype "passive"))
      (node (ref "U4") (pin "P26") (pinfunction "GND_P26") (pintype "passive"))
      (node (ref "U4") (pin "P28") (pinfunction "GND_P28") (pintype "passive"))
      (node (ref "U4") (pin "P30") (pinfunction "GND_P30") (pintype "passive"))
      (node (ref "U4") (pin "P4") (pinfunction "GND_P4") (pintype "passive"))
      (node (ref "U4") (pin "P6") (pinfunction "GND_P6") (pintype "passive"))
      (node (ref "U4") (pin "P8") (pinfunction "GND_P8") (pintype "passive"))
      (node (ref "U4") (pin "R1") (pinfunction "GND_R1") (pintype "passive"))
      (node (ref "U4") (pin "R11") (pinfunction "GND_R11") (pintype "passive"))
      (node (ref "U4") (pin "R13") (pinfunction "GND_R13") (pintype "passive"))
      (node (ref "U4") (pin "R15") (pinfunction "GND_R15") (pintype "passive"))
      (node (ref "U4") (pin "R17") (pinfunction "GND_R17") (pintype "passive"))
      (node (ref "U4") (pin "R19") (pinfunction "GND_R19") (pintype "passive"))
      (node (ref "U4") (pin "R21") (pinfunction "GND_R21") (pintype "passive"))
      (node (ref "U4") (pin "R23") (pinfunction "GND_R23") (pintype "passive"))
      (node (ref "U4") (pin "R25") (pinfunction "GND_R25") (pintype "passive"))
      (node (ref "U4") (pin "R27") (pinfunction "GND_R27") (pintype "passive"))
      (node (ref "U4") (pin "R29") (pinfunction "GND_R29") (pintype "passive"))
      (node (ref "U4") (pin "R3") (pinfunction "GND_R3") (pintype "passive"))
      (node (ref "U4") (pin "R5") (pinfunction "GND_R5") (pintype "passive"))
      (node (ref "U4") (pin "R7") (pinfunction "GND_R7") (pintype "passive"))
      (node (ref "U4") (pin "R9") (pinfunction "GND_R9") (pintype "passive"))
      (node (ref "U4") (pin "T10") (pinfunction "GND_T10") (pintype "passive"))
      (node (ref "U4") (pin "T12") (pinfunction "GND_T12") (pintype "passive"))
      (node (ref "U4") (pin "T14") (pinfunction "GND_T14") (pintype "passive"))
      (node (ref "U4") (pin "T16") (pinfunction "GND_T16") (pintype "passive"))
      (node (ref "U4") (pin "T18") (pinfunction "GND_T18") (pintype "passive"))
      (node (ref "U4") (pin "T2") (pinfunction "GND_T2") (pintype "passive"))
      (node (ref "U4") (pin "T20") (pinfunction "GND_T20") (pintype "passive"))
      (node (ref "U4") (pin "T22") (pinfunction "GND_T22") (pintype "passive"))
      (node (ref "U4") (pin "T24") (pinfunction "GND_T24") (pintype "passive"))
      (node (ref "U4") (pin "T26") (pinfunction "GND_T26") (pintype "passive"))
      (node (ref "U4") (pin "T28") (pinfunction "GND_T28") (pintype "passive"))
      (node (ref "U4") (pin "T30") (pinfunction "GND_T30") (pintype "passive"))
      (node (ref "U4") (pin "T4") (pinfunction "GND_T4") (pintype "passive"))
      (node (ref "U4") (pin "T6") (pinfunction "GND_T6") (pintype "passive"))
      (node (ref "U4") (pin "T8") (pinfunction "GND_T8") (pintype "passive"))
      (node (ref "U4") (pin "U1") (pinfunction "GND_U1") (pintype "passive"))
      (node (ref "U4") (pin "U11") (pinfunction "GND_U11") (pintype "passive"))
      (node (ref "U4") (pin "U13") (pinfunction "GND_U13") (pintype "passive"))
      (node (ref "U4") (pin "U15") (pinfunction "GND_U15") (pintype "passive"))
      (node (ref "U4") (pin "U17") (pinfunction "GND_U17") (pintype "passive"))
      (node (ref "U4") (pin "U19") (pinfunction "GND_U19") (pintype "passive"))
      (node (ref "U4") (pin "U21") (pinfunction "GND_U21") (pintype "passive"))
      (node (ref "U4") (pin "U23") (pinfunction "GND_U23") (pintype "passive"))
      (node (ref "U4") (pin "U25") (pinfunction "GND_U25") (pintype "passive"))
      (node (ref "U4") (pin "U27") (pinfunction "GND_U27") (pintype "passive"))
      (node (ref "U4") (pin "U29") (pinfunction "GND_U29") (pintype "passive"))
      (node (ref "U4") (pin "U3") (pinfunction "GND_U3") (pintype "passive"))
      (node (ref "U4") (pin "U5") (pinfunction "GND_U5") (pintype "passive"))
      (node (ref "U4") (pin "U7") (pinfunction "GND_U7") (pintype "passive"))
      (node (ref "U4") (pin "U9") (pinfunction "GND_U9") (pintype "passive"))
      (node (ref "U4") (pin "V10") (pinfunction "GND_V10") (pintype "passive"))
      (node (ref "U4") (pin "V12") (pinfunction "GND_V12") (pintype "passive"))
      (node (ref "U4") (pin "V14") (pinfunction "GND_V14") (pintype "passive"))
      (node (ref "U4") (pin "V16") (pinfunction "GND_V16") (pintype "passive"))
      (node (ref "U4") (pin "V18") (pinfunction "GND_V18") (pintype "passive"))
      (node (ref "U4") (pin "V2") (pinfunction "GND_V2") (pintype "passive"))
      (node (ref "U4") (pin "V20") (pinfunction "GND_V20") (pintype "passive"))
      (node (ref "U4") (pin "V22") (pinfunction "GND_V22") (pintype "passive"))
      (node (ref "U4") (pin "V24") (pinfunction "GND_V24") (pintype "passive"))
      (node (ref "U4") (pin "V26") (pinfunction "GND_V26") (pintype "passive"))
      (node (ref "U4") (pin "V28") (pinfunction "GND_V28") (pintype "passive"))
      (node (ref "U4") (pin "V30") (pinfunction "GND_V30") (pintype "passive"))
      (node (ref "U4") (pin "V4") (pinfunction "GND_V4") (pintype "passive"))
      (node (ref "U4") (pin "V6") (pinfunction "GND_V6") (pintype "passive"))
      (node (ref "U4") (pin "V8") (pinfunction "GND_V8") (pintype "passive"))
      (node (ref "U4") (pin "W1") (pinfunction "GND_W1") (pintype "passive"))
      (node (ref "U4") (pin "W11") (pinfunction "GND_W11") (pintype "passive"))
      (node (ref "U4") (pin "W13") (pinfunction "GND_W13") (pintype "passive"))
      (node (ref "U4") (pin "W15") (pinfunction "GND_W15") (pintype "passive"))
      (node (ref "U4") (pin "W17") (pinfunction "GND_W17") (pintype "passive"))
      (node (ref "U4") (pin "W19") (pinfunction "GND_W19") (pintype "passive"))
      (node (ref "U4") (pin "W21") (pinfunction "GND_W21") (pintype "passive"))
      (node (ref "U4") (pin "W23") (pinfunction "GND_W23") (pintype "passive"))
      (node (ref "U4") (pin "W25") (pinfunction "GND_W25") (pintype "passive"))
      (node (ref "U4") (pin "W27") (pinfunction "GND_W27") (pintype "passive"))
      (node (ref "U4") (pin "W29") (pinfunction "GND_W29") (pintype "passive"))
      (node (ref "U4") (pin "W3") (pinfunction "GND_W3") (pintype "passive"))
      (node (ref "U4") (pin "W5") (pinfunction "GND_W5") (pintype "passive"))
      (node (ref "U4") (pin "W7") (pinfunction "GND_W7") (pintype "passive"))
      (node (ref "U4") (pin "W9") (pinfunction "GND_W9") (pintype "passive"))
      (node (ref "U4") (pin "Y10") (pinfunction "GND_Y10") (pintype "passive"))
      (node (ref "U4") (pin "Y12") (pinfunction "GND_Y12") (pintype "passive"))
      (node (ref "U4") (pin "Y14") (pinfunction "GND_Y14") (pintype "passive"))
      (node (ref "U4") (pin "Y16") (pinfunction "GND_Y16") (pintype "passive"))
      (node (ref "U4") (pin "Y18") (pinfunction "GND_Y18") (pintype "passive"))
      (node (ref "U4") (pin "Y2") (pinfunction "GND_Y2") (pintype "passive"))
      (node (ref "U4") (pin "Y20") (pinfunction "GND_Y20") (pintype "passive"))
      (node (ref "U4") (pin "Y22") (pinfunction "GND_Y22") (pintype "passive"))
      (node (ref "U4") (pin "Y24") (pinfunction "GND_Y24") (pintype "passive"))
      (node (ref "U4") (pin "Y26") (pinfunction "GND_Y26") (pintype "passive"))
      (node (ref "U4") (pin "Y28") (pinfunction "GND_Y28") (pintype "passive"))
      (node (ref "U4") (pin "Y30") (pinfunction "GND_Y30") (pintype "passive"))
      (node (ref "U4") (pin "Y4") (pinfunction "GND_Y4") (pintype "passive"))
      (node (ref "U4") (pin "Y6") (pinfunction "GND_Y6") (pintype "passive"))
      (node (ref "U4") (pin "Y8") (pinfunction "GND_Y8") (pintype "passive"))
    )
  )
)
